# snowmaker_V1_0_for_eagle7_5.net
KiCad netlist of a schematic drawn in EAGLE
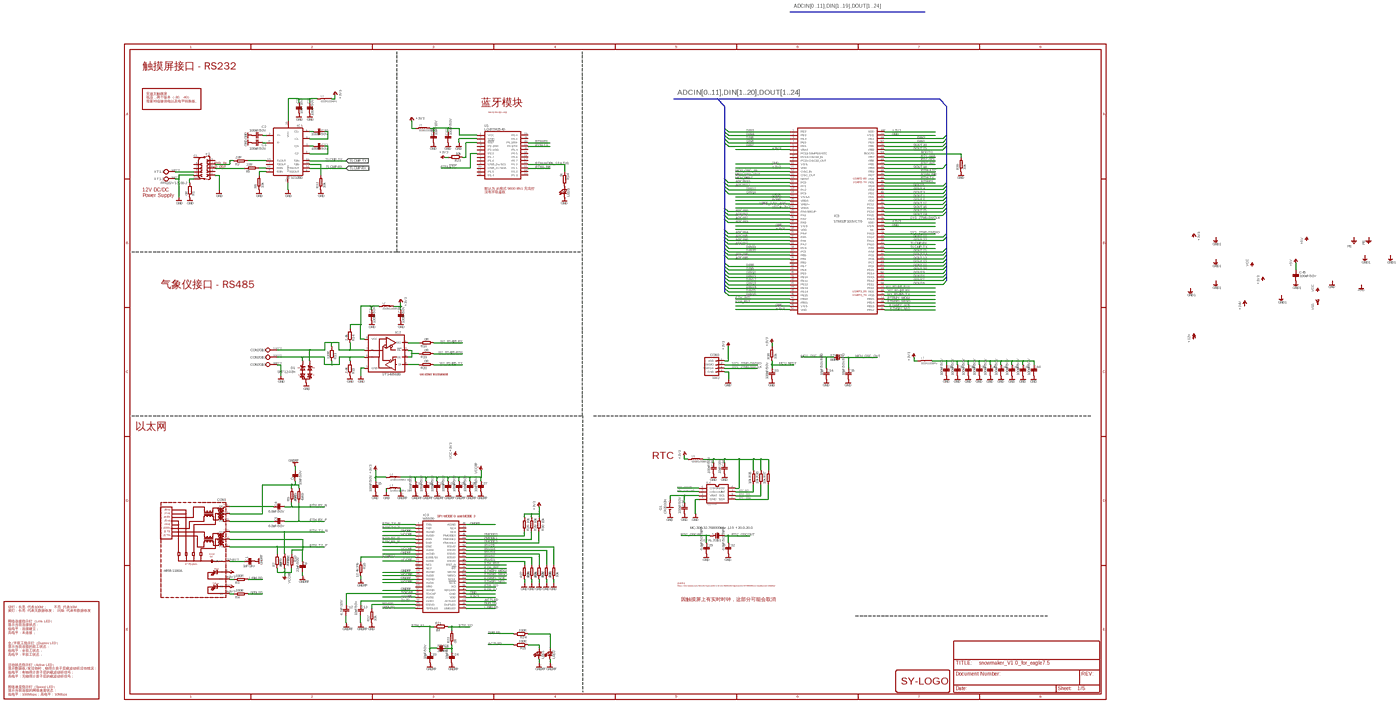
[diagram p0: schematic, sheet 1, overview]
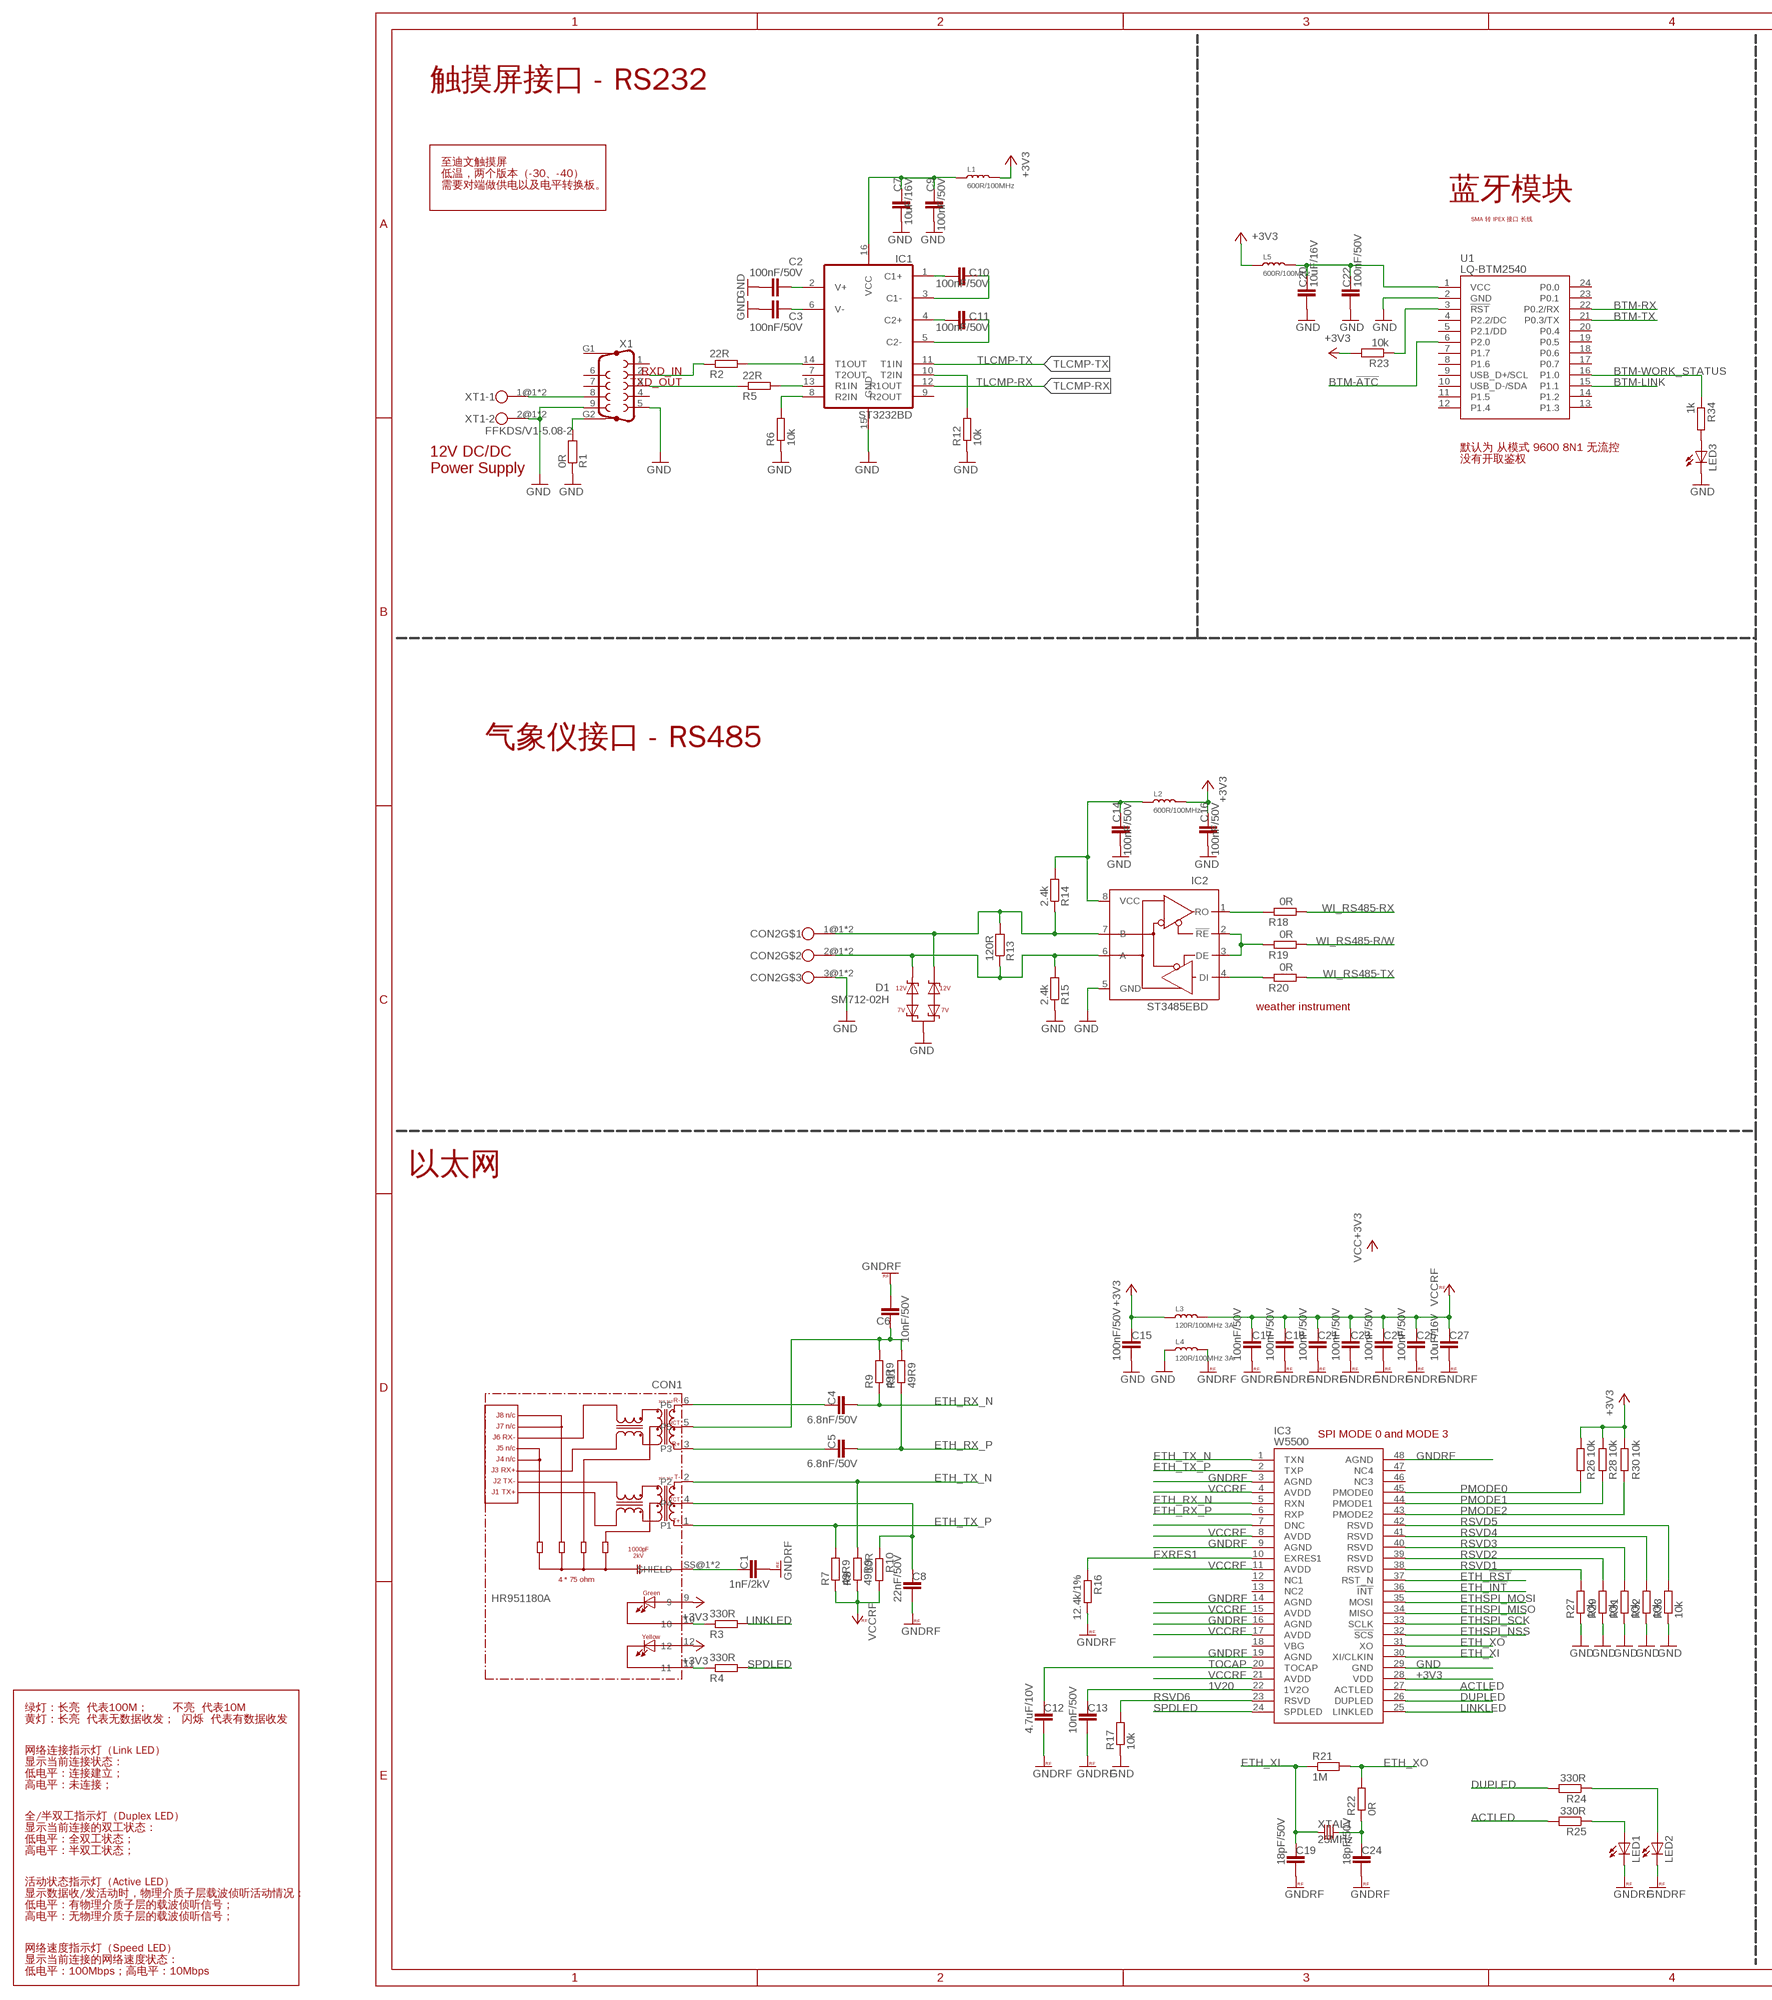
[diagram p1: schematic, sheet 1, part 1 of 4]
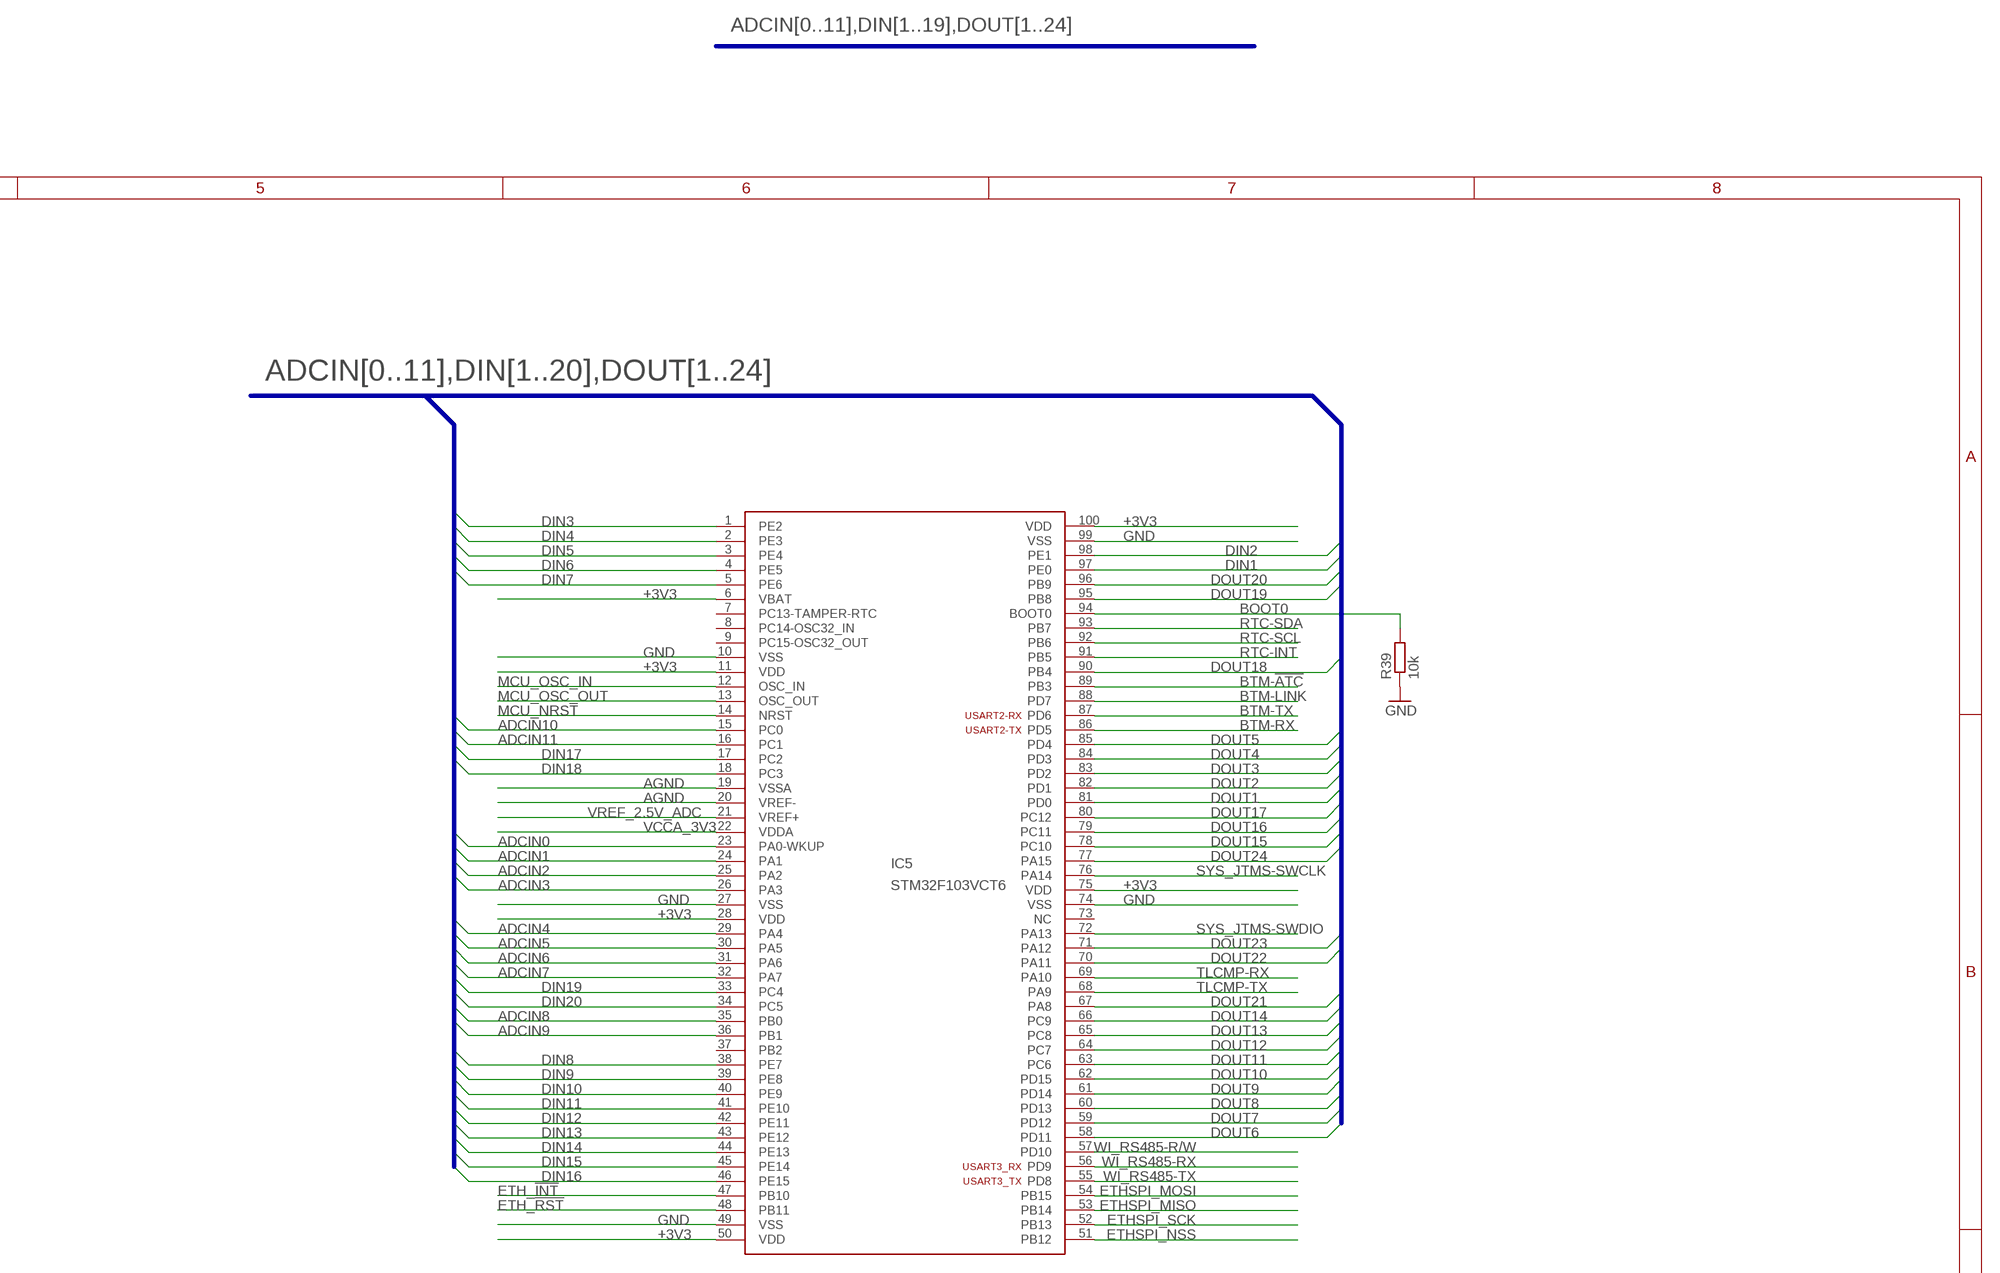
[diagram p2: schematic, sheet 1, part 2 of 4]
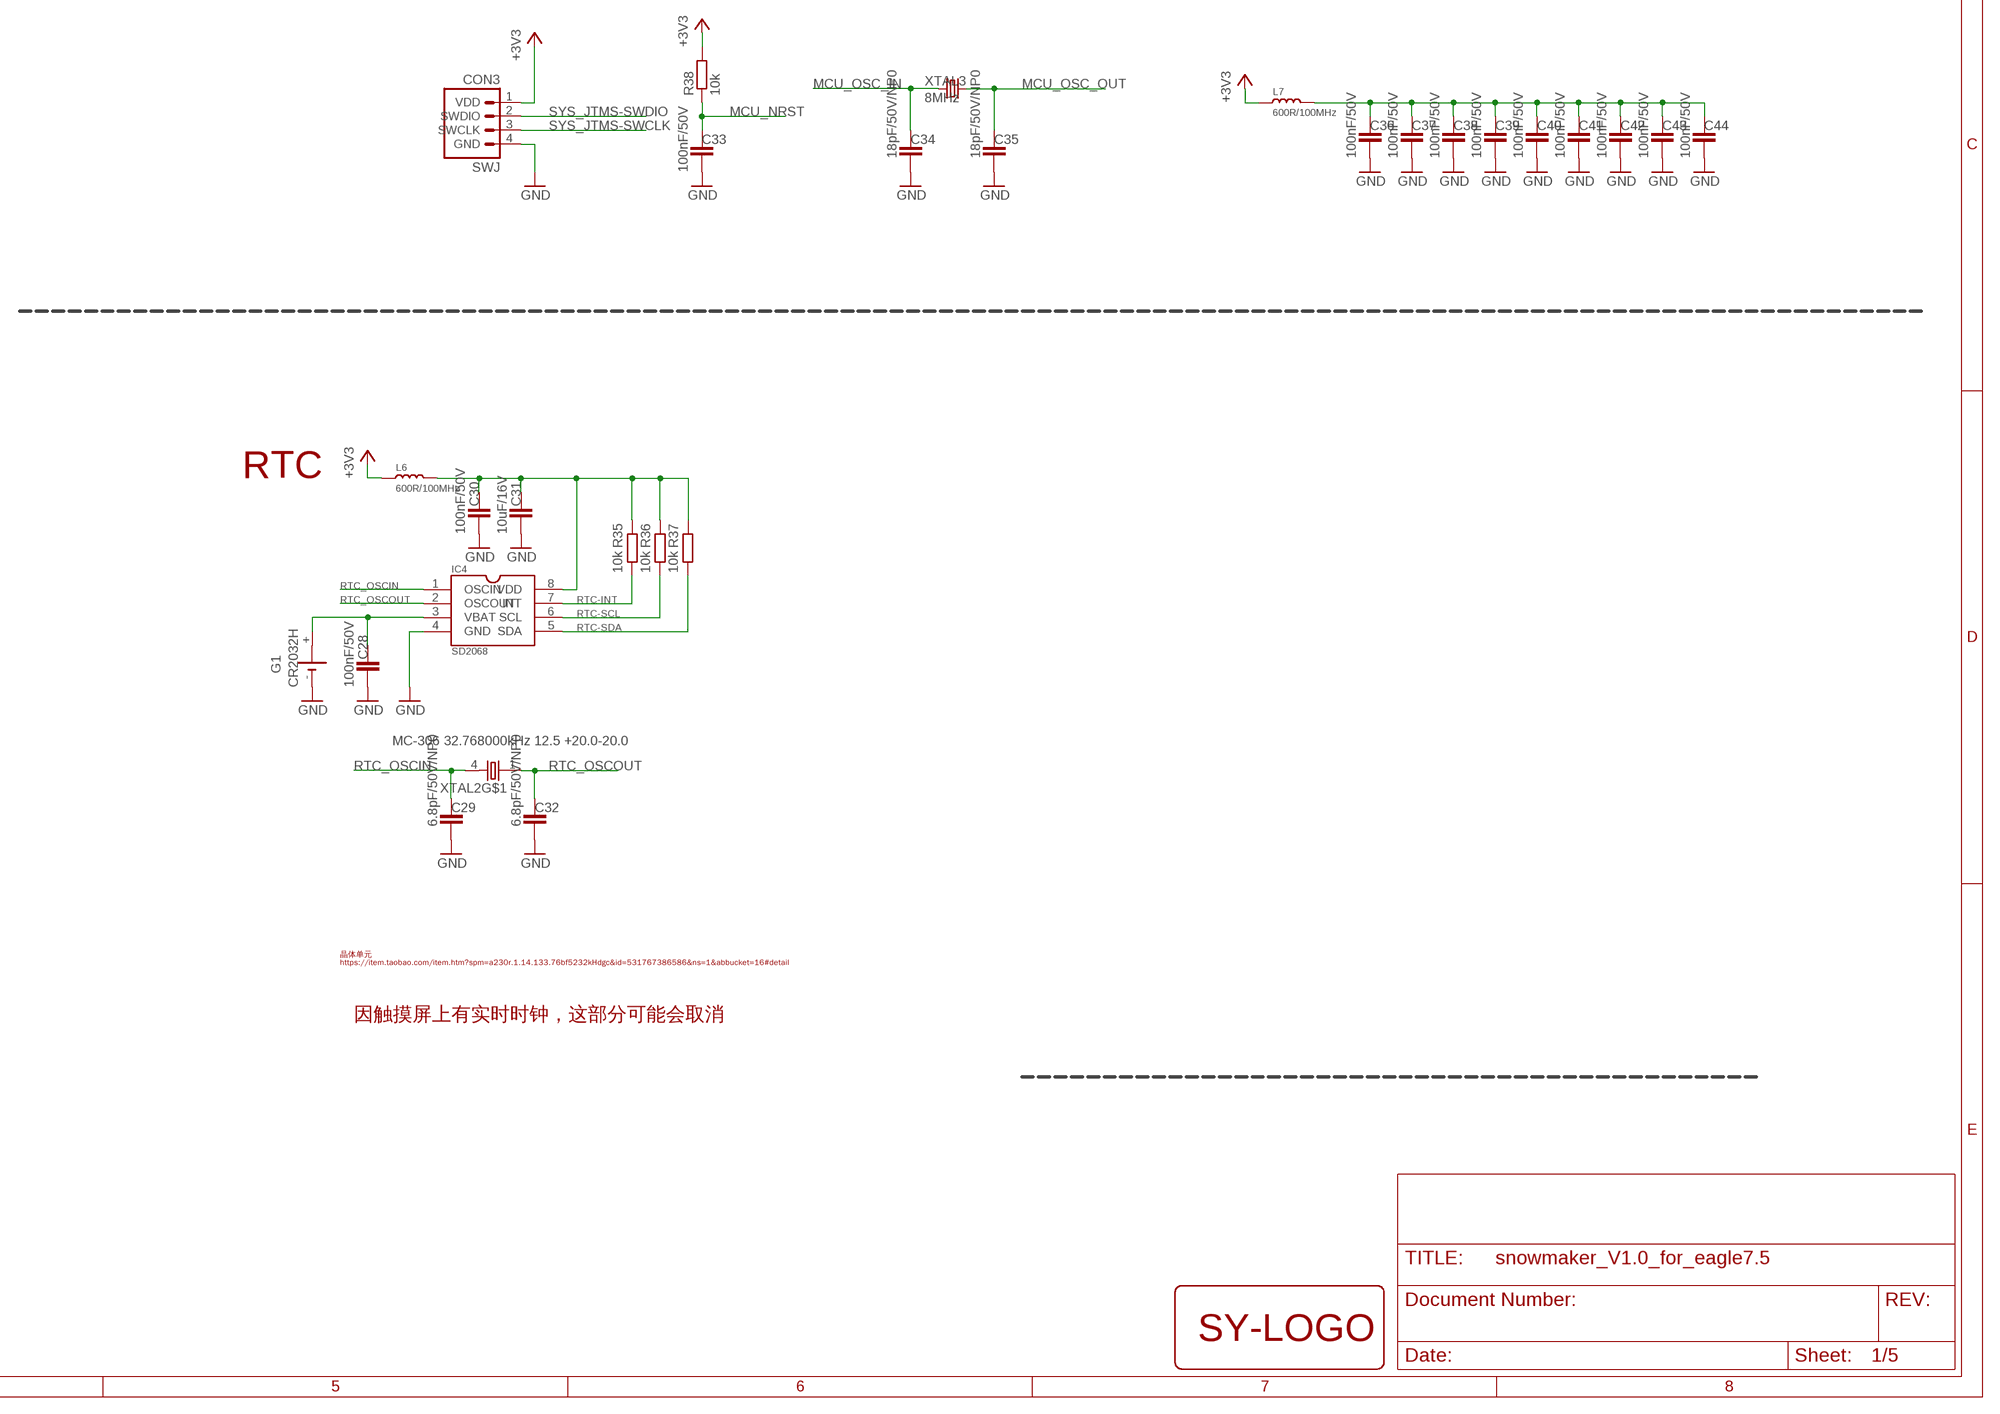
[diagram p3: schematic, sheet 1, part 3 of 4]
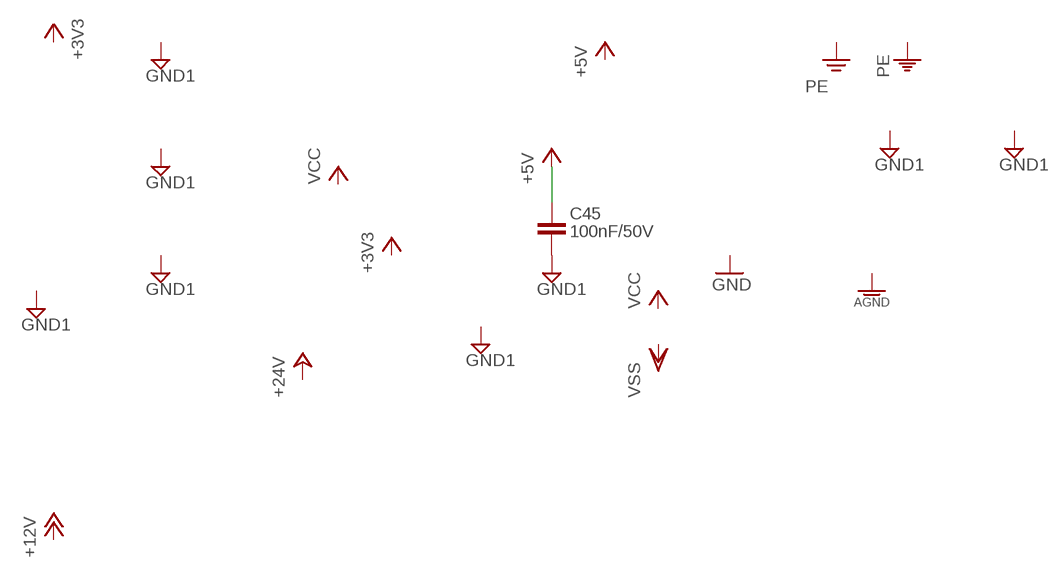
[diagram p4: schematic, sheet 1, part 4 of 4]
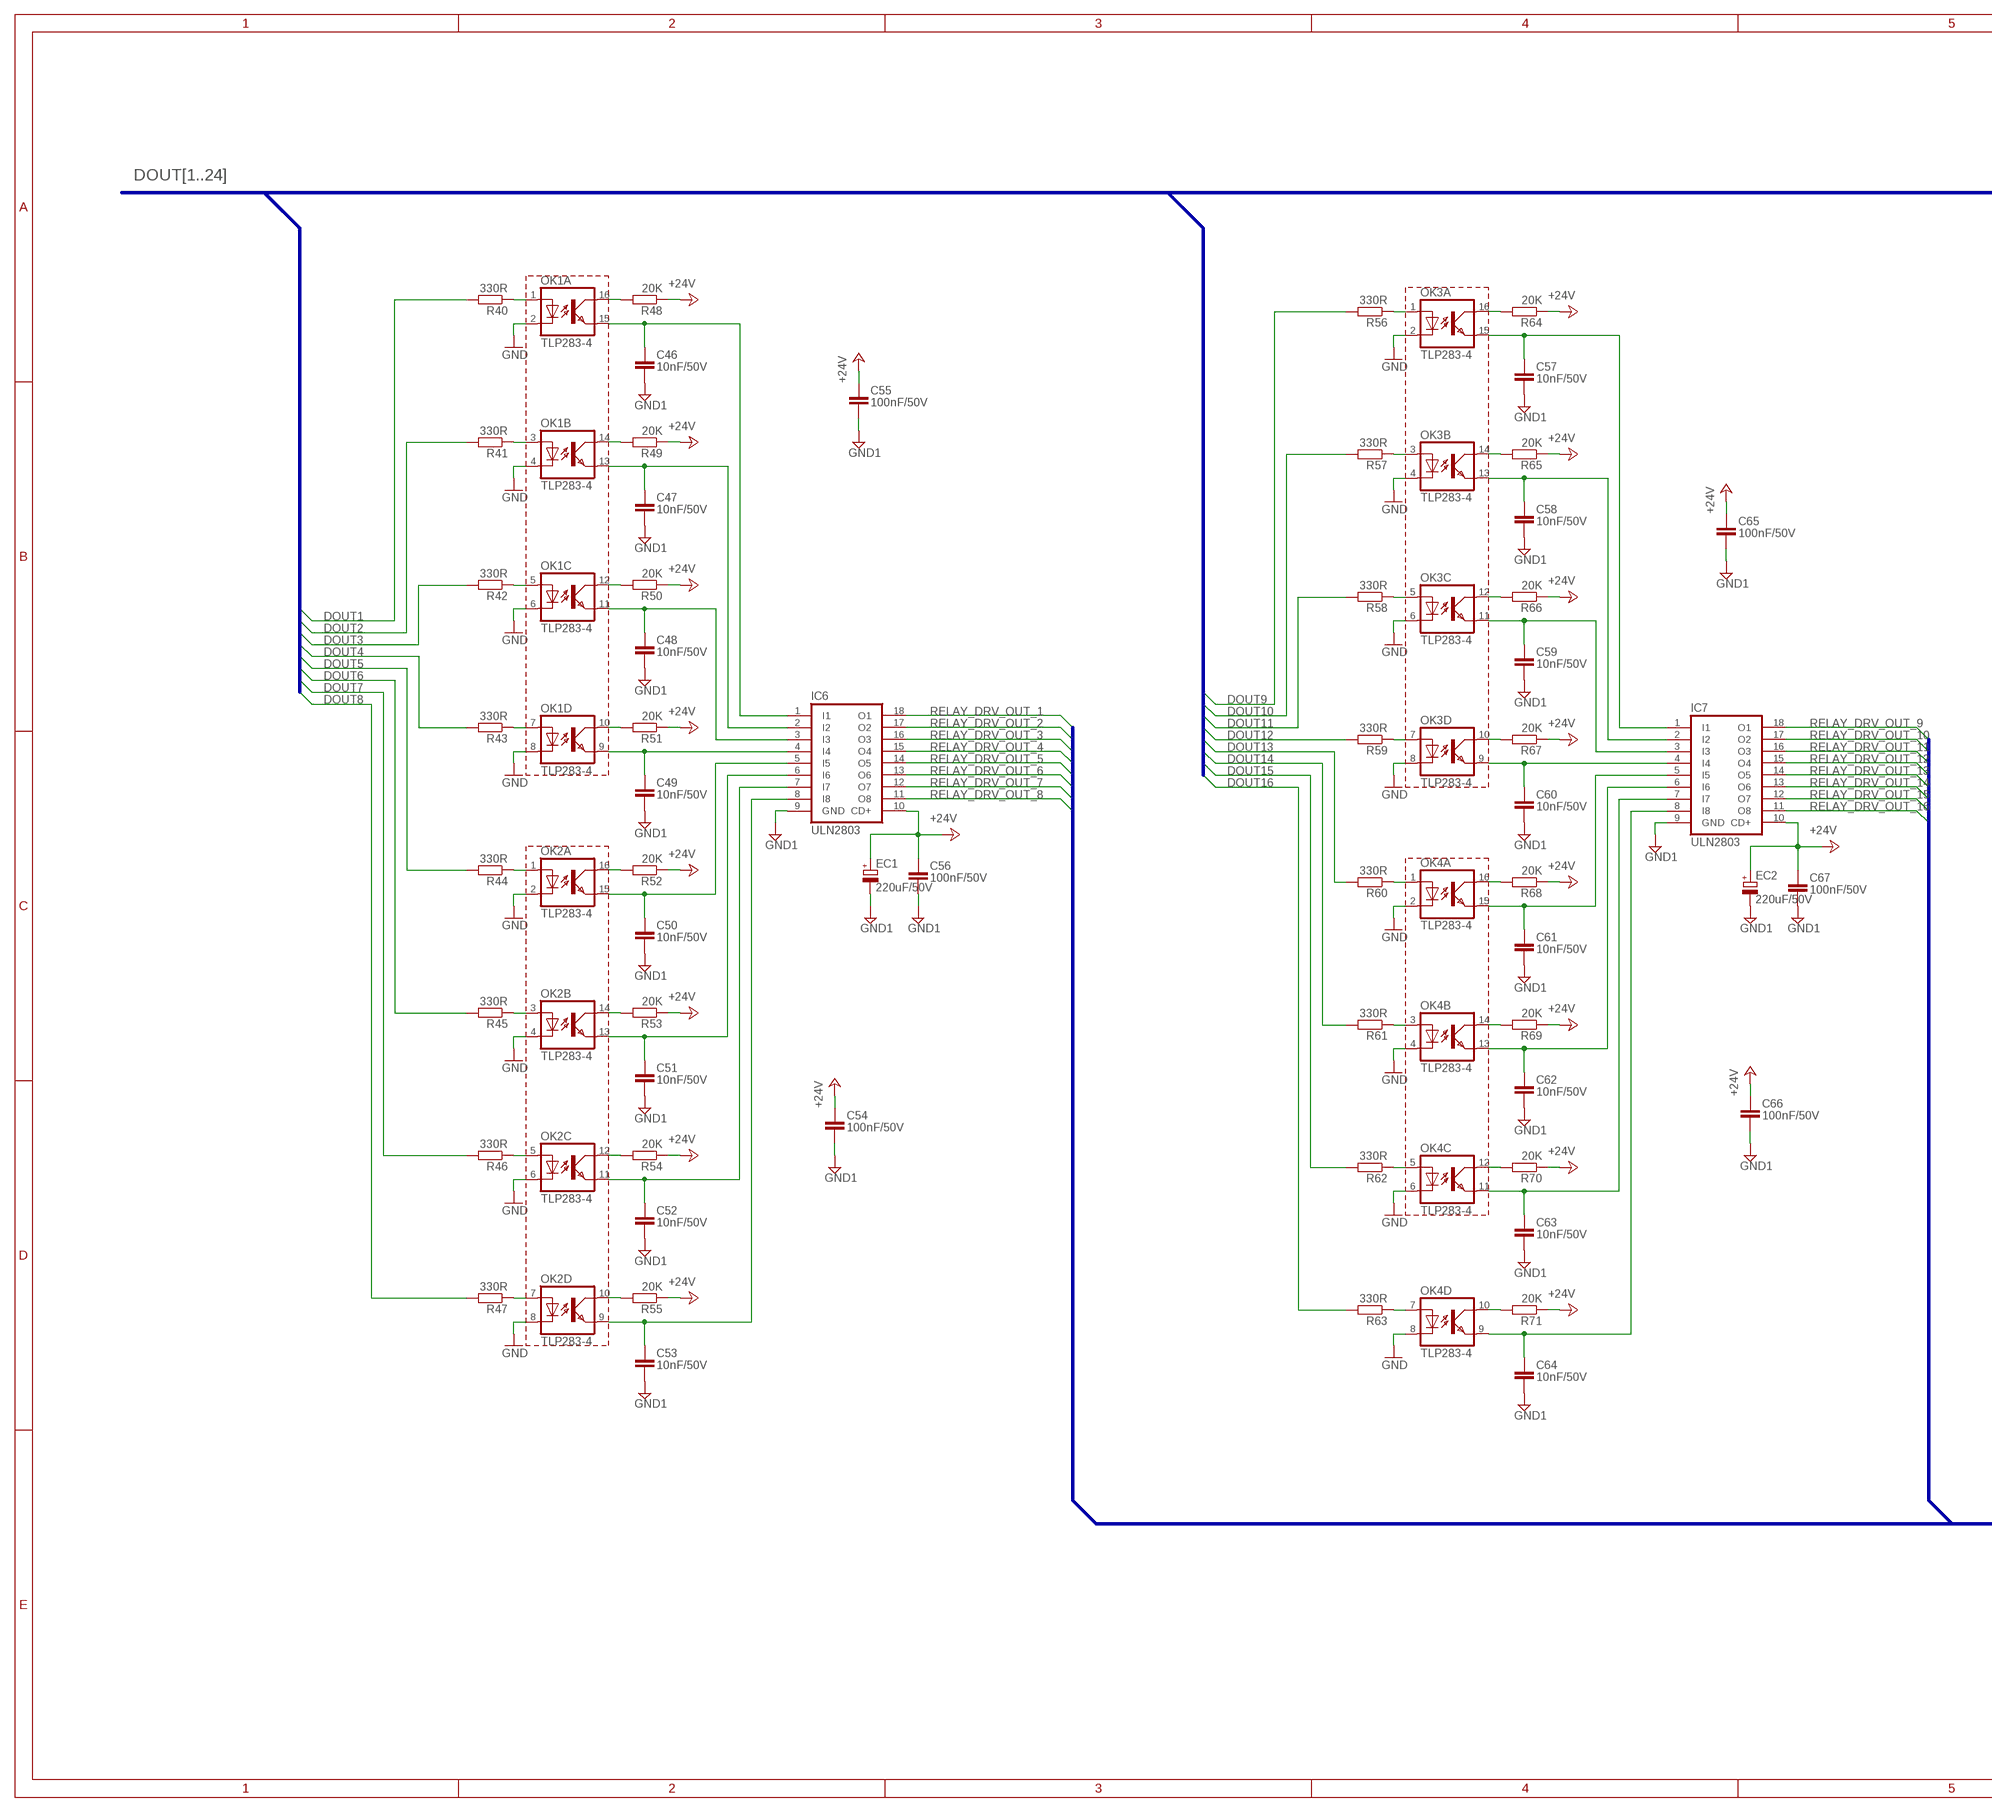
[diagram p5: schematic, sheet 2, part 1 of 2]
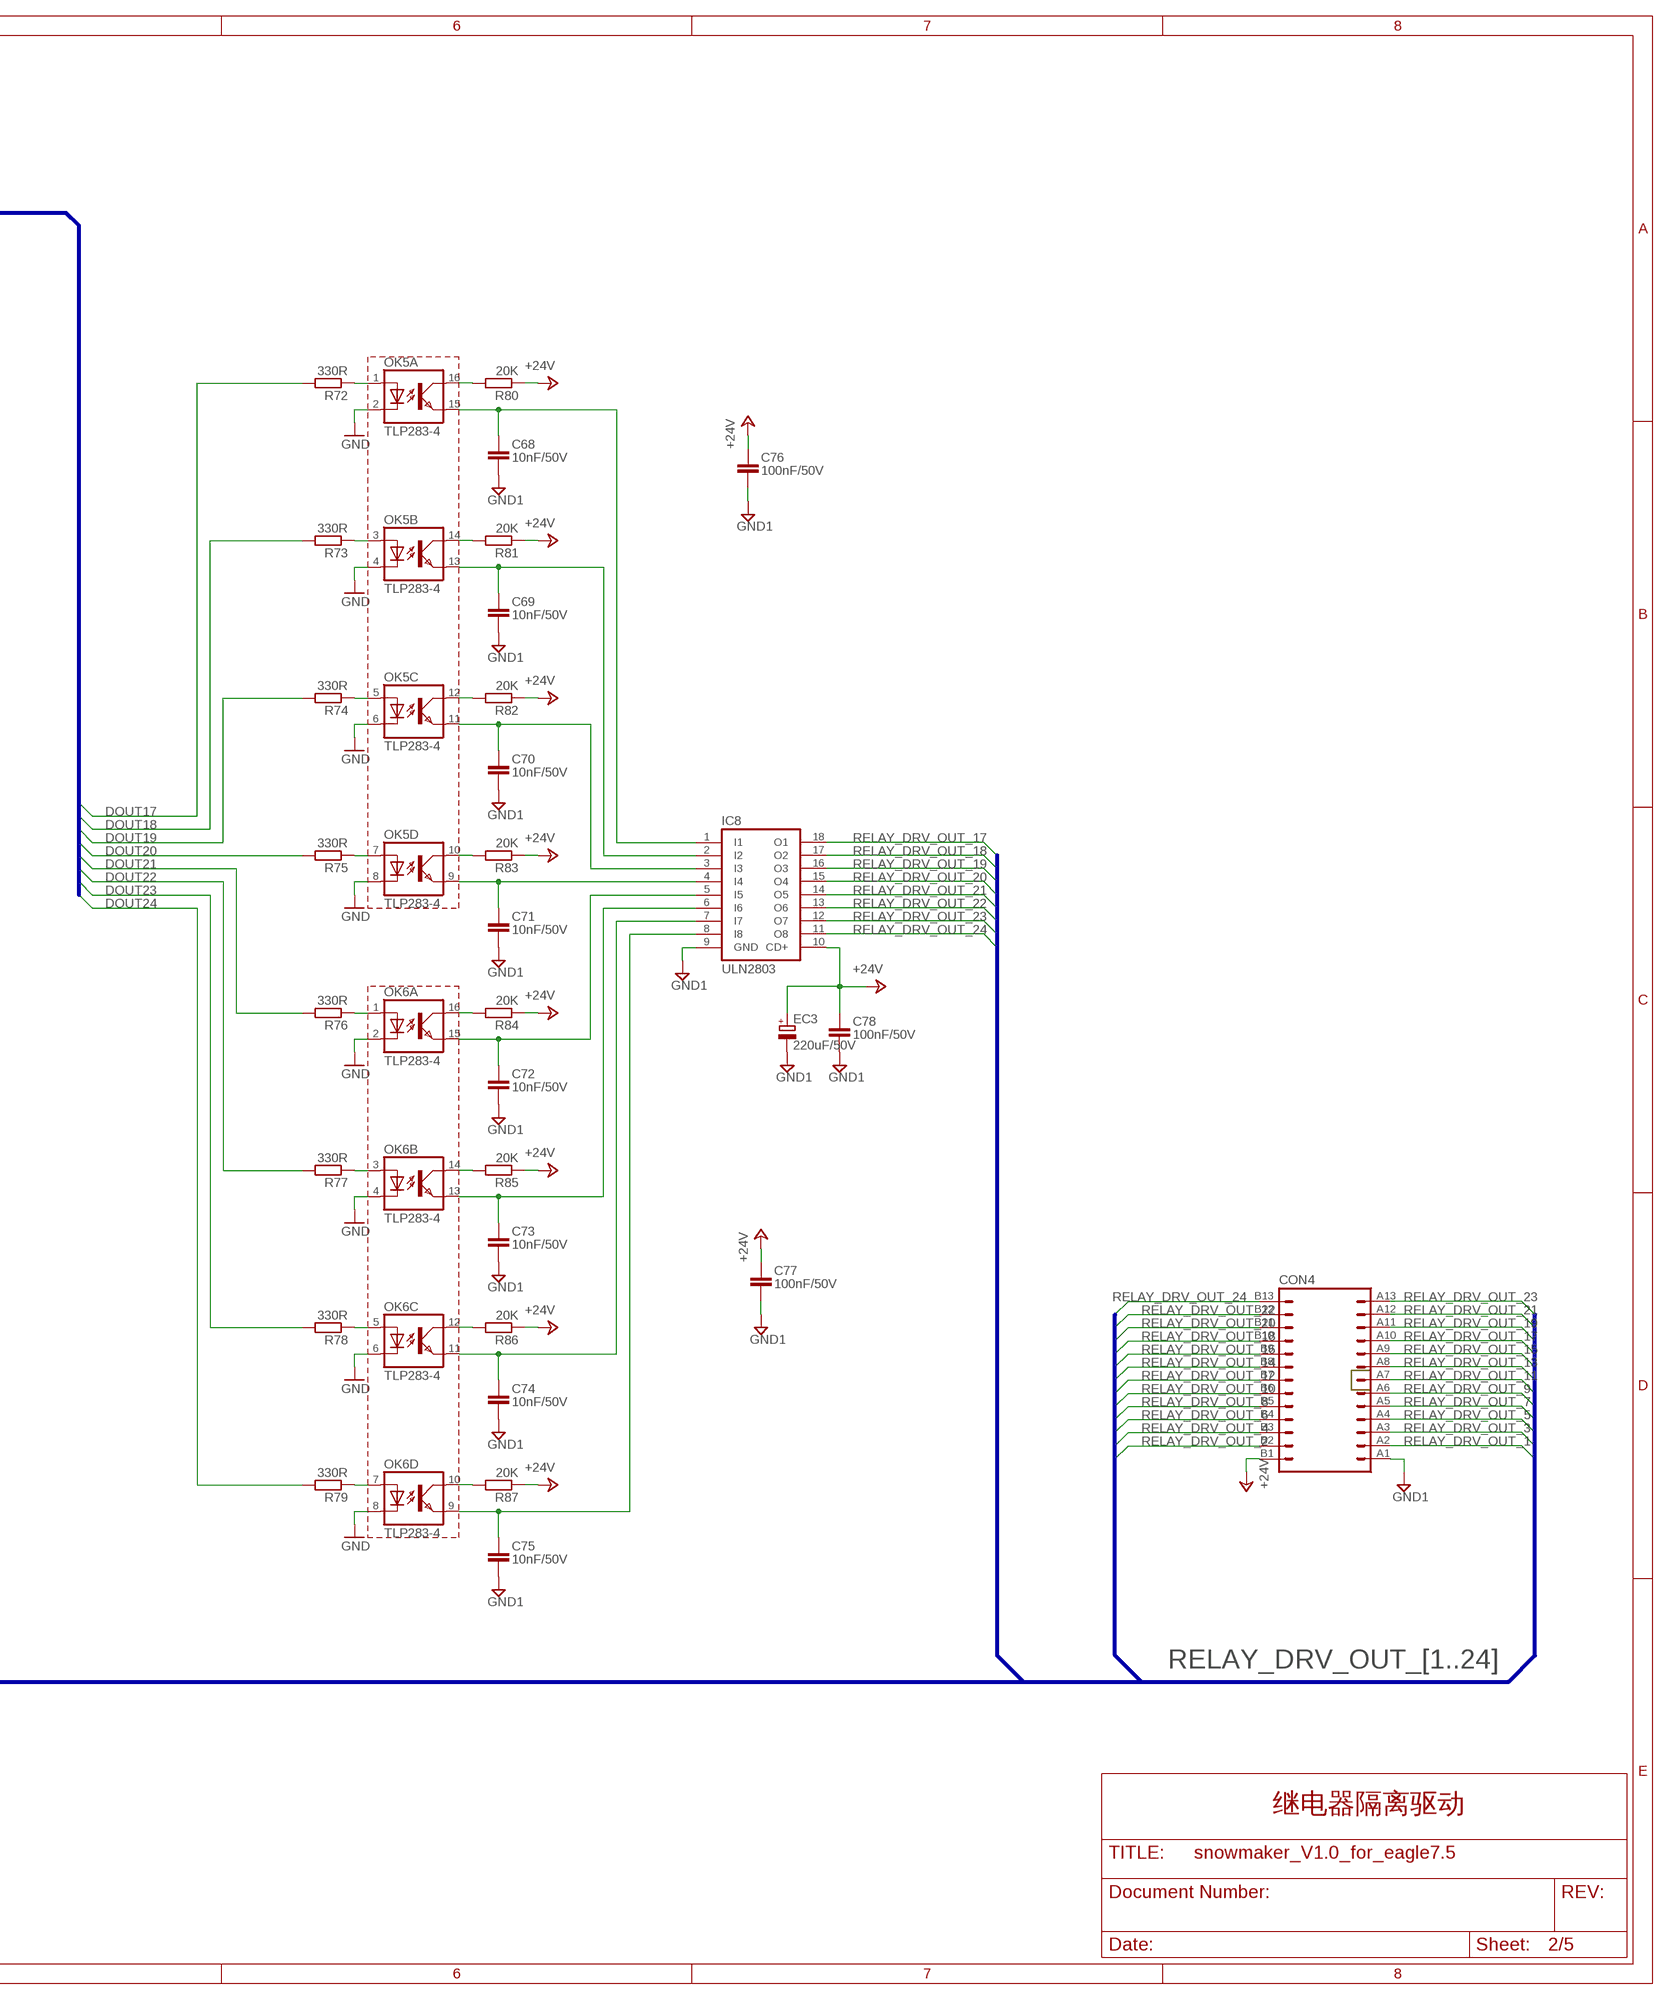
[diagram p6: schematic, sheet 2, part 2 of 2]
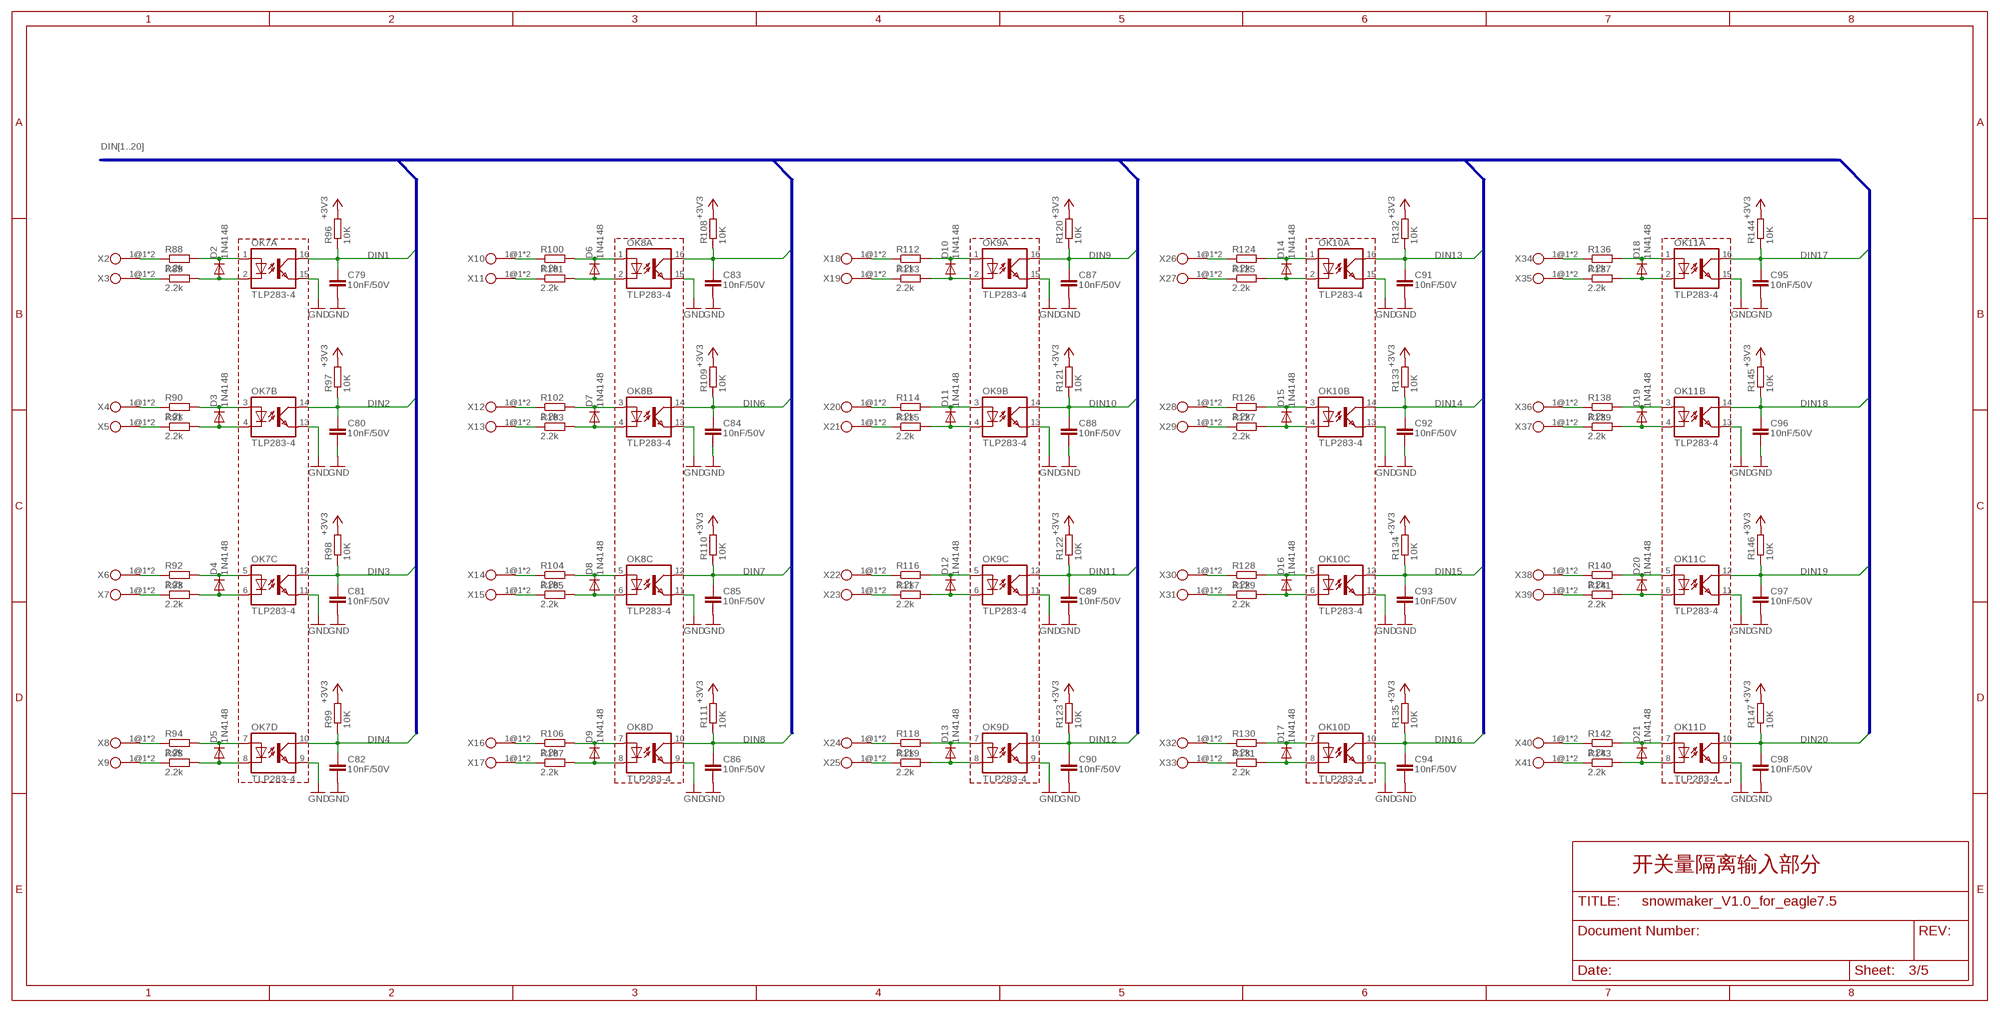
[diagram p7: schematic, sheet 3]
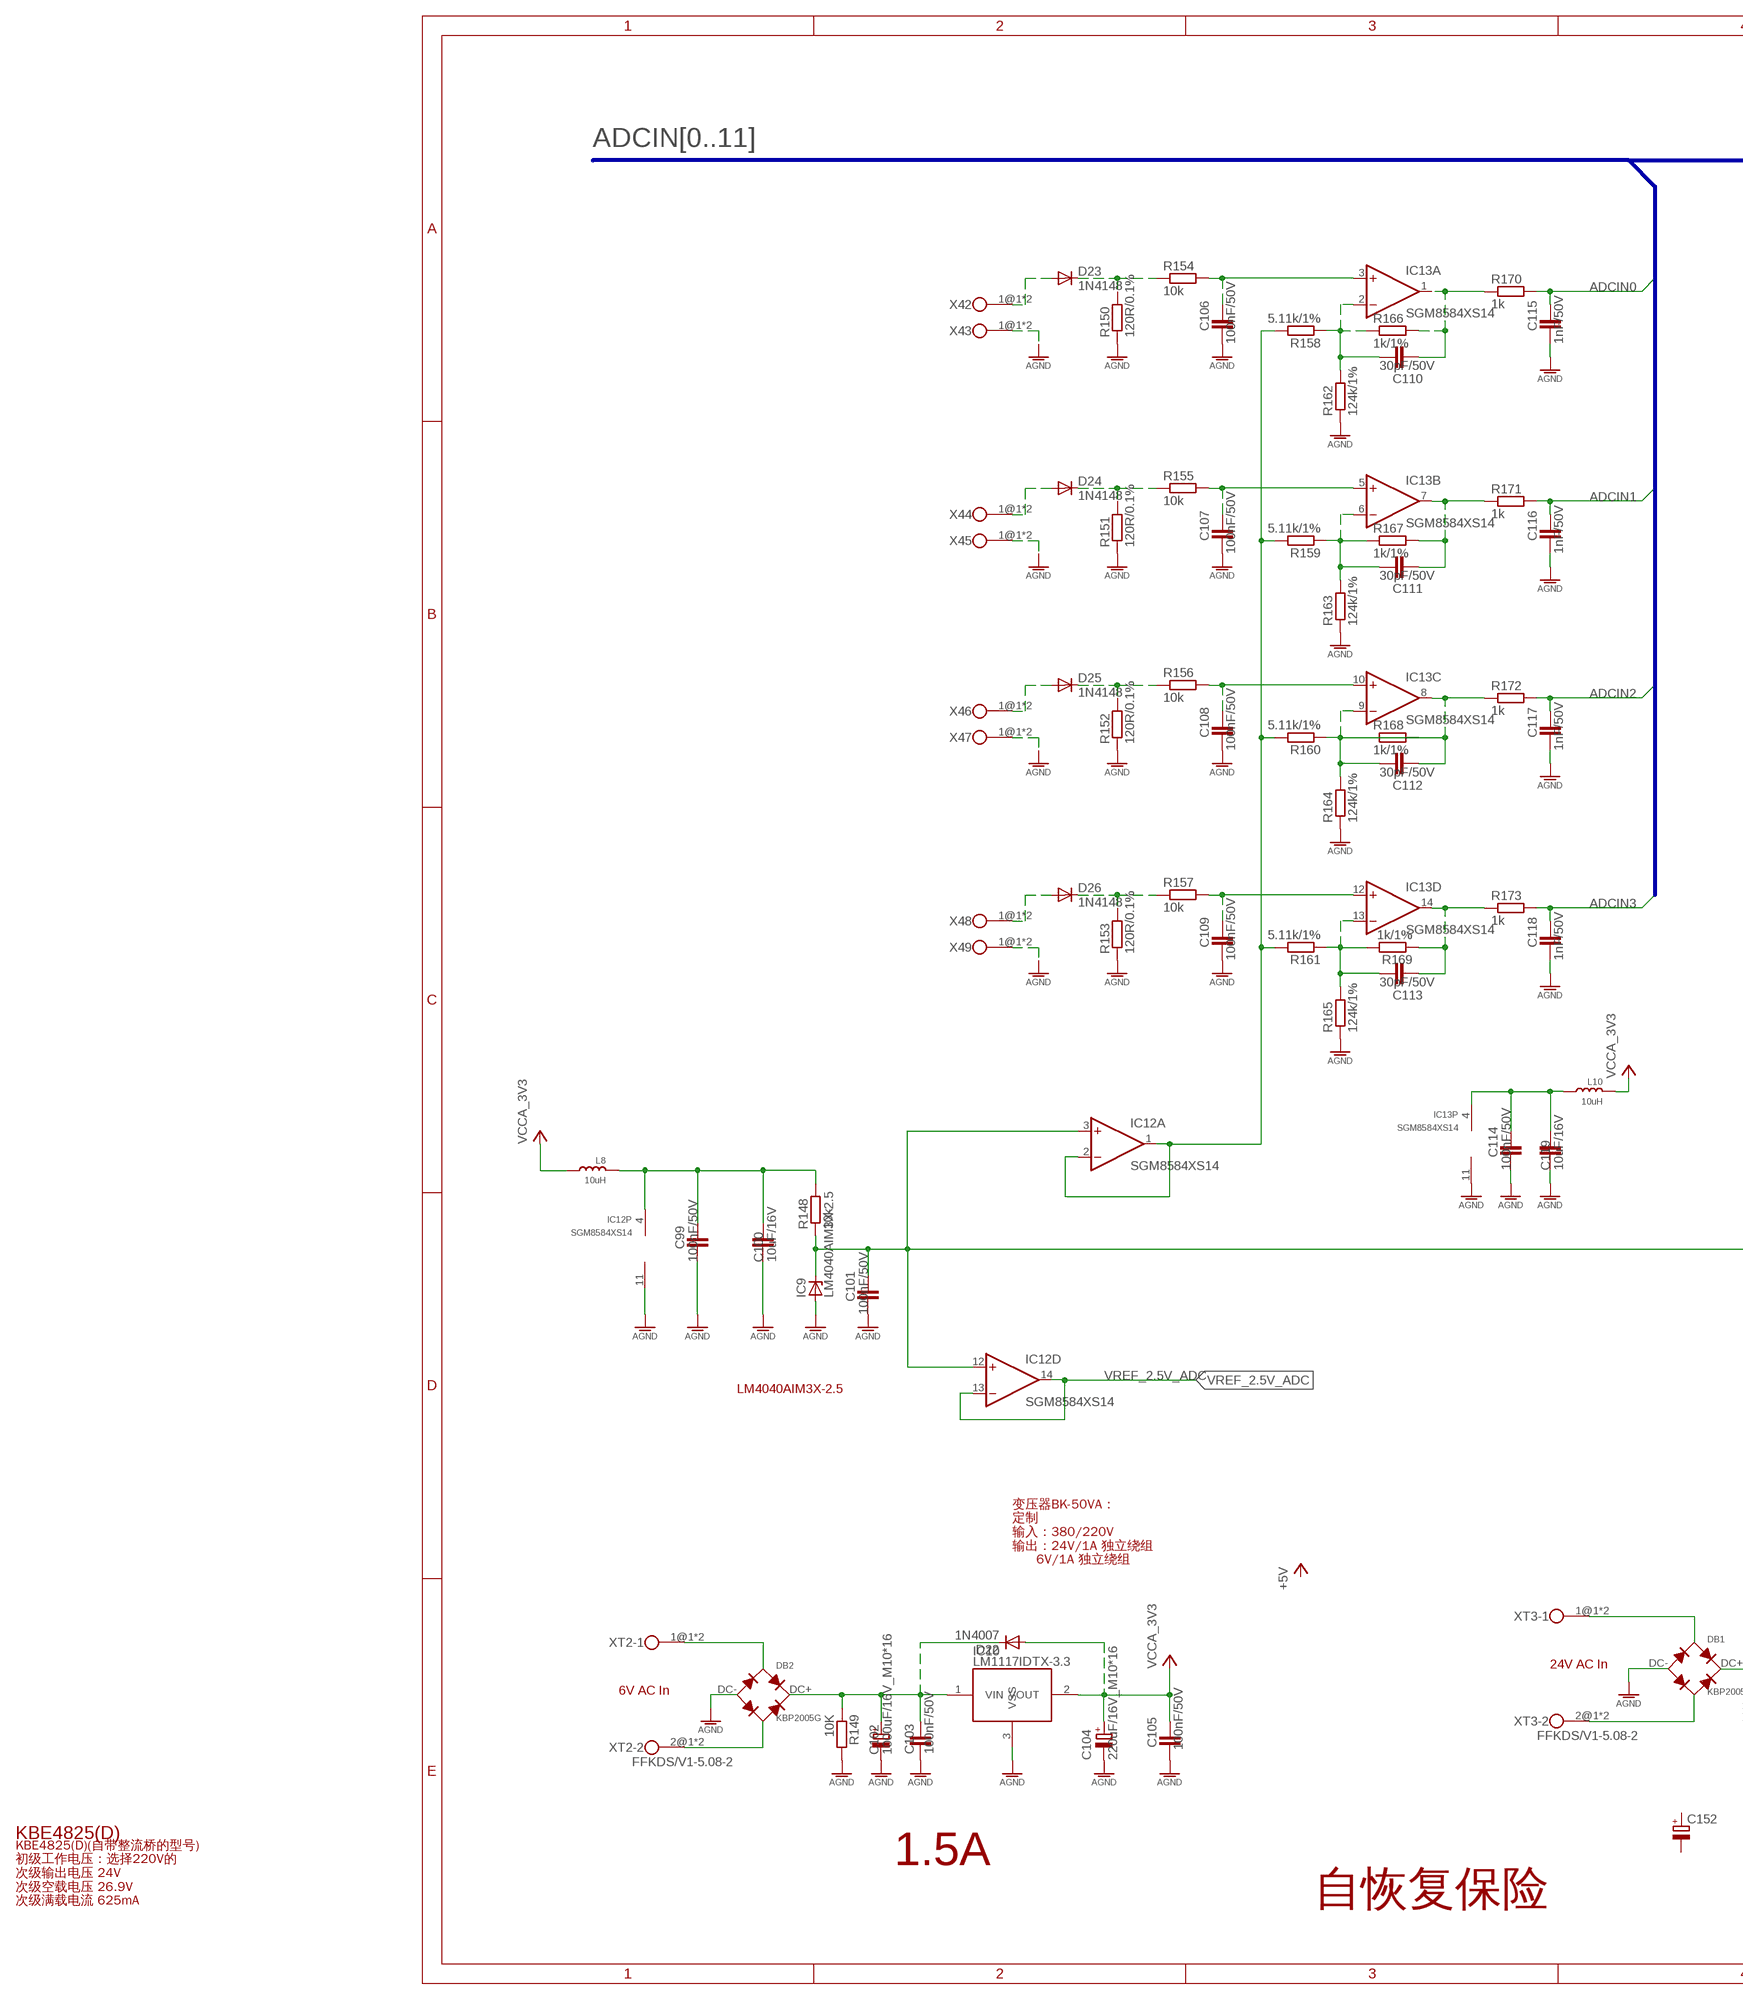
[diagram p8: schematic, sheet 4, part 1 of 2]
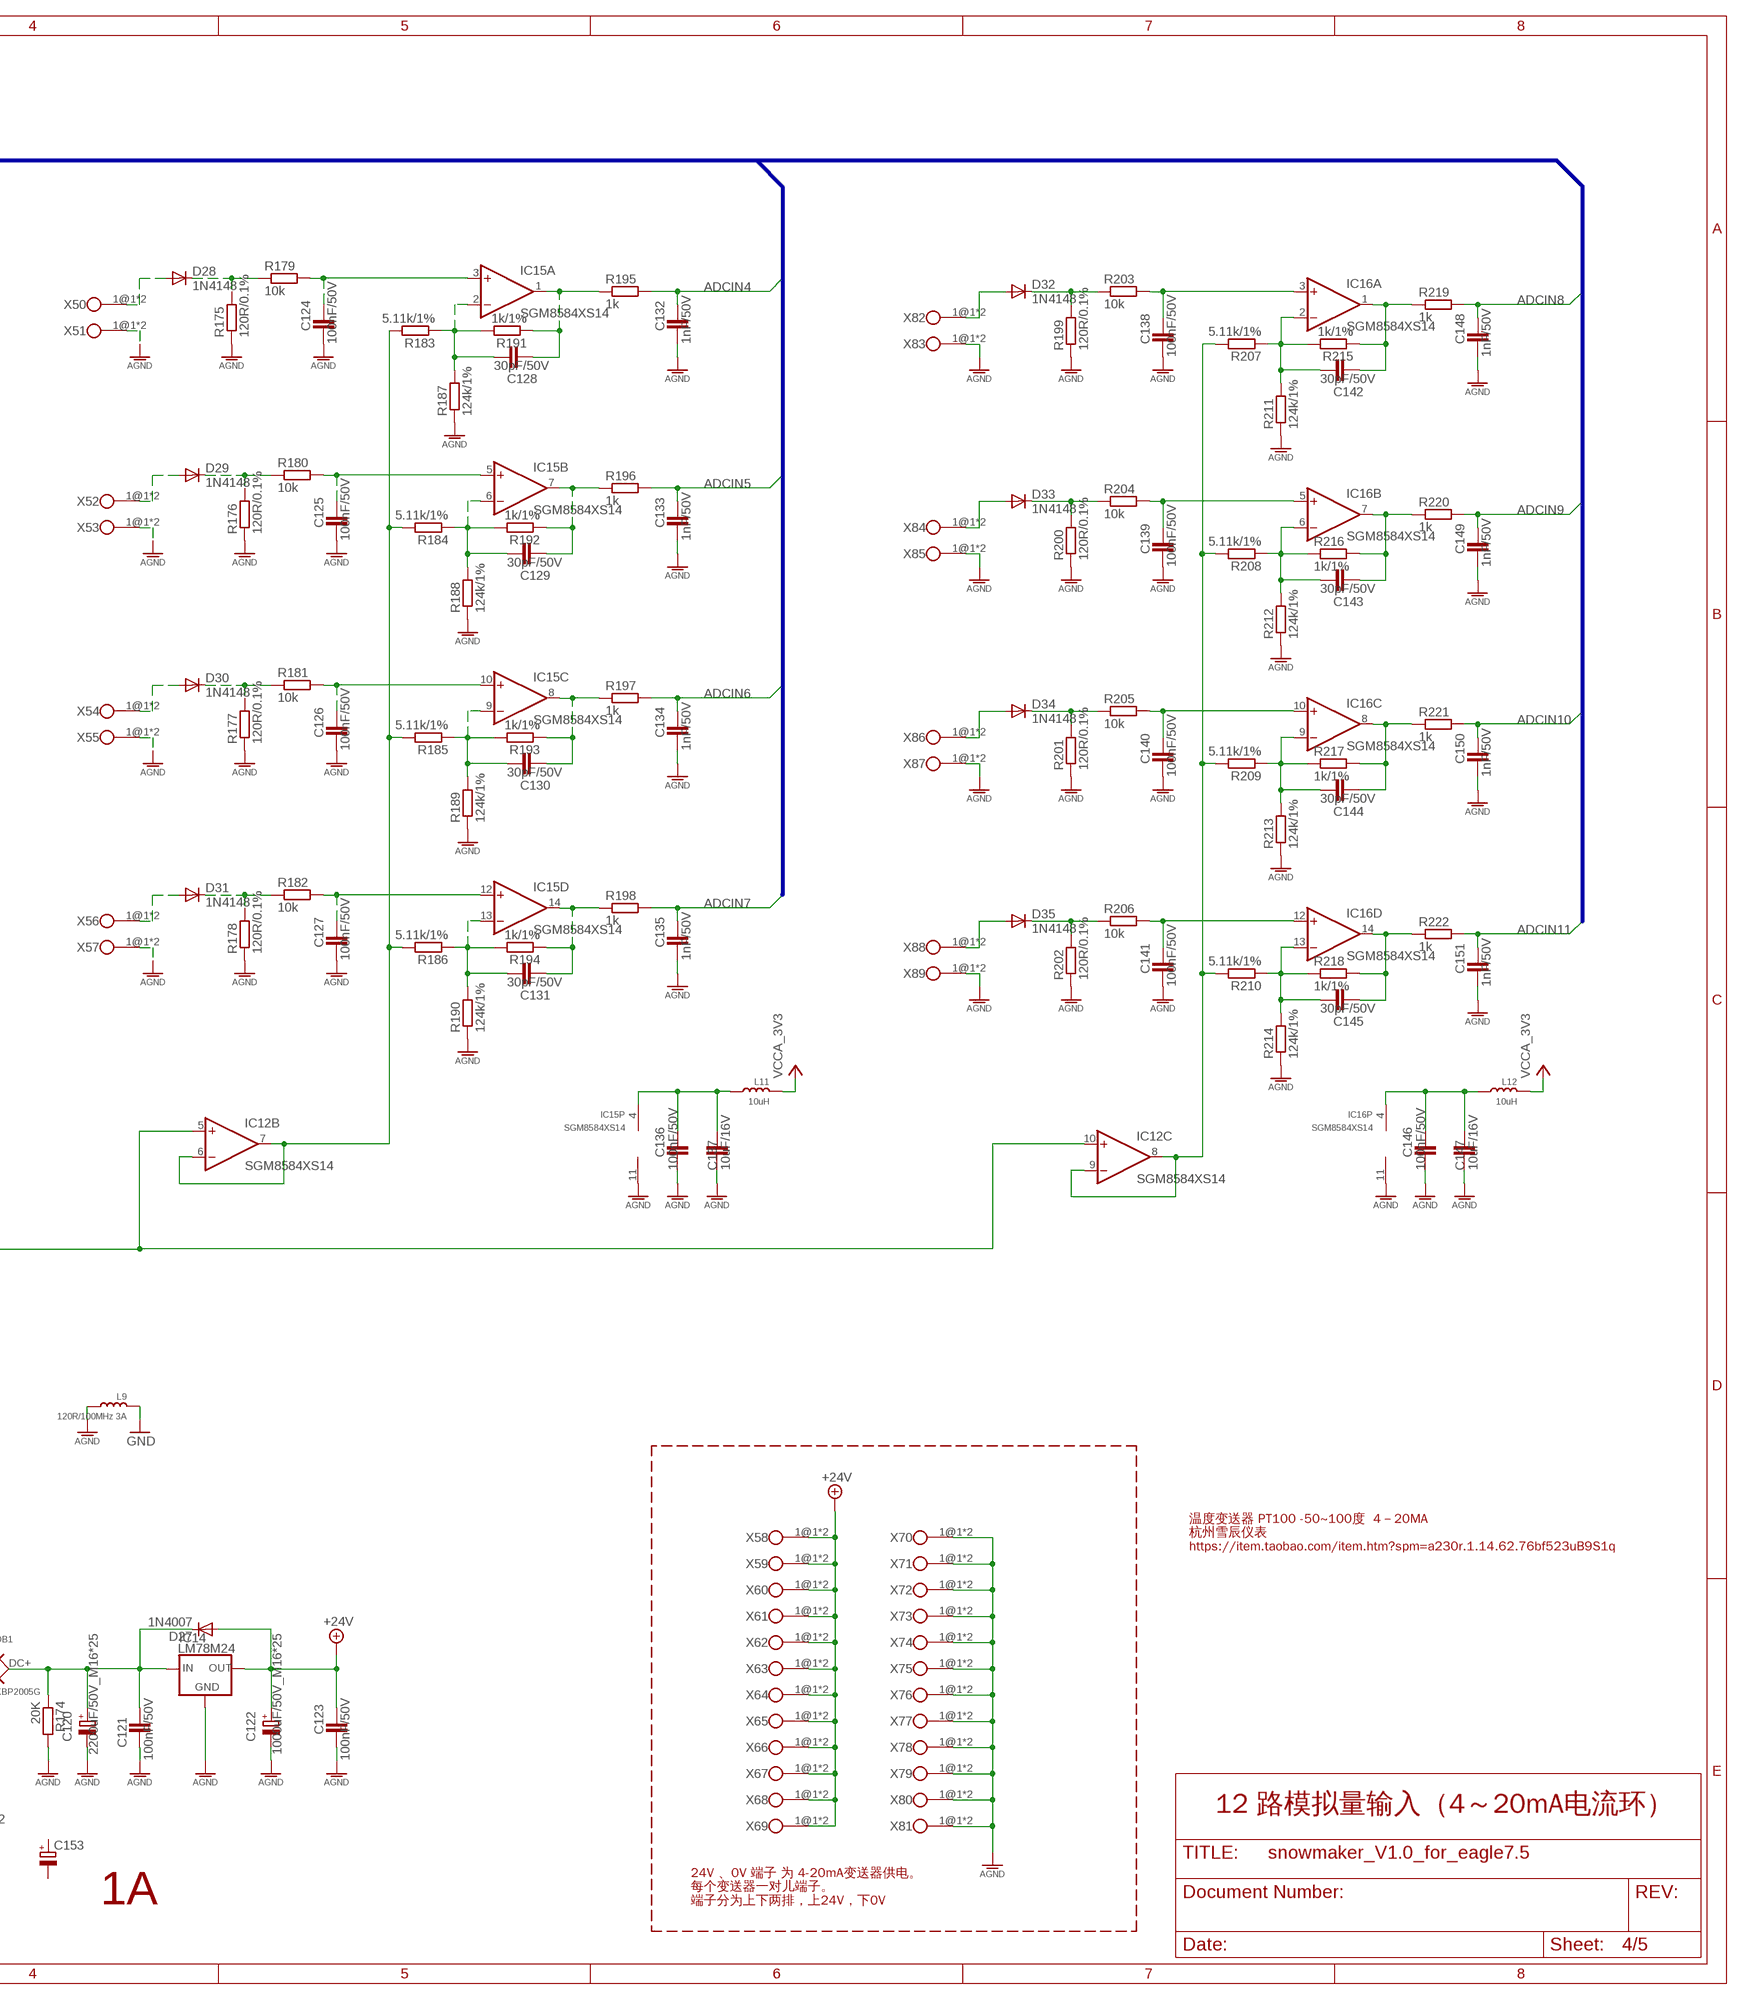
[diagram p9: schematic, sheet 4, part 2 of 2]
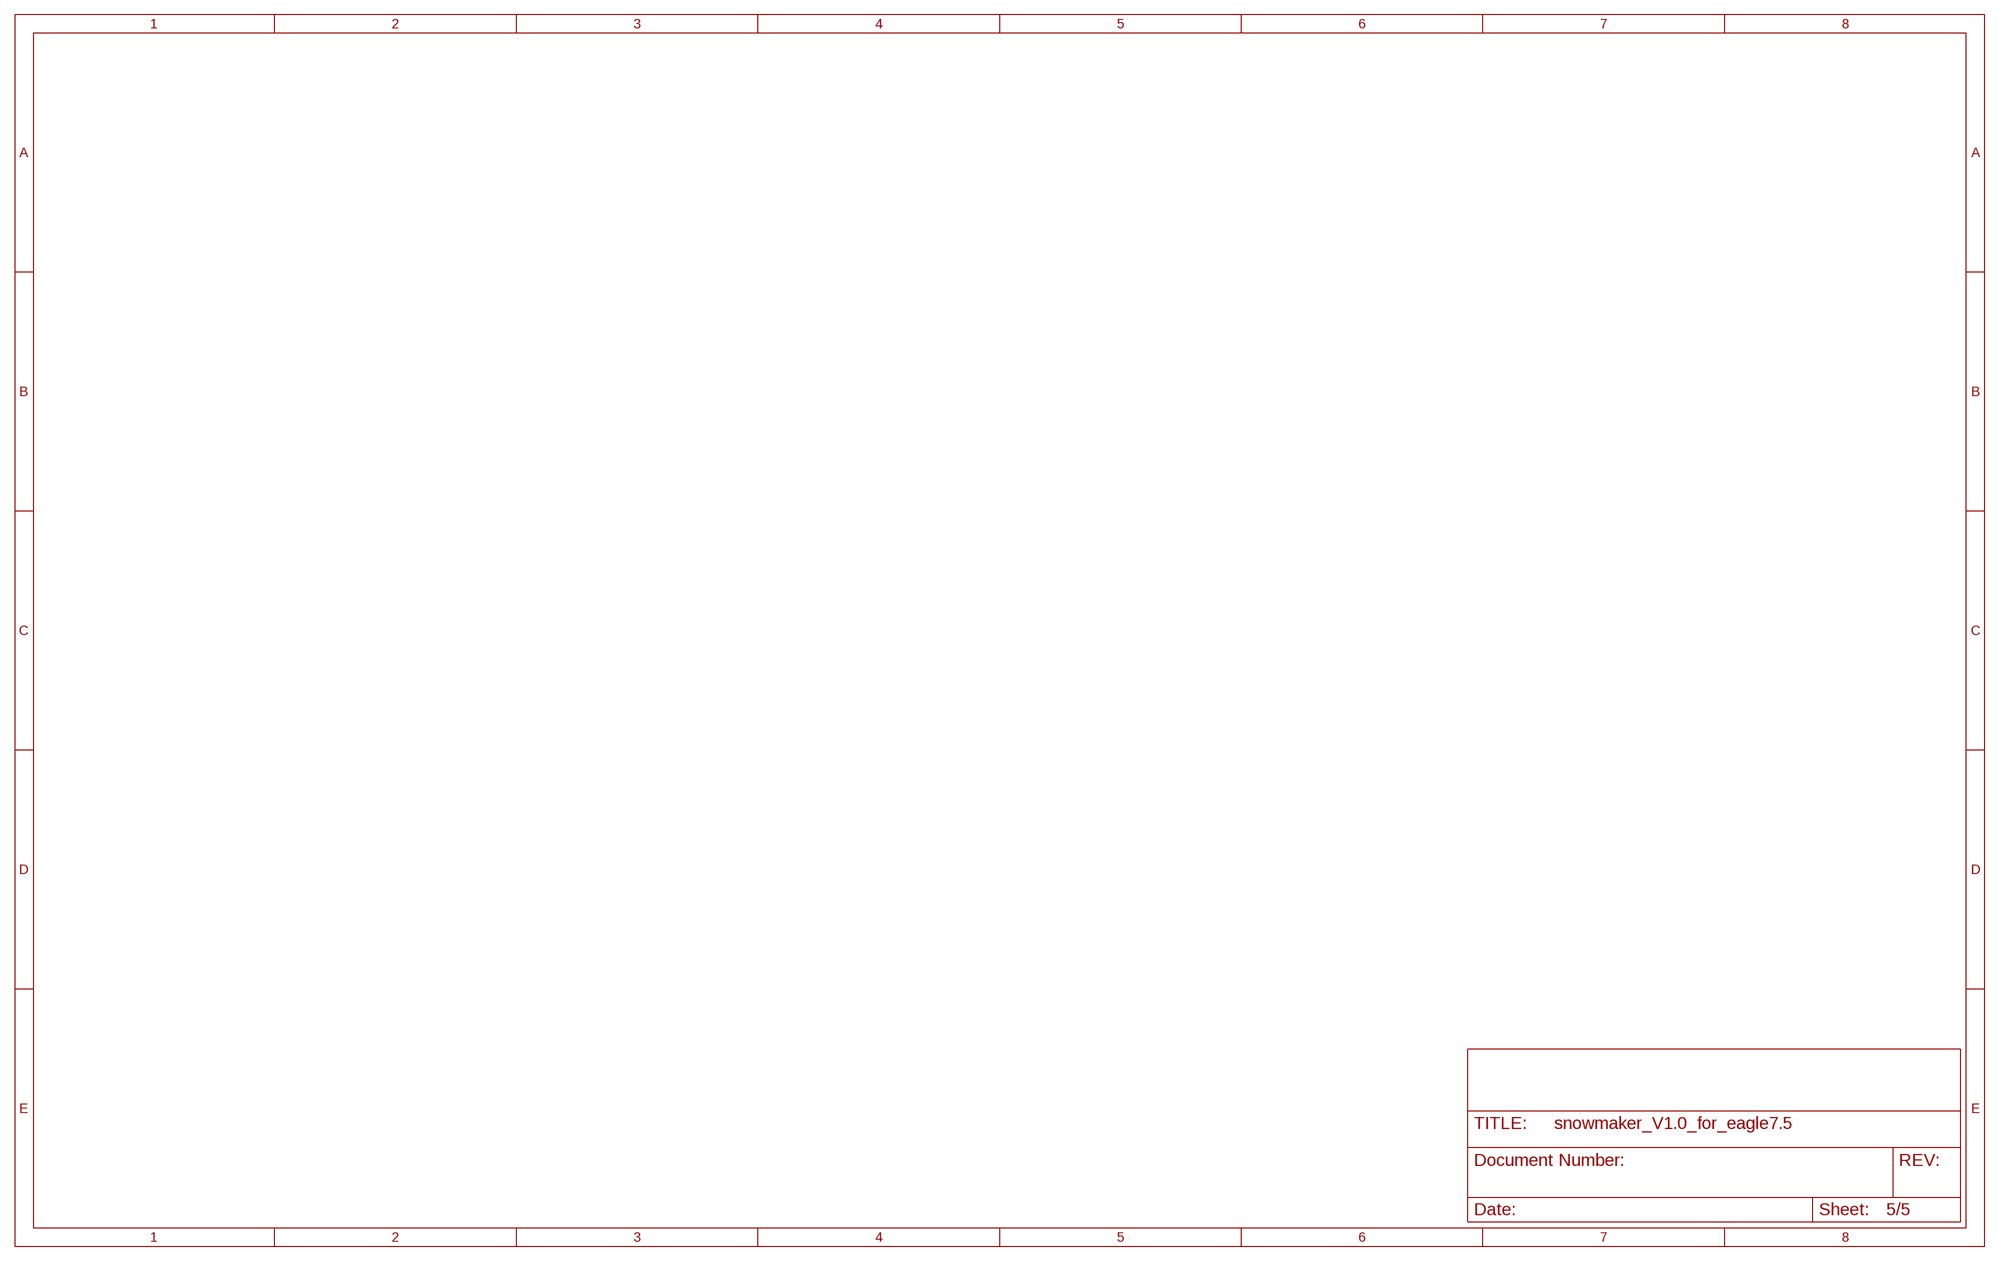
[diagram p10: schematic, sheet 5]

(export (version "E")
  (design (tool "Eeschema 10.0.6"))
  (components
    (comp (ref "C46")
      (value "10nF/50V")
      (footprint "eagle-import:C0603")
      (libsource (lib "eagle-import") (part "C0603"))
    )
    (comp (ref "C47")
      (value "10nF/50V")
      (footprint "eagle-import:C0603")
      (libsource (lib "eagle-import") (part "C0603"))
    )
    (comp (ref "C48")
      (value "10nF/50V")
      (footprint "eagle-import:C0603")
      (libsource (lib "eagle-import") (part "C0603"))
    )
    (comp (ref "C49")
      (value "10nF/50V")
      (footprint "eagle-import:C0603")
      (libsource (lib "eagle-import") (part "C0603"))
    )
    (comp (ref "C50")
      (value "10nF/50V")
      (footprint "eagle-import:C0603")
      (libsource (lib "eagle-import") (part "C0603"))
    )
    (comp (ref "C51")
      (value "10nF/50V")
      (footprint "eagle-import:C0603")
      (libsource (lib "eagle-import") (part "C0603"))
    )
    (comp (ref "C52")
      (value "10nF/50V")
      (footprint "eagle-import:C0603")
      (libsource (lib "eagle-import") (part "C0603"))
    )
    (comp (ref "C53")
      (value "10nF/50V")
      (footprint "eagle-import:C0603")
      (libsource (lib "eagle-import") (part "C0603"))
    )
    (comp (ref "C54")
      (value "100nF/50V")
      (footprint "eagle-import:C0603")
      (libsource (lib "eagle-import") (part "C0603"))
    )
    (comp (ref "C55")
      (value "100nF/50V")
      (footprint "eagle-import:C0603")
      (libsource (lib "eagle-import") (part "C0603"))
    )
    (comp (ref "C56")
      (value "100nF/50V")
      (footprint "eagle-import:C0603")
      (libsource (lib "eagle-import") (part "C0603"))
    )
    (comp (ref "C57")
      (value "10nF/50V")
      (footprint "eagle-import:C0603")
      (libsource (lib "eagle-import") (part "C0603"))
    )
    (comp (ref "C58")
      (value "10nF/50V")
      (footprint "eagle-import:C0603")
      (libsource (lib "eagle-import") (part "C0603"))
    )
    (comp (ref "C59")
      (value "10nF/50V")
      (footprint "eagle-import:C0603")
      (libsource (lib "eagle-import") (part "C0603"))
    )
    (comp (ref "C60")
      (value "10nF/50V")
      (footprint "eagle-import:C0603")
      (libsource (lib "eagle-import") (part "C0603"))
    )
    (comp (ref "C61")
      (value "10nF/50V")
      (footprint "eagle-import:C0603")
      (libsource (lib "eagle-import") (part "C0603"))
    )
    (comp (ref "C62")
      (value "10nF/50V")
      (footprint "eagle-import:C0603")
      (libsource (lib "eagle-import") (part "C0603"))
    )
    (comp (ref "C63")
      (value "10nF/50V")
      (footprint "eagle-import:C0603")
      (libsource (lib "eagle-import") (part "C0603"))
    )
    (comp (ref "C64")
      (value "10nF/50V")
      (footprint "eagle-import:C0603")
      (libsource (lib "eagle-import") (part "C0603"))
    )
    (comp (ref "C65")
      (value "100nF/50V")
      (footprint "eagle-import:C0603")
      (libsource (lib "eagle-import") (part "C0603"))
    )
    (comp (ref "C66")
      (value "100nF/50V")
      (footprint "eagle-import:C0603")
      (libsource (lib "eagle-import") (part "C0603"))
    )
    (comp (ref "C67")
      (value "100nF/50V")
      (footprint "eagle-import:C0603")
      (libsource (lib "eagle-import") (part "C0603"))
    )
    (comp (ref "C68")
      (value "10nF/50V")
      (footprint "eagle-import:C0603")
      (libsource (lib "eagle-import") (part "C0603"))
    )
    (comp (ref "C69")
      (value "10nF/50V")
      (footprint "eagle-import:C0603")
      (libsource (lib "eagle-import") (part "C0603"))
    )
    (comp (ref "C70")
      (value "10nF/50V")
      (footprint "eagle-import:C0603")
      (libsource (lib "eagle-import") (part "C0603"))
    )
    (comp (ref "C71")
      (value "10nF/50V")
      (footprint "eagle-import:C0603")
      (libsource (lib "eagle-import") (part "C0603"))
    )
    (comp (ref "C72")
      (value "10nF/50V")
      (footprint "eagle-import:C0603")
      (libsource (lib "eagle-import") (part "C0603"))
    )
    (comp (ref "C73")
      (value "10nF/50V")
      (footprint "eagle-import:C0603")
      (libsource (lib "eagle-import") (part "C0603"))
    )
    (comp (ref "C74")
      (value "10nF/50V")
      (footprint "eagle-import:C0603")
      (libsource (lib "eagle-import") (part "C0603"))
    )
    (comp (ref "C75")
      (value "10nF/50V")
      (footprint "eagle-import:C0603")
      (libsource (lib "eagle-import") (part "C0603"))
    )
    (comp (ref "C76")
      (value "100nF/50V")
      (footprint "eagle-import:C0603")
      (libsource (lib "eagle-import") (part "C0603"))
    )
    (comp (ref "C77")
      (value "100nF/50V")
      (footprint "eagle-import:C0603")
      (libsource (lib "eagle-import") (part "C0603"))
    )
    (comp (ref "C78")
      (value "100nF/50V")
      (footprint "eagle-import:C0603")
      (libsource (lib "eagle-import") (part "C0603"))
    )
    (comp (ref "CON4")
      (value "CON-HARTING-26V")
      (footprint "eagle-import:26V")
      (libsource (lib "eagle-import") (part "CON-HARTING-26V"))
    )
    (comp (ref "EC1")
      (value "220uF/50V")
      (footprint "eagle-import:UD-8X10_NICHICON")
      (libsource (lib "eagle-import") (part "CPOLUD-8X10"))
    )
    (comp (ref "EC2")
      (value "220uF/50V")
      (footprint "eagle-import:UD-8X10_NICHICON")
      (libsource (lib "eagle-import") (part "CPOLUD-8X10"))
    )
    (comp (ref "EC3")
      (value "220uF/50V")
      (footprint "eagle-import:UD-8X10_NICHICON")
      (libsource (lib "eagle-import") (part "CPOLUD-8X10"))
    )
    (comp (ref "IC6")
      (value "ULN2803")
      (footprint "eagle-import:SO18W")
      (libsource (lib "eagle-import") (part "ULN2803A-SO18W"))
    )
    (comp (ref "IC7")
      (value "ULN2803")
      (footprint "eagle-import:SO18W")
      (libsource (lib "eagle-import") (part "ULN2803A-SO18W"))
    )
    (comp (ref "IC8")
      (value "ULN2803")
      (footprint "eagle-import:SO18W")
      (libsource (lib "eagle-import") (part "ULN2803A-SO18W"))
    )
    (comp (ref "OK1")
      (value "TLP283-4")
      (footprint "eagle-import:MINI-FLAT-16")
      (libsource (lib "eagle-import") (part "TLP283-4"))
    )
    (comp (ref "OK2")
      (value "TLP283-4")
      (footprint "eagle-import:MINI-FLAT-16")
      (libsource (lib "eagle-import") (part "TLP283-4"))
    )
    (comp (ref "OK3")
      (value "TLP283-4")
      (footprint "eagle-import:MINI-FLAT-16")
      (libsource (lib "eagle-import") (part "TLP283-4"))
    )
    (comp (ref "OK4")
      (value "TLP283-4")
      (footprint "eagle-import:MINI-FLAT-16")
      (libsource (lib "eagle-import") (part "TLP283-4"))
    )
    (comp (ref "OK5")
      (value "TLP283-4")
      (footprint "eagle-import:MINI-FLAT-16")
      (libsource (lib "eagle-import") (part "TLP283-4"))
    )
    (comp (ref "OK6")
      (value "TLP283-4")
      (footprint "eagle-import:MINI-FLAT-16")
      (libsource (lib "eagle-import") (part "TLP283-4"))
    )
    (comp (ref "R40")
      (value "330R")
      (footprint "eagle-import:R0603")
      (libsource (lib "eagle-import") (part "R0603"))
    )
    (comp (ref "R41")
      (value "330R")
      (footprint "eagle-import:R0603")
      (libsource (lib "eagle-import") (part "R0603"))
    )
    (comp (ref "R42")
      (value "330R")
      (footprint "eagle-import:R0603")
      (libsource (lib "eagle-import") (part "R0603"))
    )
    (comp (ref "R43")
      (value "330R")
      (footprint "eagle-import:R0603")
      (libsource (lib "eagle-import") (part "R0603"))
    )
    (comp (ref "R44")
      (value "330R")
      (footprint "eagle-import:R0603")
      (libsource (lib "eagle-import") (part "R0603"))
    )
    (comp (ref "R45")
      (value "330R")
      (footprint "eagle-import:R0603")
      (libsource (lib "eagle-import") (part "R0603"))
    )
    (comp (ref "R46")
      (value "330R")
      (footprint "eagle-import:R0603")
      (libsource (lib "eagle-import") (part "R0603"))
    )
    (comp (ref "R47")
      (value "330R")
      (footprint "eagle-import:R0603")
      (libsource (lib "eagle-import") (part "R0603"))
    )
    (comp (ref "R48")
      (value "20K")
      (footprint "eagle-import:R0603")
      (libsource (lib "eagle-import") (part "R0603"))
    )
    (comp (ref "R49")
      (value "20K")
      (footprint "eagle-import:R0603")
      (libsource (lib "eagle-import") (part "R0603"))
    )
    (comp (ref "R50")
      (value "20K")
      (footprint "eagle-import:R0603")
      (libsource (lib "eagle-import") (part "R0603"))
    )
    (comp (ref "R51")
      (value "20K")
      (footprint "eagle-import:R0603")
      (libsource (lib "eagle-import") (part "R0603"))
    )
    (comp (ref "R52")
      (value "20K")
      (footprint "eagle-import:R0603")
      (libsource (lib "eagle-import") (part "R0603"))
    )
    (comp (ref "R53")
      (value "20K")
      (footprint "eagle-import:R0603")
      (libsource (lib "eagle-import") (part "R0603"))
    )
    (comp (ref "R54")
      (value "20K")
      (footprint "eagle-import:R0603")
      (libsource (lib "eagle-import") (part "R0603"))
    )
    (comp (ref "R55")
      (value "20K")
      (footprint "eagle-import:R0603")
      (libsource (lib "eagle-import") (part "R0603"))
    )
    (comp (ref "R56")
      (value "330R")
      (footprint "eagle-import:R0603")
      (libsource (lib "eagle-import") (part "R0603"))
    )
    (comp (ref "R57")
      (value "330R")
      (footprint "eagle-import:R0603")
      (libsource (lib "eagle-import") (part "R0603"))
    )
    (comp (ref "R58")
      (value "330R")
      (footprint "eagle-import:R0603")
      (libsource (lib "eagle-import") (part "R0603"))
    )
    (comp (ref "R59")
      (value "330R")
      (footprint "eagle-import:R0603")
      (libsource (lib "eagle-import") (part "R0603"))
    )
    (comp (ref "R60")
      (value "330R")
      (footprint "eagle-import:R0603")
      (libsource (lib "eagle-import") (part "R0603"))
    )
    (comp (ref "R61")
      (value "330R")
      (footprint "eagle-import:R0603")
      (libsource (lib "eagle-import") (part "R0603"))
    )
    (comp (ref "R62")
      (value "330R")
      (footprint "eagle-import:R0603")
      (libsource (lib "eagle-import") (part "R0603"))
    )
    (comp (ref "R63")
      (value "330R")
      (footprint "eagle-import:R0603")
      (libsource (lib "eagle-import") (part "R0603"))
    )
    (comp (ref "R64")
      (value "20K")
      (footprint "eagle-import:R0603")
      (libsource (lib "eagle-import") (part "R0603"))
    )
    (comp (ref "R65")
      (value "20K")
      (footprint "eagle-import:R0603")
      (libsource (lib "eagle-import") (part "R0603"))
    )
    (comp (ref "R66")
      (value "20K")
      (footprint "eagle-import:R0603")
      (libsource (lib "eagle-import") (part "R0603"))
    )
    (comp (ref "R67")
      (value "20K")
      (footprint "eagle-import:R0603")
      (libsource (lib "eagle-import") (part "R0603"))
    )
    (comp (ref "R68")
      (value "20K")
      (footprint "eagle-import:R0603")
      (libsource (lib "eagle-import") (part "R0603"))
    )
    (comp (ref "R69")
      (value "20K")
      (footprint "eagle-import:R0603")
      (libsource (lib "eagle-import") (part "R0603"))
    )
    (comp (ref "R70")
      (value "20K")
      (footprint "eagle-import:R0603")
      (libsource (lib "eagle-import") (part "R0603"))
    )
    (comp (ref "R71")
      (value "20K")
      (footprint "eagle-import:R0603")
      (libsource (lib "eagle-import") (part "R0603"))
    )
    (comp (ref "R72")
      (value "330R")
      (footprint "eagle-import:R0603")
      (libsource (lib "eagle-import") (part "R0603"))
    )
    (comp (ref "R73")
      (value "330R")
      (footprint "eagle-import:R0603")
      (libsource (lib "eagle-import") (part "R0603"))
    )
    (comp (ref "R74")
      (value "330R")
      (footprint "eagle-import:R0603")
      (libsource (lib "eagle-import") (part "R0603"))
    )
    (comp (ref "R75")
      (value "330R")
      (footprint "eagle-import:R0603")
      (libsource (lib "eagle-import") (part "R0603"))
    )
    (comp (ref "R76")
      (value "330R")
      (footprint "eagle-import:R0603")
      (libsource (lib "eagle-import") (part "R0603"))
    )
    (comp (ref "R77")
      (value "330R")
      (footprint "eagle-import:R0603")
      (libsource (lib "eagle-import") (part "R0603"))
    )
    (comp (ref "R78")
      (value "330R")
      (footprint "eagle-import:R0603")
      (libsource (lib "eagle-import") (part "R0603"))
    )
    (comp (ref "R79")
      (value "330R")
      (footprint "eagle-import:R0603")
      (libsource (lib "eagle-import") (part "R0603"))
    )
    (comp (ref "R80")
      (value "20K")
      (footprint "eagle-import:R0603")
      (libsource (lib "eagle-import") (part "R0603"))
    )
    (comp (ref "R81")
      (value "20K")
      (footprint "eagle-import:R0603")
      (libsource (lib "eagle-import") (part "R0603"))
    )
    (comp (ref "R82")
      (value "20K")
      (footprint "eagle-import:R0603")
      (libsource (lib "eagle-import") (part "R0603"))
    )
    (comp (ref "R83")
      (value "20K")
      (footprint "eagle-import:R0603")
      (libsource (lib "eagle-import") (part "R0603"))
    )
    (comp (ref "R84")
      (value "20K")
      (footprint "eagle-import:R0603")
      (libsource (lib "eagle-import") (part "R0603"))
    )
    (comp (ref "R85")
      (value "20K")
      (footprint "eagle-import:R0603")
      (libsource (lib "eagle-import") (part "R0603"))
    )
    (comp (ref "R86")
      (value "20K")
      (footprint "eagle-import:R0603")
      (libsource (lib "eagle-import") (part "R0603"))
    )
    (comp (ref "R87")
      (value "20K")
      (footprint "eagle-import:R0603")
      (libsource (lib "eagle-import") (part "R0603"))
    )
    (comp (ref "C79")
      (value "10nF/50V")
      (footprint "eagle-import:C0603")
      (libsource (lib "eagle-import") (part "C0603"))
    )
    (comp (ref "C80")
      (value "10nF/50V")
      (footprint "eagle-import:C0603")
      (libsource (lib "eagle-import") (part "C0603"))
    )
    (comp (ref "C81")
      (value "10nF/50V")
      (footprint "eagle-import:C0603")
      (libsource (lib "eagle-import") (part "C0603"))
    )
    (comp (ref "C82")
      (value "10nF/50V")
      (footprint "eagle-import:C0603")
      (libsource (lib "eagle-import") (part "C0603"))
    )
    (comp (ref "C83")
      (value "10nF/50V")
      (footprint "eagle-import:C0603")
      (libsource (lib "eagle-import") (part "C0603"))
    )
    (comp (ref "C84")
      (value "10nF/50V")
      (footprint "eagle-import:C0603")
      (libsource (lib "eagle-import") (part "C0603"))
    )
    (comp (ref "C85")
      (value "10nF/50V")
      (footprint "eagle-import:C0603")
      (libsource (lib "eagle-import") (part "C0603"))
    )
    (comp (ref "C86")
      (value "10nF/50V")
      (footprint "eagle-import:C0603")
      (libsource (lib "eagle-import") (part "C0603"))
    )
    (comp (ref "C87")
      (value "10nF/50V")
      (footprint "eagle-import:C0603")
      (libsource (lib "eagle-import") (part "C0603"))
    )
    (comp (ref "C88")
      (value "10nF/50V")
      (footprint "eagle-import:C0603")
      (libsource (lib "eagle-import") (part "C0603"))
    )
    (comp (ref "C89")
      (value "10nF/50V")
      (footprint "eagle-import:C0603")
      (libsource (lib "eagle-import") (part "C0603"))
    )
    (comp (ref "C90")
      (value "10nF/50V")
      (footprint "eagle-import:C0603")
      (libsource (lib "eagle-import") (part "C0603"))
    )
    (comp (ref "C91")
      (value "10nF/50V")
      (footprint "eagle-import:C0603")
      (libsource (lib "eagle-import") (part "C0603"))
    )
    (comp (ref "C92")
      (value "10nF/50V")
      (footprint "eagle-import:C0603")
      (libsource (lib "eagle-import") (part "C0603"))
    )
    (comp (ref "C93")
      (value "10nF/50V")
      (footprint "eagle-import:C0603")
      (libsource (lib "eagle-import") (part "C0603"))
    )
    (comp (ref "C94")
      (value "10nF/50V")
      (footprint "eagle-import:C0603")
      (libsource (lib "eagle-import") (part "C0603"))
    )
    (comp (ref "C95")
      (value "10nF/50V")
      (footprint "eagle-import:C0603")
      (libsource (lib "eagle-import") (part "C0603"))
    )
    (comp (ref "C96")
      (value "10nF/50V")
      (footprint "eagle-import:C0603")
      (libsource (lib "eagle-import") (part "C0603"))
    )
    (comp (ref "C97")
      (value "10nF/50V")
      (footprint "eagle-import:C0603")
      (libsource (lib "eagle-import") (part "C0603"))
    )
    (comp (ref "C98")
      (value "10nF/50V")
      (footprint "eagle-import:C0603")
      (libsource (lib "eagle-import") (part "C0603"))
    )
    (comp (ref "D2")
      (value "1N4148")
      (footprint "eagle-import:MINI_MELF(LL-34)")
      (libsource (lib "eagle-import") (part "1N4148"))
    )
    (comp (ref "D3")
      (value "1N4148")
      (footprint "eagle-import:MINI_MELF(LL-34)")
      (libsource (lib "eagle-import") (part "1N4148"))
    )
    (comp (ref "D4")
      (value "1N4148")
      (footprint "eagle-import:MINI_MELF(LL-34)")
      (libsource (lib "eagle-import") (part "1N4148"))
    )
    (comp (ref "D5")
      (value "1N4148")
      (footprint "eagle-import:MINI_MELF(LL-34)")
      (libsource (lib "eagle-import") (part "1N4148"))
    )
    (comp (ref "D6")
      (value "1N4148")
      (footprint "eagle-import:MINI_MELF(LL-34)")
      (libsource (lib "eagle-import") (part "1N4148"))
    )
    (comp (ref "D7")
      (value "1N4148")
      (footprint "eagle-import:MINI_MELF(LL-34)")
      (libsource (lib "eagle-import") (part "1N4148"))
    )
    (comp (ref "D8")
      (value "1N4148")
      (footprint "eagle-import:MINI_MELF(LL-34)")
      (libsource (lib "eagle-import") (part "1N4148"))
    )
    (comp (ref "D9")
      (value "1N4148")
      (footprint "eagle-import:MINI_MELF(LL-34)")
      (libsource (lib "eagle-import") (part "1N4148"))
    )
    (comp (ref "D10")
      (value "1N4148")
      (footprint "eagle-import:MINI_MELF(LL-34)")
      (libsource (lib "eagle-import") (part "1N4148"))
    )
    (comp (ref "D11")
      (value "1N4148")
      (footprint "eagle-import:MINI_MELF(LL-34)")
      (libsource (lib "eagle-import") (part "1N4148"))
    )
    (comp (ref "D12")
      (value "1N4148")
      (footprint "eagle-import:MINI_MELF(LL-34)")
      (libsource (lib "eagle-import") (part "1N4148"))
    )
    (comp (ref "D13")
      (value "1N4148")
      (footprint "eagle-import:MINI_MELF(LL-34)")
      (libsource (lib "eagle-import") (part "1N4148"))
    )
    (comp (ref "D14")
      (value "1N4148")
      (footprint "eagle-import:MINI_MELF(LL-34)")
      (libsource (lib "eagle-import") (part "1N4148"))
    )
    (comp (ref "D15")
      (value "1N4148")
      (footprint "eagle-import:MINI_MELF(LL-34)")
      (libsource (lib "eagle-import") (part "1N4148"))
    )
    (comp (ref "D16")
      (value "1N4148")
      (footprint "eagle-import:MINI_MELF(LL-34)")
      (libsource (lib "eagle-import") (part "1N4148"))
    )
    (comp (ref "D17")
      (value "1N4148")
      (footprint "eagle-import:MINI_MELF(LL-34)")
      (libsource (lib "eagle-import") (part "1N4148"))
    )
    (comp (ref "D18")
      (value "1N4148")
      (footprint "eagle-import:MINI_MELF(LL-34)")
      (libsource (lib "eagle-import") (part "1N4148"))
    )
    (comp (ref "D19")
      (value "1N4148")
      (footprint "eagle-import:MINI_MELF(LL-34)")
      (libsource (lib "eagle-import") (part "1N4148"))
    )
    (comp (ref "D20")
      (value "1N4148")
      (footprint "eagle-import:MINI_MELF(LL-34)")
      (libsource (lib "eagle-import") (part "1N4148"))
    )
    (comp (ref "D21")
      (value "1N4148")
      (footprint "eagle-import:MINI_MELF(LL-34)")
      (libsource (lib "eagle-import") (part "1N4148"))
    )
    (comp (ref "OK7")
      (value "TLP283-4")
      (footprint "eagle-import:MINI-FLAT-16")
      (libsource (lib "eagle-import") (part "TLP283-4"))
    )
    (comp (ref "OK8")
      (value "TLP283-4")
      (footprint "eagle-import:MINI-FLAT-16")
      (libsource (lib "eagle-import") (part "TLP283-4"))
    )
    (comp (ref "OK9")
      (value "TLP283-4")
      (footprint "eagle-import:MINI-FLAT-16")
      (libsource (lib "eagle-import") (part "TLP283-4"))
    )
    (comp (ref "OK10")
      (value "TLP283-4")
      (footprint "eagle-import:MINI-FLAT-16")
      (libsource (lib "eagle-import") (part "TLP283-4"))
    )
    (comp (ref "OK11")
      (value "TLP283-4")
      (footprint "eagle-import:MINI-FLAT-16")
      (libsource (lib "eagle-import") (part "TLP283-4"))
    )
    (comp (ref "R88")
      (value "2.2k")
      (footprint "eagle-import:R1206")
      (libsource (lib "eagle-import") (part "R1206"))
    )
    (comp (ref "R89")
      (value "2.2k")
      (footprint "eagle-import:R1206")
      (libsource (lib "eagle-import") (part "R1206"))
    )
    (comp (ref "R90")
      (value "2.2k")
      (footprint "eagle-import:R1206")
      (libsource (lib "eagle-import") (part "R1206"))
    )
    (comp (ref "R91")
      (value "2.2k")
      (footprint "eagle-import:R1206")
      (libsource (lib "eagle-import") (part "R1206"))
    )
    (comp (ref "R92")
      (value "2.2k")
      (footprint "eagle-import:R1206")
      (libsource (lib "eagle-import") (part "R1206"))
    )
    (comp (ref "R93")
      (value "2.2k")
      (footprint "eagle-import:R1206")
      (libsource (lib "eagle-import") (part "R1206"))
    )
    (comp (ref "R94")
      (value "2.2k")
      (footprint "eagle-import:R1206")
      (libsource (lib "eagle-import") (part "R1206"))
    )
    (comp (ref "R95")
      (value "2.2k")
      (footprint "eagle-import:R1206")
      (libsource (lib "eagle-import") (part "R1206"))
    )
    (comp (ref "R96")
      (value "10K")
      (footprint "eagle-import:R0603")
      (libsource (lib "eagle-import") (part "R0603"))
    )
    (comp (ref "R97")
      (value "10K")
      (footprint "eagle-import:R0603")
      (libsource (lib "eagle-import") (part "R0603"))
    )
    (comp (ref "R98")
      (value "10K")
      (footprint "eagle-import:R0603")
      (libsource (lib "eagle-import") (part "R0603"))
    )
    (comp (ref "R99")
      (value "10K")
      (footprint "eagle-import:R0603")
      (libsource (lib "eagle-import") (part "R0603"))
    )
    (comp (ref "R100")
      (value "2.2k")
      (footprint "eagle-import:R1206")
      (libsource (lib "eagle-import") (part "R1206"))
    )
    (comp (ref "R101")
      (value "2.2k")
      (footprint "eagle-import:R1206")
      (libsource (lib "eagle-import") (part "R1206"))
    )
    (comp (ref "R102")
      (value "2.2k")
      (footprint "eagle-import:R1206")
      (libsource (lib "eagle-import") (part "R1206"))
    )
    (comp (ref "R103")
      (value "2.2k")
      (footprint "eagle-import:R1206")
      (libsource (lib "eagle-import") (part "R1206"))
    )
    (comp (ref "R104")
      (value "2.2k")
      (footprint "eagle-import:R1206")
      (libsource (lib "eagle-import") (part "R1206"))
    )
    (comp (ref "R105")
      (value "2.2k")
      (footprint "eagle-import:R1206")
      (libsource (lib "eagle-import") (part "R1206"))
    )
    (comp (ref "R106")
      (value "2.2k")
      (footprint "eagle-import:R1206")
      (libsource (lib "eagle-import") (part "R1206"))
    )
    (comp (ref "R107")
      (value "2.2k")
      (footprint "eagle-import:R1206")
      (libsource (lib "eagle-import") (part "R1206"))
    )
    (comp (ref "R108")
      (value "10K")
      (footprint "eagle-import:R0603")
      (libsource (lib "eagle-import") (part "R0603"))
    )
    (comp (ref "R109")
      (value "10K")
      (footprint "eagle-import:R0603")
      (libsource (lib "eagle-import") (part "R0603"))
    )
    (comp (ref "R110")
      (value "10K")
      (footprint "eagle-import:R0603")
      (libsource (lib "eagle-import") (part "R0603"))
    )
    (comp (ref "R111")
      (value "10K")
      (footprint "eagle-import:R0603")
      (libsource (lib "eagle-import") (part "R0603"))
    )
    (comp (ref "R112")
      (value "2.2k")
      (footprint "eagle-import:R1206")
      (libsource (lib "eagle-import") (part "R1206"))
    )
    (comp (ref "R113")
      (value "2.2k")
      (footprint "eagle-import:R1206")
      (libsource (lib "eagle-import") (part "R1206"))
    )
    (comp (ref "R114")
      (value "2.2k")
      (footprint "eagle-import:R1206")
      (libsource (lib "eagle-import") (part "R1206"))
    )
    (comp (ref "R115")
      (value "2.2k")
      (footprint "eagle-import:R1206")
      (libsource (lib "eagle-import") (part "R1206"))
    )
    (comp (ref "R116")
      (value "2.2k")
      (footprint "eagle-import:R1206")
      (libsource (lib "eagle-import") (part "R1206"))
    )
    (comp (ref "R117")
      (value "2.2k")
      (footprint "eagle-import:R1206")
      (libsource (lib "eagle-import") (part "R1206"))
    )
    (comp (ref "R118")
      (value "2.2k")
      (footprint "eagle-import:R1206")
      (libsource (lib "eagle-import") (part "R1206"))
    )
    (comp (ref "R119")
      (value "2.2k")
      (footprint "eagle-import:R1206")
      (libsource (lib "eagle-import") (part "R1206"))
    )
    (comp (ref "R120")
      (value "10K")
      (footprint "eagle-import:R0603")
      (libsource (lib "eagle-import") (part "R0603"))
    )
    (comp (ref "R121")
      (value "10K")
      (footprint "eagle-import:R0603")
      (libsource (lib "eagle-import") (part "R0603"))
    )
    (comp (ref "R122")
      (value "10K")
      (footprint "eagle-import:R0603")
      (libsource (lib "eagle-import") (part "R0603"))
    )
    (comp (ref "R123")
      (value "10K")
      (footprint "eagle-import:R0603")
      (libsource (lib "eagle-import") (part "R0603"))
    )
    (comp (ref "R124")
      (value "2.2k")
      (footprint "eagle-import:R1206")
      (libsource (lib "eagle-import") (part "R1206"))
    )
    (comp (ref "R125")
      (value "2.2k")
      (footprint "eagle-import:R1206")
      (libsource (lib "eagle-import") (part "R1206"))
    )
    (comp (ref "R126")
      (value "2.2k")
      (footprint "eagle-import:R1206")
      (libsource (lib "eagle-import") (part "R1206"))
    )
    (comp (ref "R127")
      (value "2.2k")
      (footprint "eagle-import:R1206")
      (libsource (lib "eagle-import") (part "R1206"))
    )
    (comp (ref "R128")
      (value "2.2k")
      (footprint "eagle-import:R1206")
      (libsource (lib "eagle-import") (part "R1206"))
    )
    (comp (ref "R129")
      (value "2.2k")
      (footprint "eagle-import:R1206")
      (libsource (lib "eagle-import") (part "R1206"))
    )
    (comp (ref "R130")
      (value "2.2k")
      (footprint "eagle-import:R1206")
      (libsource (lib "eagle-import") (part "R1206"))
    )
    (comp (ref "R131")
      (value "2.2k")
      (footprint "eagle-import:R1206")
      (libsource (lib "eagle-import") (part "R1206"))
    )
    (comp (ref "R132")
      (value "10K")
      (footprint "eagle-import:R0603")
      (libsource (lib "eagle-import") (part "R0603"))
    )
    (comp (ref "R133")
      (value "10K")
      (footprint "eagle-import:R0603")
      (libsource (lib "eagle-import") (part "R0603"))
    )
    (comp (ref "R134")
      (value "10K")
      (footprint "eagle-import:R0603")
      (libsource (lib "eagle-import") (part "R0603"))
    )
    (comp (ref "R135")
      (value "10K")
      (footprint "eagle-import:R0603")
      (libsource (lib "eagle-import") (part "R0603"))
    )
    (comp (ref "R136")
      (value "2.2k")
      (footprint "eagle-import:R1206")
      (libsource (lib "eagle-import") (part "R1206"))
    )
    (comp (ref "R137")
      (value "2.2k")
      (footprint "eagle-import:R1206")
      (libsource (lib "eagle-import") (part "R1206"))
    )
    (comp (ref "R138")
      (value "2.2k")
      (footprint "eagle-import:R1206")
      (libsource (lib "eagle-import") (part "R1206"))
    )
    (comp (ref "R139")
      (value "2.2k")
      (footprint "eagle-import:R1206")
      (libsource (lib "eagle-import") (part "R1206"))
    )
    (comp (ref "R140")
      (value "2.2k")
      (footprint "eagle-import:R1206")
      (libsource (lib "eagle-import") (part "R1206"))
    )
    (comp (ref "R141")
      (value "2.2k")
      (footprint "eagle-import:R1206")
      (libsource (lib "eagle-import") (part "R1206"))
    )
    (comp (ref "R142")
      (value "2.2k")
      (footprint "eagle-import:R1206")
      (libsource (lib "eagle-import") (part "R1206"))
    )
    (comp (ref "R143")
      (value "2.2k")
      (footprint "eagle-import:R1206")
      (libsource (lib "eagle-import") (part "R1206"))
    )
    (comp (ref "R144")
      (value "10K")
      (footprint "eagle-import:R0603")
      (libsource (lib "eagle-import") (part "R0603"))
    )
    (comp (ref "R145")
      (value "10K")
      (footprint "eagle-import:R0603")
      (libsource (lib "eagle-import") (part "R0603"))
    )
    (comp (ref "R146")
      (value "10K")
      (footprint "eagle-import:R0603")
      (libsource (lib "eagle-import") (part "R0603"))
    )
    (comp (ref "R147")
      (value "10K")
      (footprint "eagle-import:R0603")
      (libsource (lib "eagle-import") (part "R0603"))
    )
    (comp (ref "X2")
      (value "FFKDS/V1-5.08_FIRST")
      (footprint "eagle-import:FFKDS_V1-5,08-1_FIRST")
      (libsource (lib "eagle-import") (part "FFKDS/V1-5.08_FIRST"))
    )
    (comp (ref "X3")
      (value "FFKDS/V1-5.08_MIDDLE")
      (footprint "eagle-import:FFKDS_V1-5,08-1_MIDDLE")
      (libsource (lib "eagle-import") (part "FFKDS/V1-5.08_MIDDLE"))
    )
    (comp (ref "X4")
      (value "FFKDS/V1-5.08_MIDDLE")
      (footprint "eagle-import:FFKDS_V1-5,08-1_MIDDLE")
      (libsource (lib "eagle-import") (part "FFKDS/V1-5.08_MIDDLE"))
    )
    (comp (ref "X5")
      (value "FFKDS/V1-5.08_MIDDLE")
      (footprint "eagle-import:FFKDS_V1-5,08-1_MIDDLE")
      (libsource (lib "eagle-import") (part "FFKDS/V1-5.08_MIDDLE"))
    )
    (comp (ref "X6")
      (value "FFKDS/V1-5.08_MIDDLE")
      (footprint "eagle-import:FFKDS_V1-5,08-1_MIDDLE")
      (libsource (lib "eagle-import") (part "FFKDS/V1-5.08_MIDDLE"))
    )
    (comp (ref "X7")
      (value "FFKDS/V1-5.08_MIDDLE")
      (footprint "eagle-import:FFKDS_V1-5,08-1_MIDDLE")
      (libsource (lib "eagle-import") (part "FFKDS/V1-5.08_MIDDLE"))
    )
    (comp (ref "X8")
      (value "FFKDS/V1-5.08_MIDDLE")
      (footprint "eagle-import:FFKDS_V1-5,08-1_MIDDLE")
      (libsource (lib "eagle-import") (part "FFKDS/V1-5.08_MIDDLE"))
    )
    (comp (ref "X9")
      (value "FFKDS/V1-5.08_MIDDLE")
      (footprint "eagle-import:FFKDS_V1-5,08-1_MIDDLE")
      (libsource (lib "eagle-import") (part "FFKDS/V1-5.08_MIDDLE"))
    )
    (comp (ref "X10")
      (value "FFKDS/V1-5.08_MIDDLE")
      (footprint "eagle-import:FFKDS_V1-5,08-1_MIDDLE")
      (libsource (lib "eagle-import") (part "FFKDS/V1-5.08_MIDDLE"))
    )
    (comp (ref "X11")
      (value "FFKDS/V1-5.08_MIDDLE")
      (footprint "eagle-import:FFKDS_V1-5,08-1_MIDDLE")
      (libsource (lib "eagle-import") (part "FFKDS/V1-5.08_MIDDLE"))
    )
    (comp (ref "X12")
      (value "FFKDS/V1-5.08_MIDDLE")
      (footprint "eagle-import:FFKDS_V1-5,08-1_MIDDLE")
      (libsource (lib "eagle-import") (part "FFKDS/V1-5.08_MIDDLE"))
    )
    (comp (ref "X13")
      (value "FFKDS/V1-5.08_MIDDLE")
      (footprint "eagle-import:FFKDS_V1-5,08-1_MIDDLE")
      (libsource (lib "eagle-import") (part "FFKDS/V1-5.08_MIDDLE"))
    )
    (comp (ref "X14")
      (value "FFKDS/V1-5.08_MIDDLE")
      (footprint "eagle-import:FFKDS_V1-5,08-1_MIDDLE")
      (libsource (lib "eagle-import") (part "FFKDS/V1-5.08_MIDDLE"))
    )
    (comp (ref "X15")
      (value "FFKDS/V1-5.08_MIDDLE")
      (footprint "eagle-import:FFKDS_V1-5,08-1_MIDDLE")
      (libsource (lib "eagle-import") (part "FFKDS/V1-5.08_MIDDLE"))
    )
    (comp (ref "X16")
      (value "FFKDS/V1-5.08_MIDDLE")
      (footprint "eagle-import:FFKDS_V1-5,08-1_MIDDLE")
      (libsource (lib "eagle-import") (part "FFKDS/V1-5.08_MIDDLE"))
    )
    (comp (ref "X17")
      (value "FFKDS/V1-5.08_MIDDLE")
      (footprint "eagle-import:FFKDS_V1-5,08-1_MIDDLE")
      (libsource (lib "eagle-import") (part "FFKDS/V1-5.08_MIDDLE"))
    )
    (comp (ref "X18")
      (value "FFKDS/V1-5.08_MIDDLE")
      (footprint "eagle-import:FFKDS_V1-5,08-1_MIDDLE")
      (libsource (lib "eagle-import") (part "FFKDS/V1-5.08_MIDDLE"))
    )
    (comp (ref "X19")
      (value "FFKDS/V1-5.08_MIDDLE")
      (footprint "eagle-import:FFKDS_V1-5,08-1_MIDDLE")
      (libsource (lib "eagle-import") (part "FFKDS/V1-5.08_MIDDLE"))
    )
    (comp (ref "X20")
      (value "FFKDS/V1-5.08_MIDDLE")
      (footprint "eagle-import:FFKDS_V1-5,08-1_MIDDLE")
      (libsource (lib "eagle-import") (part "FFKDS/V1-5.08_MIDDLE"))
    )
    (comp (ref "X21")
      (value "FFKDS/V1-5.08_MIDDLE")
      (footprint "eagle-import:FFKDS_V1-5,08-1_MIDDLE")
      (libsource (lib "eagle-import") (part "FFKDS/V1-5.08_MIDDLE"))
    )
    (comp (ref "X22")
      (value "FFKDS/V1-5.08_MIDDLE")
      (footprint "eagle-import:FFKDS_V1-5,08-1_MIDDLE")
      (libsource (lib "eagle-import") (part "FFKDS/V1-5.08_MIDDLE"))
    )
    (comp (ref "X23")
      (value "FFKDS/V1-5.08_MIDDLE")
      (footprint "eagle-import:FFKDS_V1-5,08-1_MIDDLE")
      (libsource (lib "eagle-import") (part "FFKDS/V1-5.08_MIDDLE"))
    )
    (comp (ref "X24")
      (value "FFKDS/V1-5.08_MIDDLE")
      (footprint "eagle-import:FFKDS_V1-5,08-1_MIDDLE")
      (libsource (lib "eagle-import") (part "FFKDS/V1-5.08_MIDDLE"))
    )
    (comp (ref "X25")
      (value "FFKDS/V1-5.08_MIDDLE")
      (footprint "eagle-import:FFKDS_V1-5,08-1_MIDDLE")
      (libsource (lib "eagle-import") (part "FFKDS/V1-5.08_MIDDLE"))
    )
    (comp (ref "X26")
      (value "FFKDS/V1-5.08_MIDDLE")
      (footprint "eagle-import:FFKDS_V1-5,08-1_MIDDLE")
      (libsource (lib "eagle-import") (part "FFKDS/V1-5.08_MIDDLE"))
    )
    (comp (ref "X27")
      (value "FFKDS/V1-5.08_MIDDLE")
      (footprint "eagle-import:FFKDS_V1-5,08-1_MIDDLE")
      (libsource (lib "eagle-import") (part "FFKDS/V1-5.08_MIDDLE"))
    )
    (comp (ref "X28")
      (value "FFKDS/V1-5.08_MIDDLE")
      (footprint "eagle-import:FFKDS_V1-5,08-1_MIDDLE")
      (libsource (lib "eagle-import") (part "FFKDS/V1-5.08_MIDDLE"))
    )
    (comp (ref "X29")
      (value "FFKDS/V1-5.08_MIDDLE")
      (footprint "eagle-import:FFKDS_V1-5,08-1_MIDDLE")
      (libsource (lib "eagle-import") (part "FFKDS/V1-5.08_MIDDLE"))
    )
    (comp (ref "X30")
      (value "FFKDS/V1-5.08_MIDDLE")
      (footprint "eagle-import:FFKDS_V1-5,08-1_MIDDLE")
      (libsource (lib "eagle-import") (part "FFKDS/V1-5.08_MIDDLE"))
    )
    (comp (ref "X31")
      (value "FFKDS/V1-5.08_MIDDLE")
      (footprint "eagle-import:FFKDS_V1-5,08-1_MIDDLE")
      (libsource (lib "eagle-import") (part "FFKDS/V1-5.08_MIDDLE"))
    )
    (comp (ref "X32")
      (value "FFKDS/V1-5.08_MIDDLE")
      (footprint "eagle-import:FFKDS_V1-5,08-1_MIDDLE")
      (libsource (lib "eagle-import") (part "FFKDS/V1-5.08_MIDDLE"))
    )
    (comp (ref "X33")
      (value "FFKDS/V1-5.08_MIDDLE")
      (footprint "eagle-import:FFKDS_V1-5,08-1_MIDDLE")
      (libsource (lib "eagle-import") (part "FFKDS/V1-5.08_MIDDLE"))
    )
    (comp (ref "X34")
      (value "FFKDS/V1-5.08_MIDDLE")
      (footprint "eagle-import:FFKDS_V1-5,08-1_MIDDLE")
      (libsource (lib "eagle-import") (part "FFKDS/V1-5.08_MIDDLE"))
    )
    (comp (ref "X35")
      (value "FFKDS/V1-5.08_MIDDLE")
      (footprint "eagle-import:FFKDS_V1-5,08-1_MIDDLE")
      (libsource (lib "eagle-import") (part "FFKDS/V1-5.08_MIDDLE"))
    )
    (comp (ref "X36")
      (value "FFKDS/V1-5.08_MIDDLE")
      (footprint "eagle-import:FFKDS_V1-5,08-1_MIDDLE")
      (libsource (lib "eagle-import") (part "FFKDS/V1-5.08_MIDDLE"))
    )
    (comp (ref "X37")
      (value "FFKDS/V1-5.08_MIDDLE")
      (footprint "eagle-import:FFKDS_V1-5,08-1_MIDDLE")
      (libsource (lib "eagle-import") (part "FFKDS/V1-5.08_MIDDLE"))
    )
    (comp (ref "X38")
      (value "FFKDS/V1-5.08_MIDDLE")
      (footprint "eagle-import:FFKDS_V1-5,08-1_MIDDLE")
      (libsource (lib "eagle-import") (part "FFKDS/V1-5.08_MIDDLE"))
    )
    (comp (ref "X39")
      (value "FFKDS/V1-5.08_MIDDLE")
      (footprint "eagle-import:FFKDS_V1-5,08-1_MIDDLE")
      (libsource (lib "eagle-import") (part "FFKDS/V1-5.08_MIDDLE"))
    )
    (comp (ref "X40")
      (value "FFKDS/V1-5.08_MIDDLE")
      (footprint "eagle-import:FFKDS_V1-5,08-1_MIDDLE")
      (libsource (lib "eagle-import") (part "FFKDS/V1-5.08_MIDDLE"))
    )
    (comp (ref "X41")
      (value "FFKDS/V1-5.08_LAST")
      (footprint "eagle-import:FFKDS_V1-5,08-1_LAST")
      (libsource (lib "eagle-import") (part "FFKDS/V1-5.08_LAST"))
    )
    (comp (ref "C99")
      (value "100nF/50V")
      (footprint "eagle-import:C0603")
      (libsource (lib "eagle-import") (part "C0603"))
    )
    (comp (ref "C100")
      (value "10uF/16V")
      (footprint "eagle-import:C0603")
      (libsource (lib "eagle-import") (part "C0603"))
    )
    (comp (ref "C101")
      (value "100nF/50V")
      (footprint "eagle-import:C0603")
      (libsource (lib "eagle-import") (part "C0603"))
    )
    (comp (ref "C102")
      (value "1000uF/16V_M10*16")
      (footprint "eagle-import:E3,5-10")
      (libsource (lib "eagle-import") (part "CPOL-EUE3.5-10"))
    )
    (comp (ref "C103")
      (value "100nF/50V")
      (footprint "eagle-import:C0603")
      (libsource (lib "eagle-import") (part "C0603"))
    )
    (comp (ref "C104")
      (value "220uF/16V_M10*16")
      (footprint "eagle-import:E3,5-10")
      (libsource (lib "eagle-import") (part "CPOL-EUE3.5-10"))
    )
    (comp (ref "C105")
      (value "100nF/50V")
      (footprint "eagle-import:C0603")
      (libsource (lib "eagle-import") (part "C0603"))
    )
    (comp (ref "C106")
      (value "100nF/50V")
      (footprint "eagle-import:C0603")
      (libsource (lib "eagle-import") (part "C0603"))
    )
    (comp (ref "C107")
      (value "100nF/50V")
      (footprint "eagle-import:C0603")
      (libsource (lib "eagle-import") (part "C0603"))
    )
    (comp (ref "C108")
      (value "100nF/50V")
      (footprint "eagle-import:C0603")
      (libsource (lib "eagle-import") (part "C0603"))
    )
    (comp (ref "C109")
      (value "100nF/50V")
      (footprint "eagle-import:C0603")
      (libsource (lib "eagle-import") (part "C0603"))
    )
    (comp (ref "C110")
      (value "30pF/50V")
      (footprint "eagle-import:C0603")
      (libsource (lib "eagle-import") (part "C0603"))
    )
    (comp (ref "C111")
      (value "30pF/50V")
      (footprint "eagle-import:C0603")
      (libsource (lib "eagle-import") (part "C0603"))
    )
    (comp (ref "C112")
      (value "30pF/50V")
      (footprint "eagle-import:C0603")
      (libsource (lib "eagle-import") (part "C0603"))
    )
    (comp (ref "C113")
      (value "30pF/50V")
      (footprint "eagle-import:C0603")
      (libsource (lib "eagle-import") (part "C0603"))
    )
    (comp (ref "C114")
      (value "100nF/50V")
      (footprint "eagle-import:C0603")
      (libsource (lib "eagle-import") (part "C0603"))
    )
    (comp (ref "C115")
      (value "1nF/50V")
      (footprint "eagle-import:C0603")
      (libsource (lib "eagle-import") (part "C0603"))
    )
    (comp (ref "C116")
      (value "1nF/50V")
      (footprint "eagle-import:C0603")
      (libsource (lib "eagle-import") (part "C0603"))
    )
    (comp (ref "C117")
      (value "1nF/50V")
      (footprint "eagle-import:C0603")
      (libsource (lib "eagle-import") (part "C0603"))
    )
    (comp (ref "C118")
      (value "1nF/50V")
      (footprint "eagle-import:C0603")
      (libsource (lib "eagle-import") (part "C0603"))
    )
    (comp (ref "C119")
      (value "10uF/16V")
      (footprint "eagle-import:C0603")
      (libsource (lib "eagle-import") (part "C0603"))
    )
    (comp (ref "C120")
      (value "2200uF/50V_M16*25")
      (footprint "eagle-import:E7,5-16")
      (libsource (lib "eagle-import") (part "CPOL-EUE7.5-16"))
    )
    (comp (ref "C121")
      (value "100nF/50V")
      (footprint "eagle-import:C0603")
      (libsource (lib "eagle-import") (part "C0603"))
    )
    (comp (ref "C122")
      (value "1000uF/50V_M16*25")
      (footprint "eagle-import:E7,5-16")
      (libsource (lib "eagle-import") (part "CPOL-EUE7.5-16"))
    )
    (comp (ref "C123")
      (value "100nF/50V")
      (footprint "eagle-import:C0603")
      (libsource (lib "eagle-import") (part "C0603"))
    )
    (comp (ref "C124")
      (value "100nF/50V")
      (footprint "eagle-import:C0603")
      (libsource (lib "eagle-import") (part "C0603"))
    )
    (comp (ref "C125")
      (value "100nF/50V")
      (footprint "eagle-import:C0603")
      (libsource (lib "eagle-import") (part "C0603"))
    )
    (comp (ref "C126")
      (value "100nF/50V")
      (footprint "eagle-import:C0603")
      (libsource (lib "eagle-import") (part "C0603"))
    )
    (comp (ref "C127")
      (value "100nF/50V")
      (footprint "eagle-import:C0603")
      (libsource (lib "eagle-import") (part "C0603"))
    )
    (comp (ref "C128")
      (value "30pF/50V")
      (footprint "eagle-import:C0603")
      (libsource (lib "eagle-import") (part "C0603"))
    )
    (comp (ref "C129")
      (value "30pF/50V")
      (footprint "eagle-import:C0603")
      (libsource (lib "eagle-import") (part "C0603"))
    )
    (comp (ref "C130")
      (value "30pF/50V")
      (footprint "eagle-import:C0603")
      (libsource (lib "eagle-import") (part "C0603"))
    )
    (comp (ref "C131")
      (value "30pF/50V")
      (footprint "eagle-import:C0603")
      (libsource (lib "eagle-import") (part "C0603"))
    )
    (comp (ref "C132")
      (value "1nF/50V")
      (footprint "eagle-import:C0603")
      (libsource (lib "eagle-import") (part "C0603"))
    )
    (comp (ref "C133")
      (value "1nF/50V")
      (footprint "eagle-import:C0603")
      (libsource (lib "eagle-import") (part "C0603"))
    )
    (comp (ref "C134")
      (value "1nF/50V")
      (footprint "eagle-import:C0603")
      (libsource (lib "eagle-import") (part "C0603"))
    )
    (comp (ref "C135")
      (value "1nF/50V")
      (footprint "eagle-import:C0603")
      (libsource (lib "eagle-import") (part "C0603"))
    )
    (comp (ref "C136")
      (value "100nF/50V")
      (footprint "eagle-import:C0603")
      (libsource (lib "eagle-import") (part "C0603"))
    )
    (comp (ref "C137")
      (value "10uF/16V")
      (footprint "eagle-import:C0603")
      (libsource (lib "eagle-import") (part "C0603"))
    )
    (comp (ref "C138")
      (value "100nF/50V")
      (footprint "eagle-import:C0603")
      (libsource (lib "eagle-import") (part "C0603"))
    )
    (comp (ref "C139")
      (value "100nF/50V")
      (footprint "eagle-import:C0603")
      (libsource (lib "eagle-import") (part "C0603"))
    )
    (comp (ref "C140")
      (value "100nF/50V")
      (footprint "eagle-import:C0603")
      (libsource (lib "eagle-import") (part "C0603"))
    )
    (comp (ref "C141")
      (value "100nF/50V")
      (footprint "eagle-import:C0603")
      (libsource (lib "eagle-import") (part "C0603"))
    )
    (comp (ref "C142")
      (value "30pF/50V")
      (footprint "eagle-import:C0603")
      (libsource (lib "eagle-import") (part "C0603"))
    )
    (comp (ref "C143")
      (value "30pF/50V")
      (footprint "eagle-import:C0603")
      (libsource (lib "eagle-import") (part "C0603"))
    )
    (comp (ref "C144")
      (value "30pF/50V")
      (footprint "eagle-import:C0603")
      (libsource (lib "eagle-import") (part "C0603"))
    )
    (comp (ref "C145")
      (value "30pF/50V")
      (footprint "eagle-import:C0603")
      (libsource (lib "eagle-import") (part "C0603"))
    )
    (comp (ref "C146")
      (value "100nF/50V")
      (footprint "eagle-import:C0603")
      (libsource (lib "eagle-import") (part "C0603"))
    )
    (comp (ref "C147")
      (value "10uF/16V")
      (footprint "eagle-import:C0603")
      (libsource (lib "eagle-import") (part "C0603"))
    )
    (comp (ref "C148")
      (value "1nF/50V")
      (footprint "eagle-import:C0603")
      (libsource (lib "eagle-import") (part "C0603"))
    )
    (comp (ref "C149")
      (value "1nF/50V")
      (footprint "eagle-import:C0603")
      (libsource (lib "eagle-import") (part "C0603"))
    )
    (comp (ref "C150")
      (value "1nF/50V")
      (footprint "eagle-import:C0603")
      (libsource (lib "eagle-import") (part "C0603"))
    )
    (comp (ref "C151")
      (value "1nF/50V")
      (footprint "eagle-import:C0603")
      (libsource (lib "eagle-import") (part "C0603"))
    )
    (comp (ref "C152")
      (value "CPOL-EUTT5D11")
      (footprint "eagle-import:TT5D11")
      (libsource (lib "eagle-import") (part "CPOL-EUTT5D11"))
    )
    (comp (ref "C153")
      (value "CPOL-EUTT5D11")
      (footprint "eagle-import:TT5D11")
      (libsource (lib "eagle-import") (part "CPOL-EUTT5D11"))
    )
    (comp (ref "D22")
      (value "1N4007")
      (footprint "eagle-import:SMA-DO214AC")
      (libsource (lib "eagle-import") (part "1N4007-M7"))
    )
    (comp (ref "D23")
      (value "1N4148")
      (footprint "eagle-import:MINI_MELF(LL-34)")
      (libsource (lib "eagle-import") (part "1N4148"))
    )
    (comp (ref "D24")
      (value "1N4148")
      (footprint "eagle-import:MINI_MELF(LL-34)")
      (libsource (lib "eagle-import") (part "1N4148"))
    )
    (comp (ref "D25")
      (value "1N4148")
      (footprint "eagle-import:MINI_MELF(LL-34)")
      (libsource (lib "eagle-import") (part "1N4148"))
    )
    (comp (ref "D26")
      (value "1N4148")
      (footprint "eagle-import:MINI_MELF(LL-34)")
      (libsource (lib "eagle-import") (part "1N4148"))
    )
    (comp (ref "D27")
      (value "1N4007")
      (footprint "eagle-import:SMA-DO214AC")
      (libsource (lib "eagle-import") (part "1N4007-M7"))
    )
    (comp (ref "D28")
      (value "1N4148")
      (footprint "eagle-import:MINI_MELF(LL-34)")
      (libsource (lib "eagle-import") (part "1N4148"))
    )
    (comp (ref "D29")
      (value "1N4148")
      (footprint "eagle-import:MINI_MELF(LL-34)")
      (libsource (lib "eagle-import") (part "1N4148"))
    )
    (comp (ref "D30")
      (value "1N4148")
      (footprint "eagle-import:MINI_MELF(LL-34)")
      (libsource (lib "eagle-import") (part "1N4148"))
    )
    (comp (ref "D31")
      (value "1N4148")
      (footprint "eagle-import:MINI_MELF(LL-34)")
      (libsource (lib "eagle-import") (part "1N4148"))
    )
    (comp (ref "D32")
      (value "1N4148")
      (footprint "eagle-import:MINI_MELF(LL-34)")
      (libsource (lib "eagle-import") (part "1N4148"))
    )
    (comp (ref "D33")
      (value "1N4148")
      (footprint "eagle-import:MINI_MELF(LL-34)")
      (libsource (lib "eagle-import") (part "1N4148"))
    )
    (comp (ref "D34")
      (value "1N4148")
      (footprint "eagle-import:MINI_MELF(LL-34)")
      (libsource (lib "eagle-import") (part "1N4148"))
    )
    (comp (ref "D35")
      (value "1N4148")
      (footprint "eagle-import:MINI_MELF(LL-34)")
      (libsource (lib "eagle-import") (part "1N4148"))
    )
    (comp (ref "DB1")
      (value "KBP2005G")
      (footprint "eagle-import:KBP2005")
      (libsource (lib "eagle-import") (part "KBP"))
    )
    (comp (ref "DB2")
      (value "KBP2005G")
      (footprint "eagle-import:KBP2005")
      (libsource (lib "eagle-import") (part "KBP"))
    )
    (comp (ref "IC9")
      (value "LM4040AIM3X-2.5")
      (footprint "eagle-import:SOT23-3")
      (libsource (lib "eagle-import") (part "LM4040AIM3X-2.5"))
    )
    (comp (ref "IC10")
      (value "LM1117IDTX-3.3")
      (footprint "eagle-import:TO252")
      (libsource (lib "eagle-import") (part "LM1117IDTX-3.3"))
    )
    (comp (ref "IC12")
      (value "SGM8584XS14")
      (footprint "eagle-import:SOIC-14")
      (libsource (lib "eagle-import") (part "SGM8584XS14"))
    )
    (comp (ref "IC13")
      (value "SGM8584XS14")
      (footprint "eagle-import:SOIC-14")
      (libsource (lib "eagle-import") (part "SGM8584XS14"))
    )
    (comp (ref "IC14")
      (value "LM78M24")
      (footprint "eagle-import:78XXS")
      (libsource (lib "eagle-import") (part "78XXS"))
    )
    (comp (ref "IC15")
      (value "SGM8584XS14")
      (footprint "eagle-import:SOIC-14")
      (libsource (lib "eagle-import") (part "SGM8584XS14"))
    )
    (comp (ref "IC16")
      (value "SGM8584XS14")
      (footprint "eagle-import:SOIC-14")
      (libsource (lib "eagle-import") (part "SGM8584XS14"))
    )
    (comp (ref "L8")
      (value "10uH")
      (footprint "eagle-import:L0603")
      (libsource (lib "eagle-import") (part "INDUCTOR/FERRITE-BEAD'0603'"))
    )
    (comp (ref "L9")
      (value "120R/100MHz 3A")
      (footprint "eagle-import:L0805")
      (libsource (lib "eagle-import") (part "INDUCTOR/FERRITE-BEAD'0805'"))
    )
    (comp (ref "L10")
      (value "10uH")
      (footprint "eagle-import:L0603")
      (libsource (lib "eagle-import") (part "INDUCTOR/FERRITE-BEAD'0603'"))
    )
    (comp (ref "L11")
      (value "10uH")
      (footprint "eagle-import:L0603")
      (libsource (lib "eagle-import") (part "INDUCTOR/FERRITE-BEAD'0603'"))
    )
    (comp (ref "L12")
      (value "10uH")
      (footprint "eagle-import:L0603")
      (libsource (lib "eagle-import") (part "INDUCTOR/FERRITE-BEAD'0603'"))
    )
    (comp (ref "R148")
      (value "10k")
      (footprint "eagle-import:R0603")
      (libsource (lib "eagle-import") (part "R0603"))
    )
    (comp (ref "R149")
      (value "10K")
      (footprint "eagle-import:R0603")
      (libsource (lib "eagle-import") (part "R0603"))
    )
    (comp (ref "R150")
      (value "120R/0.1%")
      (footprint "eagle-import:R1206")
      (libsource (lib "eagle-import") (part "R1206"))
    )
    (comp (ref "R151")
      (value "120R/0.1%")
      (footprint "eagle-import:R1206")
      (libsource (lib "eagle-import") (part "R1206"))
    )
    (comp (ref "R152")
      (value "120R/0.1%")
      (footprint "eagle-import:R1206")
      (libsource (lib "eagle-import") (part "R1206"))
    )
    (comp (ref "R153")
      (value "120R/0.1%")
      (footprint "eagle-import:R1206")
      (libsource (lib "eagle-import") (part "R1206"))
    )
    (comp (ref "R154")
      (value "10k")
      (footprint "eagle-import:R0603")
      (libsource (lib "eagle-import") (part "R0603"))
    )
    (comp (ref "R155")
      (value "10k")
      (footprint "eagle-import:R0603")
      (libsource (lib "eagle-import") (part "R0603"))
    )
    (comp (ref "R156")
      (value "10k")
      (footprint "eagle-import:R0603")
      (libsource (lib "eagle-import") (part "R0603"))
    )
    (comp (ref "R157")
      (value "10k")
      (footprint "eagle-import:R0603")
      (libsource (lib "eagle-import") (part "R0603"))
    )
    (comp (ref "R158")
      (value "5.11k/1%")
      (footprint "eagle-import:R0603")
      (libsource (lib "eagle-import") (part "R0603"))
    )
    (comp (ref "R159")
      (value "5.11k/1%")
      (footprint "eagle-import:R0603")
      (libsource (lib "eagle-import") (part "R0603"))
    )
    (comp (ref "R160")
      (value "5.11k/1%")
      (footprint "eagle-import:R0603")
      (libsource (lib "eagle-import") (part "R0603"))
    )
    (comp (ref "R161")
      (value "5.11k/1%")
      (footprint "eagle-import:R0603")
      (libsource (lib "eagle-import") (part "R0603"))
    )
    (comp (ref "R162")
      (value "124k/1%")
      (footprint "eagle-import:R0603")
      (libsource (lib "eagle-import") (part "R0603"))
    )
    (comp (ref "R163")
      (value "124k/1%")
      (footprint "eagle-import:R0603")
      (libsource (lib "eagle-import") (part "R0603"))
    )
    (comp (ref "R164")
      (value "124k/1%")
      (footprint "eagle-import:R0603")
      (libsource (lib "eagle-import") (part "R0603"))
    )
    (comp (ref "R165")
      (value "124k/1%")
      (footprint "eagle-import:R0603")
      (libsource (lib "eagle-import") (part "R0603"))
    )
    (comp (ref "R166")
      (value "1k/1%")
      (footprint "eagle-import:R0603")
      (libsource (lib "eagle-import") (part "R0603"))
    )
    (comp (ref "R167")
      (value "1k/1%")
      (footprint "eagle-import:R0603")
      (libsource (lib "eagle-import") (part "R0603"))
    )
    (comp (ref "R168")
      (value "1k/1%")
      (footprint "eagle-import:R0603")
      (libsource (lib "eagle-import") (part "R0603"))
    )
    (comp (ref "R169")
      (value "1k/1%")
      (footprint "eagle-import:R0603")
      (libsource (lib "eagle-import") (part "R0603"))
    )
    (comp (ref "R170")
      (value "1k")
      (footprint "eagle-import:R0603")
      (libsource (lib "eagle-import") (part "R0603"))
    )
    (comp (ref "R171")
      (value "1k")
      (footprint "eagle-import:R0603")
      (libsource (lib "eagle-import") (part "R0603"))
    )
    (comp (ref "R172")
      (value "1k")
      (footprint "eagle-import:R0603")
      (libsource (lib "eagle-import") (part "R0603"))
    )
    (comp (ref "R173")
      (value "1k")
      (footprint "eagle-import:R0603")
      (libsource (lib "eagle-import") (part "R0603"))
    )
    (comp (ref "R174")
      (value "20K")
      (footprint "eagle-import:R0603")
      (libsource (lib "eagle-import") (part "R0603"))
    )
    (comp (ref "R175")
      (value "120R/0.1%")
      (footprint "eagle-import:R1206")
      (libsource (lib "eagle-import") (part "R1206"))
    )
    (comp (ref "R176")
      (value "120R/0.1%")
      (footprint "eagle-import:R1206")
      (libsource (lib "eagle-import") (part "R1206"))
    )
    (comp (ref "R177")
      (value "120R/0.1%")
      (footprint "eagle-import:R1206")
      (libsource (lib "eagle-import") (part "R1206"))
    )
    (comp (ref "R178")
      (value "120R/0.1%")
      (footprint "eagle-import:R1206")
      (libsource (lib "eagle-import") (part "R1206"))
    )
    (comp (ref "R179")
      (value "10k")
      (footprint "eagle-import:R0603")
      (libsource (lib "eagle-import") (part "R0603"))
    )
    (comp (ref "R180")
      (value "10k")
      (footprint "eagle-import:R0603")
      (libsource (lib "eagle-import") (part "R0603"))
    )
    (comp (ref "R181")
      (value "10k")
      (footprint "eagle-import:R0603")
      (libsource (lib "eagle-import") (part "R0603"))
    )
    (comp (ref "R182")
      (value "10k")
      (footprint "eagle-import:R0603")
      (libsource (lib "eagle-import") (part "R0603"))
    )
    (comp (ref "R183")
      (value "5.11k/1%")
      (footprint "eagle-import:R0603")
      (libsource (lib "eagle-import") (part "R0603"))
    )
    (comp (ref "R184")
      (value "5.11k/1%")
      (footprint "eagle-import:R0603")
      (libsource (lib "eagle-import") (part "R0603"))
    )
    (comp (ref "R185")
      (value "5.11k/1%")
      (footprint "eagle-import:R0603")
      (libsource (lib "eagle-import") (part "R0603"))
    )
    (comp (ref "R186")
      (value "5.11k/1%")
      (footprint "eagle-import:R0603")
      (libsource (lib "eagle-import") (part "R0603"))
    )
    (comp (ref "R187")
      (value "124k/1%")
      (footprint "eagle-import:R0603")
      (libsource (lib "eagle-import") (part "R0603"))
    )
    (comp (ref "R188")
      (value "124k/1%")
      (footprint "eagle-import:R0603")
      (libsource (lib "eagle-import") (part "R0603"))
    )
    (comp (ref "R189")
      (value "124k/1%")
      (footprint "eagle-import:R0603")
      (libsource (lib "eagle-import") (part "R0603"))
    )
    (comp (ref "R190")
      (value "124k/1%")
      (footprint "eagle-import:R0603")
      (libsource (lib "eagle-import") (part "R0603"))
    )
    (comp (ref "R191")
      (value "1k/1%")
      (footprint "eagle-import:R0603")
      (libsource (lib "eagle-import") (part "R0603"))
    )
    (comp (ref "R192")
      (value "1k/1%")
      (footprint "eagle-import:R0603")
      (libsource (lib "eagle-import") (part "R0603"))
    )
    (comp (ref "R193")
      (value "1k/1%")
      (footprint "eagle-import:R0603")
      (libsource (lib "eagle-import") (part "R0603"))
    )
    (comp (ref "R194")
      (value "1k/1%")
      (footprint "eagle-import:R0603")
      (libsource (lib "eagle-import") (part "R0603"))
    )
    (comp (ref "R195")
      (value "1k")
      (footprint "eagle-import:R0603")
      (libsource (lib "eagle-import") (part "R0603"))
    )
    (comp (ref "R196")
      (value "1k")
      (footprint "eagle-import:R0603")
      (libsource (lib "eagle-import") (part "R0603"))
    )
    (comp (ref "R197")
      (value "1k")
      (footprint "eagle-import:R0603")
      (libsource (lib "eagle-import") (part "R0603"))
    )
    (comp (ref "R198")
      (value "1k")
      (footprint "eagle-import:R0603")
      (libsource (lib "eagle-import") (part "R0603"))
    )
    (comp (ref "R199")
      (value "120R/0.1%")
      (footprint "eagle-import:R1206")
      (libsource (lib "eagle-import") (part "R1206"))
    )
    (comp (ref "R200")
      (value "120R/0.1%")
      (footprint "eagle-import:R1206")
      (libsource (lib "eagle-import") (part "R1206"))
    )
    (comp (ref "R201")
      (value "120R/0.1%")
      (footprint "eagle-import:R1206")
      (libsource (lib "eagle-import") (part "R1206"))
    )
    (comp (ref "R202")
      (value "120R/0.1%")
      (footprint "eagle-import:R1206")
      (libsource (lib "eagle-import") (part "R1206"))
    )
    (comp (ref "R203")
      (value "10k")
      (footprint "eagle-import:R0603")
      (libsource (lib "eagle-import") (part "R0603"))
    )
    (comp (ref "R204")
      (value "10k")
      (footprint "eagle-import:R0603")
      (libsource (lib "eagle-import") (part "R0603"))
    )
    (comp (ref "R205")
      (value "10k")
      (footprint "eagle-import:R0603")
      (libsource (lib "eagle-import") (part "R0603"))
    )
    (comp (ref "R206")
      (value "10k")
      (footprint "eagle-import:R0603")
      (libsource (lib "eagle-import") (part "R0603"))
    )
    (comp (ref "R207")
      (value "5.11k/1%")
      (footprint "eagle-import:R0603")
      (libsource (lib "eagle-import") (part "R0603"))
    )
    (comp (ref "R208")
      (value "5.11k/1%")
      (footprint "eagle-import:R0603")
      (libsource (lib "eagle-import") (part "R0603"))
    )
    (comp (ref "R209")
      (value "5.11k/1%")
      (footprint "eagle-import:R0603")
      (libsource (lib "eagle-import") (part "R0603"))
    )
    (comp (ref "R210")
      (value "5.11k/1%")
      (footprint "eagle-import:R0603")
      (libsource (lib "eagle-import") (part "R0603"))
    )
    (comp (ref "R211")
      (value "124k/1%")
      (footprint "eagle-import:R0603")
      (libsource (lib "eagle-import") (part "R0603"))
    )
    (comp (ref "R212")
      (value "124k/1%")
      (footprint "eagle-import:R0603")
      (libsource (lib "eagle-import") (part "R0603"))
    )
    (comp (ref "R213")
      (value "124k/1%")
      (footprint "eagle-import:R0603")
      (libsource (lib "eagle-import") (part "R0603"))
    )
    (comp (ref "R214")
      (value "124k/1%")
      (footprint "eagle-import:R0603")
      (libsource (lib "eagle-import") (part "R0603"))
    )
    (comp (ref "R215")
      (value "1k/1%")
      (footprint "eagle-import:R0603")
      (libsource (lib "eagle-import") (part "R0603"))
    )
    (comp (ref "R216")
      (value "1k/1%")
      (footprint "eagle-import:R0603")
      (libsource (lib "eagle-import") (part "R0603"))
    )
    (comp (ref "R217")
      (value "1k/1%")
      (footprint "eagle-import:R0603")
      (libsource (lib "eagle-import") (part "R0603"))
    )
    (comp (ref "R218")
      (value "1k/1%")
      (footprint "eagle-import:R0603")
      (libsource (lib "eagle-import") (part "R0603"))
    )
    (comp (ref "R219")
      (value "1k")
      (footprint "eagle-import:R0603")
      (libsource (lib "eagle-import") (part "R0603"))
    )
    (comp (ref "R220")
      (value "1k")
      (footprint "eagle-import:R0603")
      (libsource (lib "eagle-import") (part "R0603"))
    )
    (comp (ref "R221")
      (value "1k")
      (footprint "eagle-import:R0603")
      (libsource (lib "eagle-import") (part "R0603"))
    )
    (comp (ref "R222")
      (value "1k")
      (footprint "eagle-import:R0603")
      (libsource (lib "eagle-import") (part "R0603"))
    )
    (comp (ref "X42")
      (value "FFKDS/V1-5.08_MIDDLE")
      (footprint "eagle-import:FFKDS_V1-5,08-1_MIDDLE")
      (libsource (lib "eagle-import") (part "FFKDS/V1-5.08_MIDDLE"))
    )
    (comp (ref "X43")
      (value "FFKDS/V1-5.08_LAST")
      (footprint "eagle-import:FFKDS_V1-5,08-1_LAST")
      (libsource (lib "eagle-import") (part "FFKDS/V1-5.08_LAST"))
    )
    (comp (ref "X44")
      (value "FFKDS/V1-5.08_MIDDLE")
      (footprint "eagle-import:FFKDS_V1-5,08-1_MIDDLE")
      (libsource (lib "eagle-import") (part "FFKDS/V1-5.08_MIDDLE"))
    )
    (comp (ref "X45")
      (value "FFKDS/V1-5.08_MIDDLE")
      (footprint "eagle-import:FFKDS_V1-5,08-1_MIDDLE")
      (libsource (lib "eagle-import") (part "FFKDS/V1-5.08_MIDDLE"))
    )
    (comp (ref "X46")
      (value "FFKDS/V1-5.08_MIDDLE")
      (footprint "eagle-import:FFKDS_V1-5,08-1_MIDDLE")
      (libsource (lib "eagle-import") (part "FFKDS/V1-5.08_MIDDLE"))
    )
    (comp (ref "X47")
      (value "FFKDS/V1-5.08_MIDDLE")
      (footprint "eagle-import:FFKDS_V1-5,08-1_MIDDLE")
      (libsource (lib "eagle-import") (part "FFKDS/V1-5.08_MIDDLE"))
    )
    (comp (ref "X48")
      (value "FFKDS/V1-5.08_MIDDLE")
      (footprint "eagle-import:FFKDS_V1-5,08-1_MIDDLE")
      (libsource (lib "eagle-import") (part "FFKDS/V1-5.08_MIDDLE"))
    )
    (comp (ref "X49")
      (value "FFKDS/V1-5.08_MIDDLE")
      (footprint "eagle-import:FFKDS_V1-5,08-1_MIDDLE")
      (libsource (lib "eagle-import") (part "FFKDS/V1-5.08_MIDDLE"))
    )
    (comp (ref "X50")
      (value "FFKDS/V1-5.08_MIDDLE")
      (footprint "eagle-import:FFKDS_V1-5,08-1_MIDDLE")
      (libsource (lib "eagle-import") (part "FFKDS/V1-5.08_MIDDLE"))
    )
    (comp (ref "X51")
      (value "FFKDS/V1-5.08_MIDDLE")
      (footprint "eagle-import:FFKDS_V1-5,08-1_MIDDLE")
      (libsource (lib "eagle-import") (part "FFKDS/V1-5.08_MIDDLE"))
    )
    (comp (ref "X52")
      (value "FFKDS/V1-5.08_MIDDLE")
      (footprint "eagle-import:FFKDS_V1-5,08-1_MIDDLE")
      (libsource (lib "eagle-import") (part "FFKDS/V1-5.08_MIDDLE"))
    )
    (comp (ref "X53")
      (value "FFKDS/V1-5.08_MIDDLE")
      (footprint "eagle-import:FFKDS_V1-5,08-1_MIDDLE")
      (libsource (lib "eagle-import") (part "FFKDS/V1-5.08_MIDDLE"))
    )
    (comp (ref "X54")
      (value "FFKDS/V1-5.08_MIDDLE")
      (footprint "eagle-import:FFKDS_V1-5,08-1_MIDDLE")
      (libsource (lib "eagle-import") (part "FFKDS/V1-5.08_MIDDLE"))
    )
    (comp (ref "X55")
      (value "FFKDS/V1-5.08_MIDDLE")
      (footprint "eagle-import:FFKDS_V1-5,08-1_MIDDLE")
      (libsource (lib "eagle-import") (part "FFKDS/V1-5.08_MIDDLE"))
    )
    (comp (ref "X56")
      (value "FFKDS/V1-5.08_MIDDLE")
      (footprint "eagle-import:FFKDS_V1-5,08-1_MIDDLE")
      (libsource (lib "eagle-import") (part "FFKDS/V1-5.08_MIDDLE"))
    )
    (comp (ref "X57")
      (value "FFKDS/V1-5.08_MIDDLE")
      (footprint "eagle-import:FFKDS_V1-5,08-1_MIDDLE")
      (libsource (lib "eagle-import") (part "FFKDS/V1-5.08_MIDDLE"))
    )
    (comp (ref "X58")
      (value "FFKDS/V1-5.08_FIRST")
      (footprint "eagle-import:FFKDS_V1-5,08-1_FIRST")
      (libsource (lib "eagle-import") (part "FFKDS/V1-5.08_FIRST"))
    )
    (comp (ref "X59")
      (value "FFKDS/V1-5.08_MIDDLE")
      (footprint "eagle-import:FFKDS_V1-5,08-1_MIDDLE")
      (libsource (lib "eagle-import") (part "FFKDS/V1-5.08_MIDDLE"))
    )
    (comp (ref "X60")
      (value "FFKDS/V1-5.08_MIDDLE")
      (footprint "eagle-import:FFKDS_V1-5,08-1_MIDDLE")
      (libsource (lib "eagle-import") (part "FFKDS/V1-5.08_MIDDLE"))
    )
    (comp (ref "X61")
      (value "FFKDS/V1-5.08_MIDDLE")
      (footprint "eagle-import:FFKDS_V1-5,08-1_MIDDLE")
      (libsource (lib "eagle-import") (part "FFKDS/V1-5.08_MIDDLE"))
    )
    (comp (ref "X62")
      (value "FFKDS/V1-5.08_MIDDLE")
      (footprint "eagle-import:FFKDS_V1-5,08-1_MIDDLE")
      (libsource (lib "eagle-import") (part "FFKDS/V1-5.08_MIDDLE"))
    )
    (comp (ref "X63")
      (value "FFKDS/V1-5.08_MIDDLE")
      (footprint "eagle-import:FFKDS_V1-5,08-1_MIDDLE")
      (libsource (lib "eagle-import") (part "FFKDS/V1-5.08_MIDDLE"))
    )
    (comp (ref "X64")
      (value "FFKDS/V1-5.08_MIDDLE")
      (footprint "eagle-import:FFKDS_V1-5,08-1_MIDDLE")
      (libsource (lib "eagle-import") (part "FFKDS/V1-5.08_MIDDLE"))
    )
    (comp (ref "X65")
      (value "FFKDS/V1-5.08_MIDDLE")
      (footprint "eagle-import:FFKDS_V1-5,08-1_MIDDLE")
      (libsource (lib "eagle-import") (part "FFKDS/V1-5.08_MIDDLE"))
    )
    (comp (ref "X66")
      (value "FFKDS/V1-5.08_MIDDLE")
      (footprint "eagle-import:FFKDS_V1-5,08-1_MIDDLE")
      (libsource (lib "eagle-import") (part "FFKDS/V1-5.08_MIDDLE"))
    )
    (comp (ref "X67")
      (value "FFKDS/V1-5.08_MIDDLE")
      (footprint "eagle-import:FFKDS_V1-5,08-1_MIDDLE")
      (libsource (lib "eagle-import") (part "FFKDS/V1-5.08_MIDDLE"))
    )
    (comp (ref "X68")
      (value "FFKDS/V1-5.08_MIDDLE")
      (footprint "eagle-import:FFKDS_V1-5,08-1_MIDDLE")
      (libsource (lib "eagle-import") (part "FFKDS/V1-5.08_MIDDLE"))
    )
    (comp (ref "X69")
      (value "FFKDS/V1-5.08_LAST")
      (footprint "eagle-import:FFKDS_V1-5,08-1_LAST")
      (libsource (lib "eagle-import") (part "FFKDS/V1-5.08_LAST"))
    )
    (comp (ref "X70")
      (value "FFKDS/V1-5.08_FIRST")
      (footprint "eagle-import:FFKDS_V1-5,08-1_FIRST")
      (libsource (lib "eagle-import") (part "FFKDS/V1-5.08_FIRST"))
    )
    (comp (ref "X71")
      (value "FFKDS/V1-5.08_MIDDLE")
      (footprint "eagle-import:FFKDS_V1-5,08-1_MIDDLE")
      (libsource (lib "eagle-import") (part "FFKDS/V1-5.08_MIDDLE"))
    )
    (comp (ref "X72")
      (value "FFKDS/V1-5.08_MIDDLE")
      (footprint "eagle-import:FFKDS_V1-5,08-1_MIDDLE")
      (libsource (lib "eagle-import") (part "FFKDS/V1-5.08_MIDDLE"))
    )
    (comp (ref "X73")
      (value "FFKDS/V1-5.08_MIDDLE")
      (footprint "eagle-import:FFKDS_V1-5,08-1_MIDDLE")
      (libsource (lib "eagle-import") (part "FFKDS/V1-5.08_MIDDLE"))
    )
    (comp (ref "X74")
      (value "FFKDS/V1-5.08_MIDDLE")
      (footprint "eagle-import:FFKDS_V1-5,08-1_MIDDLE")
      (libsource (lib "eagle-import") (part "FFKDS/V1-5.08_MIDDLE"))
    )
    (comp (ref "X75")
      (value "FFKDS/V1-5.08_MIDDLE")
      (footprint "eagle-import:FFKDS_V1-5,08-1_MIDDLE")
      (libsource (lib "eagle-import") (part "FFKDS/V1-5.08_MIDDLE"))
    )
    (comp (ref "X76")
      (value "FFKDS/V1-5.08_MIDDLE")
      (footprint "eagle-import:FFKDS_V1-5,08-1_MIDDLE")
      (libsource (lib "eagle-import") (part "FFKDS/V1-5.08_MIDDLE"))
    )
    (comp (ref "X77")
      (value "FFKDS/V1-5.08_MIDDLE")
      (footprint "eagle-import:FFKDS_V1-5,08-1_MIDDLE")
      (libsource (lib "eagle-import") (part "FFKDS/V1-5.08_MIDDLE"))
    )
    (comp (ref "X78")
      (value "FFKDS/V1-5.08_MIDDLE")
      (footprint "eagle-import:FFKDS_V1-5,08-1_MIDDLE")
      (libsource (lib "eagle-import") (part "FFKDS/V1-5.08_MIDDLE"))
    )
    (comp (ref "X79")
      (value "FFKDS/V1-5.08_MIDDLE")
      (footprint "eagle-import:FFKDS_V1-5,08-1_MIDDLE")
      (libsource (lib "eagle-import") (part "FFKDS/V1-5.08_MIDDLE"))
    )
    (comp (ref "X80")
      (value "FFKDS/V1-5.08_MIDDLE")
      (footprint "eagle-import:FFKDS_V1-5,08-1_MIDDLE")
      (libsource (lib "eagle-import") (part "FFKDS/V1-5.08_MIDDLE"))
    )
    (comp (ref "X81")
      (value "FFKDS/V1-5.08_LAST")
      (footprint "eagle-import:FFKDS_V1-5,08-1_LAST")
      (libsource (lib "eagle-import") (part "FFKDS/V1-5.08_LAST"))
    )
    (comp (ref "X82")
      (value "FFKDS/V1-5.08_MIDDLE")
      (footprint "eagle-import:FFKDS_V1-5,08-1_MIDDLE")
      (libsource (lib "eagle-import") (part "FFKDS/V1-5.08_MIDDLE"))
    )
    (comp (ref "X83")
      (value "FFKDS/V1-5.08_MIDDLE")
      (footprint "eagle-import:FFKDS_V1-5,08-1_MIDDLE")
      (libsource (lib "eagle-import") (part "FFKDS/V1-5.08_MIDDLE"))
    )
    (comp (ref "X84")
      (value "FFKDS/V1-5.08_MIDDLE")
      (footprint "eagle-import:FFKDS_V1-5,08-1_MIDDLE")
      (libsource (lib "eagle-import") (part "FFKDS/V1-5.08_MIDDLE"))
    )
    (comp (ref "X85")
      (value "FFKDS/V1-5.08_MIDDLE")
      (footprint "eagle-import:FFKDS_V1-5,08-1_MIDDLE")
      (libsource (lib "eagle-import") (part "FFKDS/V1-5.08_MIDDLE"))
    )
    (comp (ref "X86")
      (value "FFKDS/V1-5.08_MIDDLE")
      (footprint "eagle-import:FFKDS_V1-5,08-1_MIDDLE")
      (libsource (lib "eagle-import") (part "FFKDS/V1-5.08_MIDDLE"))
    )
    (comp (ref "X87")
      (value "FFKDS/V1-5.08_MIDDLE")
      (footprint "eagle-import:FFKDS_V1-5,08-1_MIDDLE")
      (libsource (lib "eagle-import") (part "FFKDS/V1-5.08_MIDDLE"))
    )
    (comp (ref "X88")
      (value "FFKDS/V1-5.08_FIRST")
      (footprint "eagle-import:FFKDS_V1-5,08-1_FIRST")
      (libsource (lib "eagle-import") (part "FFKDS/V1-5.08_FIRST"))
    )
    (comp (ref "X89")
      (value "FFKDS/V1-5.08_MIDDLE")
      (footprint "eagle-import:FFKDS_V1-5,08-1_MIDDLE")
      (libsource (lib "eagle-import") (part "FFKDS/V1-5.08_MIDDLE"))
    )
    (comp (ref "XT2")
      (value "FFKDS/V1-5.08-2")
      (footprint "eagle-import:FFKDS_V1-5.08-2")
      (libsource (lib "eagle-import") (part "FFKDS/V1-5.08-2"))
    )
    (comp (ref "XT3")
      (value "FFKDS/V1-5.08-2")
      (footprint "eagle-import:FFKDS_V1-5.08-2")
      (libsource (lib "eagle-import") (part "FFKDS/V1-5.08-2"))
    )
    (comp (ref "C1")
      (value "1nF/2kV")
      (footprint "eagle-import:C1206")
      (libsource (lib "eagle-import") (part "C1206"))
    )
    (comp (ref "C2")
      (value "100nF/50V")
      (footprint "eagle-import:C0603")
      (libsource (lib "eagle-import") (part "C0603"))
    )
    (comp (ref "C3")
      (value "100nF/50V")
      (footprint "eagle-import:C0603")
      (libsource (lib "eagle-import") (part "C0603"))
    )
    (comp (ref "C4")
      (value "6.8nF/50V")
      (footprint "eagle-import:C0603")
      (libsource (lib "eagle-import") (part "C0603"))
    )
    (comp (ref "C5")
      (value "6.8nF/50V")
      (footprint "eagle-import:C0603")
      (libsource (lib "eagle-import") (part "C0603"))
    )
    (comp (ref "C6")
      (value "10nF/50V")
      (footprint "eagle-import:C0603")
      (libsource (lib "eagle-import") (part "C0603"))
    )
    (comp (ref "C7")
      (value "10uF/16V")
      (footprint "eagle-import:C0603")
      (libsource (lib "eagle-import") (part "C0603"))
    )
    (comp (ref "C8")
      (value "22nF/50V")
      (footprint "eagle-import:C0603")
      (libsource (lib "eagle-import") (part "C0603"))
    )
    (comp (ref "C9")
      (value "100nF/50V")
      (footprint "eagle-import:C0603")
      (libsource (lib "eagle-import") (part "C0603"))
    )
    (comp (ref "C10")
      (value "100nF/50V")
      (footprint "eagle-import:C0603")
      (libsource (lib "eagle-import") (part "C0603"))
    )
    (comp (ref "C11")
      (value "100nF/50V")
      (footprint "eagle-import:C0603")
      (libsource (lib "eagle-import") (part "C0603"))
    )
    (comp (ref "C12")
      (value "4.7uF/10V")
      (footprint "eagle-import:C0603")
      (libsource (lib "eagle-import") (part "C0603"))
    )
    (comp (ref "C13")
      (value "10nF/50V")
      (footprint "eagle-import:C0603")
      (libsource (lib "eagle-import") (part "C0603"))
    )
    (comp (ref "C14")
      (value "100nF/50V")
      (footprint "eagle-import:C0603")
      (libsource (lib "eagle-import") (part "C0603"))
    )
    (comp (ref "C15")
      (value "100nF/50V")
      (footprint "eagle-import:C0603")
      (libsource (lib "eagle-import") (part "C0603"))
    )
    (comp (ref "C16")
      (value "100nF/50V")
      (footprint "eagle-import:C0603")
      (libsource (lib "eagle-import") (part "C0603"))
    )
    (comp (ref "C17")
      (value "100nF/50V")
      (footprint "eagle-import:C0603")
      (libsource (lib "eagle-import") (part "C0603"))
    )
    (comp (ref "C18")
      (value "100nF/50V")
      (footprint "eagle-import:C0603")
      (libsource (lib "eagle-import") (part "C0603"))
    )
    (comp (ref "C19")
      (value "18pF/50V")
      (footprint "eagle-import:C0603")
      (libsource (lib "eagle-import") (part "C0603"))
    )
    (comp (ref "C20")
      (value "10uF/16V")
      (footprint "eagle-import:C0603")
      (libsource (lib "eagle-import") (part "C0603"))
    )
    (comp (ref "C21")
      (value "100nF/50V")
      (footprint "eagle-import:C0603")
      (libsource (lib "eagle-import") (part "C0603"))
    )
    (comp (ref "C22")
      (value "100nF/50V")
      (footprint "eagle-import:C0603")
      (libsource (lib "eagle-import") (part "C0603"))
    )
    (comp (ref "C23")
      (value "100nF/50V")
      (footprint "eagle-import:C0603")
      (libsource (lib "eagle-import") (part "C0603"))
    )
    (comp (ref "C24")
      (value "18pF/50V")
      (footprint "eagle-import:C0603")
      (libsource (lib "eagle-import") (part "C0603"))
    )
    (comp (ref "C25")
      (value "100nF/50V")
      (footprint "eagle-import:C0603")
      (libsource (lib "eagle-import") (part "C0603"))
    )
    (comp (ref "C26")
      (value "100nF/50V")
      (footprint "eagle-import:C0603")
      (libsource (lib "eagle-import") (part "C0603"))
    )
    (comp (ref "C27")
      (value "10uF/16V")
      (footprint "eagle-import:C0603")
      (libsource (lib "eagle-import") (part "C0603"))
    )
    (comp (ref "C28")
      (value "100nF/50V")
      (footprint "eagle-import:C0603")
      (libsource (lib "eagle-import") (part "C0603"))
    )
    (comp (ref "C29")
      (value "6.8pF/50V/NP0")
      (footprint "eagle-import:C0603")
      (libsource (lib "eagle-import") (part "C0603"))
    )
    (comp (ref "C30")
      (value "100nF/50V")
      (footprint "eagle-import:C0603")
      (libsource (lib "eagle-import") (part "C0603"))
    )
    (comp (ref "C31")
      (value "10uF/16V")
      (footprint "eagle-import:C0603")
      (libsource (lib "eagle-import") (part "C0603"))
    )
    (comp (ref "C32")
      (value "6.8pF/50V/NP0")
      (footprint "eagle-import:C0603")
      (libsource (lib "eagle-import") (part "C0603"))
    )
    (comp (ref "C33")
      (value "100nF/50V")
      (footprint "eagle-import:C0603")
      (libsource (lib "eagle-import") (part "C0603"))
    )
    (comp (ref "C34")
      (value "18pF/50V/NP0")
      (footprint "eagle-import:C0603")
      (libsource (lib "eagle-import") (part "C0603"))
    )
    (comp (ref "C35")
      (value "18pF/50V/NP0")
      (footprint "eagle-import:C0603")
      (libsource (lib "eagle-import") (part "C0603"))
    )
    (comp (ref "C36")
      (value "100nF/50V")
      (footprint "eagle-import:C0603")
      (libsource (lib "eagle-import") (part "C0603"))
    )
    (comp (ref "C37")
      (value "100nF/50V")
      (footprint "eagle-import:C0603")
      (libsource (lib "eagle-import") (part "C0603"))
    )
    (comp (ref "C38")
      (value "100nF/50V")
      (footprint "eagle-import:C0603")
      (libsource (lib "eagle-import") (part "C0603"))
    )
    (comp (ref "C39")
      (value "100nF/50V")
      (footprint "eagle-import:C0603")
      (libsource (lib "eagle-import") (part "C0603"))
    )
    (comp (ref "C40")
      (value "100nF/50V")
      (footprint "eagle-import:C0603")
      (libsource (lib "eagle-import") (part "C0603"))
    )
    (comp (ref "C41")
      (value "100nF/50V")
      (footprint "eagle-import:C0603")
      (libsource (lib "eagle-import") (part "C0603"))
    )
    (comp (ref "C42")
      (value "100nF/50V")
      (footprint "eagle-import:C0603")
      (libsource (lib "eagle-import") (part "C0603"))
    )
    (comp (ref "C43")
      (value "100nF/50V")
      (footprint "eagle-import:C0603")
      (libsource (lib "eagle-import") (part "C0603"))
    )
    (comp (ref "C44")
      (value "100nF/50V")
      (footprint "eagle-import:C0603")
      (libsource (lib "eagle-import") (part "C0603"))
    )
    (comp (ref "C45")
      (value "100nF/50V")
      (footprint "eagle-import:C0603")
      (libsource (lib "eagle-import") (part "C0603"))
    )
    (comp (ref "CON1")
      (value "HR951180A")
      (footprint "eagle-import:HY951180A")
      (libsource (lib "eagle-import") (part "HR951180A"))
    )
    (comp (ref "CON2")
      (value "FFKDS/V1-5.08-3")
      (footprint "eagle-import:FFKDS_V1-5.08-3")
      (libsource (lib "eagle-import") (part "FFKDS/V1-5.08-3"))
    )
    (comp (ref "CON3")
      (value "SWJ")
      (footprint "eagle-import:PINHEAD-4P")
      (libsource (lib "eagle-import") (part "SWJ"))
    )
    (comp (ref "D1")
      (value "SM712-02H")
      (footprint "eagle-import:SOT23-3")
      (libsource (lib "eagle-import") (part "SM712-02H"))
    )
    (comp (ref "G1")
      (value "CR2032H")
      (footprint "eagle-import:CR2032H")
      (libsource (lib "eagle-import") (part "CR2032H"))
    )
    (comp (ref "IC1")
      (value "ST3232BD")
      (footprint "eagle-import:SO16")
      (libsource (lib "eagle-import") (part "ST3232BD"))
    )
    (comp (ref "IC2")
      (value "ST3485EBD")
      (footprint "eagle-import:SO08")
      (libsource (lib "eagle-import") (part "ST3485EBD"))
    )
    (comp (ref "IC3")
      (value "W5500")
      (footprint "eagle-import:LQFP48_7X7_0.5P")
      (libsource (lib "eagle-import") (part "W5500"))
    )
    (comp (ref "IC4")
      (value "SD2068")
      (footprint "eagle-import:SOIC-8")
      (libsource (lib "eagle-import") (part "SD2068"))
    )
    (comp (ref "IC5")
      (value "STM32F103VCT6")
      (footprint "eagle-import:LQFP100_14X14MM")
      (libsource (lib "eagle-import") (part "STM32F103VCT6"))
    )
    (comp (ref "L1")
      (value "600R/100MHz")
      (footprint "eagle-import:L0603")
      (libsource (lib "eagle-import") (part "INDUCTOR/FERRITE-BEAD'0603'"))
    )
    (comp (ref "L2")
      (value "600R/100MHz")
      (footprint "eagle-import:L0603")
      (libsource (lib "eagle-import") (part "INDUCTOR/FERRITE-BEAD'0603'"))
    )
    (comp (ref "L3")
      (value "120R/100MHz 3A")
      (footprint "eagle-import:L0603")
      (libsource (lib "eagle-import") (part "INDUCTOR/FERRITE-BEAD'0603'"))
    )
    (comp (ref "L4")
      (value "120R/100MHz 3A")
      (footprint "eagle-import:L0603")
      (libsource (lib "eagle-import") (part "INDUCTOR/FERRITE-BEAD'0603'"))
    )
    (comp (ref "L5")
      (value "600R/100MHz")
      (footprint "eagle-import:L0603")
      (libsource (lib "eagle-import") (part "INDUCTOR/FERRITE-BEAD'0603'"))
    )
    (comp (ref "L6")
      (value "600R/100MHz")
      (footprint "eagle-import:L0603")
      (libsource (lib "eagle-import") (part "INDUCTOR/FERRITE-BEAD'0603'"))
    )
    (comp (ref "L7")
      (value "600R/100MHz")
      (footprint "eagle-import:L0603")
      (libsource (lib "eagle-import") (part "INDUCTOR/FERRITE-BEAD'0603'"))
    )
    (comp (ref "LED1")
      (value "LEDSML0805")
      (footprint "eagle-import:SML0805")
      (libsource (lib "eagle-import") (part "LEDSML0805"))
    )
    (comp (ref "LED2")
      (value "LEDSML0805")
      (footprint "eagle-import:SML0805")
      (libsource (lib "eagle-import") (part "LEDSML0805"))
    )
    (comp (ref "LED3")
      (value "LED0805")
      (footprint "eagle-import:LED0805")
      (libsource (lib "eagle-import") (part "LED0805"))
    )
    (comp (ref "LOGO1")
      (value "SY-LOGO_BOTTOM")
      (footprint "eagle-import:SY-LOGO_BOTTOM")
      (libsource (lib "eagle-import") (part "SY-LOGO_BOTTOM"))
    )
    (comp (ref "R1")
      (value "0R")
      (footprint "eagle-import:R1206")
      (libsource (lib "eagle-import") (part "R1206"))
    )
    (comp (ref "R2")
      (value "22R")
      (footprint "eagle-import:R0603")
      (libsource (lib "eagle-import") (part "R0603"))
    )
    (comp (ref "R3")
      (value "330R")
      (footprint "eagle-import:R0603")
      (libsource (lib "eagle-import") (part "R0603"))
    )
    (comp (ref "R4")
      (value "330R")
      (footprint "eagle-import:R0603")
      (libsource (lib "eagle-import") (part "R0603"))
    )
    (comp (ref "R5")
      (value "22R")
      (footprint "eagle-import:R0603")
      (libsource (lib "eagle-import") (part "R0603"))
    )
    (comp (ref "R6")
      (value "10k")
      (footprint "eagle-import:R0603")
      (libsource (lib "eagle-import") (part "R0603"))
    )
    (comp (ref "R7")
      (value "49R9")
      (footprint "eagle-import:R0603")
      (libsource (lib "eagle-import") (part "R0603"))
    )
    (comp (ref "R8")
      (value "49R9")
      (footprint "eagle-import:R0603")
      (libsource (lib "eagle-import") (part "R0603"))
    )
    (comp (ref "R9")
      (value "49R9")
      (footprint "eagle-import:R0603")
      (libsource (lib "eagle-import") (part "R0603"))
    )
    (comp (ref "R10")
      (value "10R")
      (footprint "eagle-import:R0603")
      (libsource (lib "eagle-import") (part "R0603"))
    )
    (comp (ref "R11")
      (value "49R9")
      (footprint "eagle-import:R0603")
      (libsource (lib "eagle-import") (part "R0603"))
    )
    (comp (ref "R12")
      (value "10k")
      (footprint "eagle-import:R0603")
      (libsource (lib "eagle-import") (part "R0603"))
    )
    (comp (ref "R13")
      (value "120R")
      (footprint "eagle-import:R1206")
      (libsource (lib "eagle-import") (part "R1206"))
    )
    (comp (ref "R14")
      (value "2.4k")
      (footprint "eagle-import:R1206")
      (libsource (lib "eagle-import") (part "R1206"))
    )
    (comp (ref "R15")
      (value "2.4k")
      (footprint "eagle-import:R1206")
      (libsource (lib "eagle-import") (part "R1206"))
    )
    (comp (ref "R16")
      (value "12.4k/1%")
      (footprint "eagle-import:R0603")
      (libsource (lib "eagle-import") (part "R0603"))
    )
    (comp (ref "R17")
      (value "10k")
      (footprint "eagle-import:R0603")
      (libsource (lib "eagle-import") (part "R0603"))
    )
    (comp (ref "R18")
      (value "0R")
      (footprint "eagle-import:R0603")
      (libsource (lib "eagle-import") (part "R0603"))
    )
    (comp (ref "R19")
      (value "0R")
      (footprint "eagle-import:R0603")
      (libsource (lib "eagle-import") (part "R0603"))
    )
    (comp (ref "R20")
      (value "0R")
      (footprint "eagle-import:R0603")
      (libsource (lib "eagle-import") (part "R0603"))
    )
    (comp (ref "R21")
      (value "1M")
      (footprint "eagle-import:R0603")
      (libsource (lib "eagle-import") (part "R0603"))
    )
    (comp (ref "R22")
      (value "0R")
      (footprint "eagle-import:R0603")
      (libsource (lib "eagle-import") (part "R0603"))
    )
    (comp (ref "R23")
      (value "10k")
      (footprint "eagle-import:R0603")
      (libsource (lib "eagle-import") (part "R0603"))
    )
    (comp (ref "R24")
      (value "330R")
      (footprint "eagle-import:R0603")
      (libsource (lib "eagle-import") (part "R0603"))
    )
    (comp (ref "R25")
      (value "330R")
      (footprint "eagle-import:R0603")
      (libsource (lib "eagle-import") (part "R0603"))
    )
    (comp (ref "R26")
      (value "10k")
      (footprint "eagle-import:R0603")
      (libsource (lib "eagle-import") (part "R0603"))
    )
    (comp (ref "R27")
      (value "10k")
      (footprint "eagle-import:R0603")
      (libsource (lib "eagle-import") (part "R0603"))
    )
    (comp (ref "R28")
      (value "10k")
      (footprint "eagle-import:R0603")
      (libsource (lib "eagle-import") (part "R0603"))
    )
    (comp (ref "R29")
      (value "10k")
      (footprint "eagle-import:R0603")
      (libsource (lib "eagle-import") (part "R0603"))
    )
    (comp (ref "R30")
      (value "10k")
      (footprint "eagle-import:R0603")
      (libsource (lib "eagle-import") (part "R0603"))
    )
    (comp (ref "R31")
      (value "10k")
      (footprint "eagle-import:R0603")
      (libsource (lib "eagle-import") (part "R0603"))
    )
    (comp (ref "R32")
      (value "10k")
      (footprint "eagle-import:R0603")
      (libsource (lib "eagle-import") (part "R0603"))
    )
    (comp (ref "R33")
      (value "10k")
      (footprint "eagle-import:R0603")
      (libsource (lib "eagle-import") (part "R0603"))
    )
    (comp (ref "R34")
      (value "1k")
      (footprint "eagle-import:R0603")
      (libsource (lib "eagle-import") (part "R0603"))
    )
    (comp (ref "R35")
      (value "10k")
      (footprint "eagle-import:R0603")
      (libsource (lib "eagle-import") (part "R0603"))
    )
    (comp (ref "R36")
      (value "10k")
      (footprint "eagle-import:R0603")
      (libsource (lib "eagle-import") (part "R0603"))
    )
    (comp (ref "R37")
      (value "10k")
      (footprint "eagle-import:R0603")
      (libsource (lib "eagle-import") (part "R0603"))
    )
    (comp (ref "R38")
      (value "10k")
      (footprint "eagle-import:R0603")
      (libsource (lib "eagle-import") (part "R0603"))
    )
    (comp (ref "R39")
      (value "10k")
      (footprint "eagle-import:R0603")
      (libsource (lib "eagle-import") (part "R0603"))
    )
    (comp (ref "U1")
      (value "LQ-BTM2540")
      (footprint "eagle-import:LQ-BTM2540")
      (libsource (lib "eagle-import") (part "LQ-BTM2540"))
    )
    (comp (ref "X1")
      (value "F09VP")
      (footprint "eagle-import:F09VP")
      (libsource (lib "eagle-import") (part "F09VP"))
    )
    (comp (ref "XT1")
      (value "FFKDS/V1-5.08-2")
      (footprint "eagle-import:FFKDS_V1-5.08-2")
      (libsource (lib "eagle-import") (part "FFKDS/V1-5.08-2"))
    )
    (comp (ref "XTAL1")
      (value "25MHz")
      (footprint "eagle-import:SM49")
      (libsource (lib "eagle-import") (part "CRYSTALSM49"))
    )
    (comp (ref "XTAL2")
      (value "MC-306 32.768000kHz 12.5 +20.0-20.0")
      (footprint "eagle-import:MC306")
      (libsource (lib "eagle-import") (part "MC-306"))
    )
    (comp (ref "XTAL3")
      (value "8MHz")
      (footprint "eagle-import:SM49")
      (libsource (lib "eagle-import") (part "CRYSTALSM49"))
    )
  )
  (nets
    (net (code "1") (name "+3V3") (class "Default")
      (node (ref "C15") (pin "1") (pinfunction "1_1") (pintype "passive"))
      (node (ref "C16") (pin "1") (pinfunction "1_1") (pintype "passive"))
      (node (ref "CON1") (pin "12") (pinfunction "12_12") (pintype "passive"))
      (node (ref "CON1") (pin "9") (pinfunction "9_9") (pintype "passive"))
      (node (ref "CON3") (pin "1") (pinfunction "VDD_1") (pintype "passive"))
      (node (ref "IC3") (pin "28") (pinfunction "VDD_28") (pintype "power_in"))
      (node (ref "IC5") (pin "100") (pinfunction "VDD_100") (pintype "power_in"))
      (node (ref "IC5") (pin "11") (pinfunction "VDD_11") (pintype "power_in"))
      (node (ref "IC5") (pin "28") (pinfunction "VDD_28") (pintype "power_in"))
      (node (ref "IC5") (pin "50") (pinfunction "VDD_50") (pintype "power_in"))
      (node (ref "IC5") (pin "6") (pinfunction "VBAT_6") (pintype "bidirectional"))
      (node (ref "IC5") (pin "75") (pinfunction "VDD_75") (pintype "power_in"))
      (node (ref "L1") (pin "2") (pinfunction "2_2") (pintype "passive"))
      (node (ref "L2") (pin "2") (pinfunction "2_2") (pintype "passive"))
      (node (ref "L3") (pin "1") (pinfunction "1_1") (pintype "passive"))
      (node (ref "L5") (pin "1") (pinfunction "1_1") (pintype "passive"))
      (node (ref "L6") (pin "1") (pinfunction "1_1") (pintype "passive"))
      (node (ref "L7") (pin "1") (pinfunction "1_1") (pintype "passive"))
      (node (ref "R108") (pin "2") (pinfunction "2_2") (pintype "passive"))
      (node (ref "R109") (pin "2") (pinfunction "2_2") (pintype "passive"))
      (node (ref "R110") (pin "2") (pinfunction "2_2") (pintype "passive"))
      (node (ref "R111") (pin "2") (pinfunction "2_2") (pintype "passive"))
      (node (ref "R120") (pin "2") (pinfunction "2_2") (pintype "passive"))
      (node (ref "R121") (pin "2") (pinfunction "2_2") (pintype "passive"))
      (node (ref "R122") (pin "2") (pinfunction "2_2") (pintype "passive"))
      (node (ref "R123") (pin "2") (pinfunction "2_2") (pintype "passive"))
      (node (ref "R132") (pin "2") (pinfunction "2_2") (pintype "passive"))
      (node (ref "R133") (pin "2") (pinfunction "2_2") (pintype "passive"))
      (node (ref "R134") (pin "2") (pinfunction "2_2") (pintype "passive"))
      (node (ref "R135") (pin "2") (pinfunction "2_2") (pintype "passive"))
      (node (ref "R144") (pin "2") (pinfunction "2_2") (pintype "passive"))
      (node (ref "R145") (pin "2") (pinfunction "2_2") (pintype "passive"))
      (node (ref "R146") (pin "2") (pinfunction "2_2") (pintype "passive"))
      (node (ref "R147") (pin "2") (pinfunction "2_2") (pintype "passive"))
      (node (ref "R23") (pin "2") (pinfunction "2_2") (pintype "passive"))
      (node (ref "R26") (pin "2") (pinfunction "2_2") (pintype "passive"))
      (node (ref "R28") (pin "2") (pinfunction "2_2") (pintype "passive"))
      (node (ref "R30") (pin "2") (pinfunction "2_2") (pintype "passive"))
      (node (ref "R38") (pin "2") (pinfunction "2_2") (pintype "passive"))
      (node (ref "R96") (pin "2") (pinfunction "2_2") (pintype "passive"))
      (node (ref "R97") (pin "2") (pinfunction "2_2") (pintype "passive"))
      (node (ref "R98") (pin "2") (pinfunction "2_2") (pintype "passive"))
      (node (ref "R99") (pin "2") (pinfunction "2_2") (pintype "passive"))
    )
    (net (code "2") (name "+5V") (class "Default")
      (node (ref "C45") (pin "1") (pinfunction "1_1") (pintype "passive"))
    )
    (net (code "4") (name "+24V") (class "Default")
      (node (ref "C122") (pin "+") (pinfunction "+_+") (pintype "passive"))
      (node (ref "C123") (pin "1") (pinfunction "1_1") (pintype "passive"))
      (node (ref "C54") (pin "1") (pinfunction "1_1") (pintype "passive"))
      (node (ref "C55") (pin "1") (pinfunction "1_1") (pintype "passive"))
      (node (ref "C56") (pin "1") (pinfunction "1_1") (pintype "passive"))
      (node (ref "C65") (pin "1") (pinfunction "1_1") (pintype "passive"))
      (node (ref "C66") (pin "1") (pinfunction "1_1") (pintype "passive"))
      (node (ref "C67") (pin "1") (pinfunction "1_1") (pintype "passive"))
      (node (ref "C76") (pin "1") (pinfunction "1_1") (pintype "passive"))
      (node (ref "C77") (pin "1") (pinfunction "1_1") (pintype "passive"))
      (node (ref "C78") (pin "1") (pinfunction "1_1") (pintype "passive"))
      (node (ref "CON4") (pin "B1") (pinfunction "B1_B1") (pintype "passive"))
      (node (ref "D27") (pin "A") (pinfunction "A_A") (pintype "passive"))
      (node (ref "EC1") (pin "+") (pinfunction "+_+") (pintype "passive"))
      (node (ref "EC2") (pin "+") (pinfunction "+_+") (pintype "passive"))
      (node (ref "EC3") (pin "+") (pinfunction "+_+") (pintype "passive"))
      (node (ref "IC14") (pin "OUT") (pinfunction "OUT_OUT") (pintype "passive"))
      (node (ref "IC6") (pin "10") (pinfunction "CD+_10") (pintype "passive"))
      (node (ref "IC7") (pin "10") (pinfunction "CD+_10") (pintype "passive"))
      (node (ref "IC8") (pin "10") (pinfunction "CD+_10") (pintype "passive"))
      (node (ref "R48") (pin "1") (pinfunction "1_1") (pintype "passive"))
      (node (ref "R49") (pin "1") (pinfunction "1_1") (pintype "passive"))
      (node (ref "R50") (pin "1") (pinfunction "1_1") (pintype "passive"))
      (node (ref "R51") (pin "1") (pinfunction "1_1") (pintype "passive"))
      (node (ref "R52") (pin "1") (pinfunction "1_1") (pintype "passive"))
      (node (ref "R53") (pin "1") (pinfunction "1_1") (pintype "passive"))
      (node (ref "R54") (pin "1") (pinfunction "1_1") (pintype "passive"))
      (node (ref "R55") (pin "1") (pinfunction "1_1") (pintype "passive"))
      (node (ref "R64") (pin "1") (pinfunction "1_1") (pintype "passive"))
      (node (ref "R65") (pin "1") (pinfunction "1_1") (pintype "passive"))
      (node (ref "R66") (pin "1") (pinfunction "1_1") (pintype "passive"))
      (node (ref "R67") (pin "1") (pinfunction "1_1") (pintype "passive"))
      (node (ref "R68") (pin "1") (pinfunction "1_1") (pintype "passive"))
      (node (ref "R69") (pin "1") (pinfunction "1_1") (pintype "passive"))
      (node (ref "R70") (pin "1") (pinfunction "1_1") (pintype "passive"))
      (node (ref "R71") (pin "1") (pinfunction "1_1") (pintype "passive"))
      (node (ref "R80") (pin "1") (pinfunction "1_1") (pintype "passive"))
      (node (ref "R81") (pin "1") (pinfunction "1_1") (pintype "passive"))
      (node (ref "R82") (pin "1") (pinfunction "1_1") (pintype "passive"))
      (node (ref "R83") (pin "1") (pinfunction "1_1") (pintype "passive"))
      (node (ref "R84") (pin "1") (pinfunction "1_1") (pintype "passive"))
      (node (ref "R85") (pin "1") (pinfunction "1_1") (pintype "passive"))
      (node (ref "R86") (pin "1") (pinfunction "1_1") (pintype "passive"))
      (node (ref "R87") (pin "1") (pinfunction "1_1") (pintype "passive"))
      (node (ref "X58") (pin "1@1") (pinfunction "1_1@1") (pintype "passive"))
      (node (ref "X58") (pin "2@1") (pinfunction "1_2@1") (pintype "passive"))
      (node (ref "X59") (pin "1@1") (pinfunction "1_1@1") (pintype "passive"))
      (node (ref "X59") (pin "2@1") (pinfunction "1_2@1") (pintype "passive"))
      (node (ref "X60") (pin "1@1") (pinfunction "1_1@1") (pintype "passive"))
      (node (ref "X60") (pin "2@1") (pinfunction "1_2@1") (pintype "passive"))
      (node (ref "X61") (pin "1@1") (pinfunction "1_1@1") (pintype "passive"))
      (node (ref "X61") (pin "2@1") (pinfunction "1_2@1") (pintype "passive"))
      (node (ref "X62") (pin "1@1") (pinfunction "1_1@1") (pintype "passive"))
      (node (ref "X62") (pin "2@1") (pinfunction "1_2@1") (pintype "passive"))
      (node (ref "X63") (pin "1@1") (pinfunction "1_1@1") (pintype "passive"))
      (node (ref "X63") (pin "2@1") (pinfunction "1_2@1") (pintype "passive"))
      (node (ref "X64") (pin "1@1") (pinfunction "1_1@1") (pintype "passive"))
      (node (ref "X64") (pin "2@1") (pinfunction "1_2@1") (pintype "passive"))
      (node (ref "X65") (pin "1@1") (pinfunction "1_1@1") (pintype "passive"))
      (node (ref "X65") (pin "2@1") (pinfunction "1_2@1") (pintype "passive"))
      (node (ref "X66") (pin "1@1") (pinfunction "1_1@1") (pintype "passive"))
      (node (ref "X66") (pin "2@1") (pinfunction "1_2@1") (pintype "passive"))
      (node (ref "X67") (pin "1@1") (pinfunction "1_1@1") (pintype "passive"))
      (node (ref "X67") (pin "2@1") (pinfunction "1_2@1") (pintype "passive"))
      (node (ref "X68") (pin "1@1") (pinfunction "1_1@1") (pintype "passive"))
      (node (ref "X68") (pin "2@1") (pinfunction "1_2@1") (pintype "passive"))
      (node (ref "X69") (pin "1@1") (pinfunction "1_1@1") (pintype "passive"))
      (node (ref "X69") (pin "2@1") (pinfunction "1_2@1") (pintype "passive"))
    )
    (net (code "11") (name "1V20") (class "Default")
      (node (ref "C13") (pin "1") (pinfunction "1_1") (pintype "passive"))
      (node (ref "IC3") (pin "22") (pinfunction "1V2O_22") (pintype "bidirectional"))
    )
    (net (code "12") (name "ACTLED") (class "Default")
      (node (ref "IC3") (pin "27") (pinfunction "ACTLED_27") (pintype "output"))
      (node (ref "R25") (pin "2") (pinfunction "2_2") (pintype "passive"))
    )
    (net (code "13") (name "ADCIN0") (class "Default")
      (node (ref "C115") (pin "1") (pinfunction "1_1") (pintype "passive"))
      (node (ref "IC5") (pin "23") (pinfunction "PA0-WKUP_23") (pintype "bidirectional"))
      (node (ref "R170") (pin "2") (pinfunction "2_2") (pintype "passive"))
    )
    (net (code "14") (name "ADCIN1") (class "Default")
      (node (ref "C116") (pin "1") (pinfunction "1_1") (pintype "passive"))
      (node (ref "IC5") (pin "24") (pinfunction "PA1_24") (pintype "bidirectional"))
      (node (ref "R171") (pin "2") (pinfunction "2_2") (pintype "passive"))
    )
    (net (code "15") (name "ADCIN2") (class "Default")
      (node (ref "C117") (pin "1") (pinfunction "1_1") (pintype "passive"))
      (node (ref "IC5") (pin "25") (pinfunction "PA2_25") (pintype "bidirectional"))
      (node (ref "R172") (pin "2") (pinfunction "2_2") (pintype "passive"))
    )
    (net (code "16") (name "ADCIN3") (class "Default")
      (node (ref "C118") (pin "1") (pinfunction "1_1") (pintype "passive"))
      (node (ref "IC5") (pin "26") (pinfunction "PA3_26") (pintype "bidirectional"))
      (node (ref "R173") (pin "2") (pinfunction "2_2") (pintype "passive"))
    )
    (net (code "17") (name "ADCIN4") (class "Default")
      (node (ref "C132") (pin "1") (pinfunction "1_1") (pintype "passive"))
      (node (ref "IC5") (pin "29") (pinfunction "PA4_29") (pintype "bidirectional"))
      (node (ref "R195") (pin "2") (pinfunction "2_2") (pintype "passive"))
    )
    (net (code "18") (name "ADCIN5") (class "Default")
      (node (ref "C133") (pin "1") (pinfunction "1_1") (pintype "passive"))
      (node (ref "IC5") (pin "30") (pinfunction "PA5_30") (pintype "bidirectional"))
      (node (ref "R196") (pin "2") (pinfunction "2_2") (pintype "passive"))
    )
    (net (code "19") (name "ADCIN6") (class "Default")
      (node (ref "C134") (pin "1") (pinfunction "1_1") (pintype "passive"))
      (node (ref "IC5") (pin "31") (pinfunction "PA6_31") (pintype "bidirectional"))
      (node (ref "R197") (pin "2") (pinfunction "2_2") (pintype "passive"))
    )
    (net (code "20") (name "ADCIN7") (class "Default")
      (node (ref "C135") (pin "1") (pinfunction "1_1") (pintype "passive"))
      (node (ref "IC5") (pin "32") (pinfunction "PA7_32") (pintype "bidirectional"))
      (node (ref "R198") (pin "2") (pinfunction "2_2") (pintype "passive"))
    )
    (net (code "21") (name "ADCIN8") (class "Default")
      (node (ref "C148") (pin "1") (pinfunction "1_1") (pintype "passive"))
      (node (ref "IC5") (pin "35") (pinfunction "PB0_35") (pintype "bidirectional"))
      (node (ref "R219") (pin "2") (pinfunction "2_2") (pintype "passive"))
    )
    (net (code "22") (name "ADCIN9") (class "Default")
      (node (ref "C149") (pin "1") (pinfunction "1_1") (pintype "passive"))
      (node (ref "IC5") (pin "36") (pinfunction "PB1_36") (pintype "bidirectional"))
      (node (ref "R220") (pin "2") (pinfunction "2_2") (pintype "passive"))
    )
    (net (code "23") (name "ADCIN10") (class "Default")
      (node (ref "C150") (pin "1") (pinfunction "1_1") (pintype "passive"))
      (node (ref "IC5") (pin "15") (pinfunction "PC0_15") (pintype "bidirectional"))
      (node (ref "R221") (pin "2") (pinfunction "2_2") (pintype "passive"))
    )
    (net (code "24") (name "ADCIN11") (class "Default")
      (node (ref "C151") (pin "1") (pinfunction "1_1") (pintype "passive"))
      (node (ref "IC5") (pin "16") (pinfunction "PC1_16") (pintype "bidirectional"))
      (node (ref "R222") (pin "2") (pinfunction "2_2") (pintype "passive"))
    )
    (net (code "25") (name "AGND") (class "Default")
      (node (ref "C100") (pin "2") (pinfunction "2_2") (pintype "passive"))
      (node (ref "C101") (pin "2") (pinfunction "2_2") (pintype "passive"))
      (node (ref "C102") (pin "-") (pinfunction "-_-") (pintype "passive"))
      (node (ref "C103") (pin "2") (pinfunction "2_2") (pintype "passive"))
      (node (ref "C104") (pin "-") (pinfunction "-_-") (pintype "passive"))
      (node (ref "C105") (pin "2") (pinfunction "2_2") (pintype "passive"))
      (node (ref "C106") (pin "2") (pinfunction "2_2") (pintype "passive"))
      (node (ref "C107") (pin "2") (pinfunction "2_2") (pintype "passive"))
      (node (ref "C108") (pin "2") (pinfunction "2_2") (pintype "passive"))
      (node (ref "C109") (pin "2") (pinfunction "2_2") (pintype "passive"))
      (node (ref "C114") (pin "2") (pinfunction "2_2") (pintype "passive"))
      (node (ref "C115") (pin "2") (pinfunction "2_2") (pintype "passive"))
      (node (ref "C116") (pin "2") (pinfunction "2_2") (pintype "passive"))
      (node (ref "C117") (pin "2") (pinfunction "2_2") (pintype "passive"))
      (node (ref "C118") (pin "2") (pinfunction "2_2") (pintype "passive"))
      (node (ref "C119") (pin "2") (pinfunction "2_2") (pintype "passive"))
      (node (ref "C120") (pin "-") (pinfunction "-_-") (pintype "passive"))
      (node (ref "C121") (pin "2") (pinfunction "2_2") (pintype "passive"))
      (node (ref "C122") (pin "-") (pinfunction "-_-") (pintype "passive"))
      (node (ref "C123") (pin "2") (pinfunction "2_2") (pintype "passive"))
      (node (ref "C124") (pin "2") (pinfunction "2_2") (pintype "passive"))
      (node (ref "C125") (pin "2") (pinfunction "2_2") (pintype "passive"))
      (node (ref "C126") (pin "2") (pinfunction "2_2") (pintype "passive"))
      (node (ref "C127") (pin "2") (pinfunction "2_2") (pintype "passive"))
      (node (ref "C132") (pin "2") (pinfunction "2_2") (pintype "passive"))
      (node (ref "C133") (pin "2") (pinfunction "2_2") (pintype "passive"))
      (node (ref "C134") (pin "2") (pinfunction "2_2") (pintype "passive"))
      (node (ref "C135") (pin "2") (pinfunction "2_2") (pintype "passive"))
      (node (ref "C136") (pin "2") (pinfunction "2_2") (pintype "passive"))
      (node (ref "C137") (pin "2") (pinfunction "2_2") (pintype "passive"))
      (node (ref "C138") (pin "2") (pinfunction "2_2") (pintype "passive"))
      (node (ref "C139") (pin "2") (pinfunction "2_2") (pintype "passive"))
      (node (ref "C140") (pin "2") (pinfunction "2_2") (pintype "passive"))
      (node (ref "C141") (pin "2") (pinfunction "2_2") (pintype "passive"))
      (node (ref "C146") (pin "2") (pinfunction "2_2") (pintype "passive"))
      (node (ref "C147") (pin "2") (pinfunction "2_2") (pintype "passive"))
      (node (ref "C148") (pin "2") (pinfunction "2_2") (pintype "passive"))
      (node (ref "C149") (pin "2") (pinfunction "2_2") (pintype "passive"))
      (node (ref "C150") (pin "2") (pinfunction "2_2") (pintype "passive"))
      (node (ref "C151") (pin "2") (pinfunction "2_2") (pintype "passive"))
      (node (ref "C99") (pin "2") (pinfunction "2_2") (pintype "passive"))
      (node (ref "DB1") (pin "DC-") (pinfunction "-_DC-") (pintype "passive"))
      (node (ref "DB2") (pin "DC-") (pinfunction "-_DC-") (pintype "passive"))
      (node (ref "IC10") (pin "3") (pinfunction "VSS_3") (pintype "bidirectional"))
      (node (ref "IC12") (pin "11") (pinfunction "V-_11") (pintype "power_in"))
      (node (ref "IC13") (pin "11") (pinfunction "V-_11") (pintype "power_in"))
      (node (ref "IC14") (pin "GND") (pinfunction "GND_GND") (pintype "input"))
      (node (ref "IC15") (pin "11") (pinfunction "V-_11") (pintype "power_in"))
      (node (ref "IC16") (pin "11") (pinfunction "V-_11") (pintype "power_in"))
      (node (ref "IC5") (pin "19") (pinfunction "VSSA_19") (pintype "power_in"))
      (node (ref "IC5") (pin "20") (pinfunction "VREF-_20") (pintype "power_in"))
      (node (ref "IC9") (pin "2") (pinfunction "A_2") (pintype "passive"))
      (node (ref "L9") (pin "2") (pinfunction "2_2") (pintype "passive"))
      (node (ref "R149") (pin "2") (pinfunction "2_2") (pintype "passive"))
      (node (ref "R150") (pin "1") (pinfunction "1_1") (pintype "passive"))
      (node (ref "R151") (pin "1") (pinfunction "1_1") (pintype "passive"))
      (node (ref "R152") (pin "1") (pinfunction "1_1") (pintype "passive"))
      (node (ref "R153") (pin "1") (pinfunction "1_1") (pintype "passive"))
      (node (ref "R162") (pin "1") (pinfunction "1_1") (pintype "passive"))
      (node (ref "R163") (pin "1") (pinfunction "1_1") (pintype "passive"))
      (node (ref "R164") (pin "1") (pinfunction "1_1") (pintype "passive"))
      (node (ref "R165") (pin "1") (pinfunction "1_1") (pintype "passive"))
      (node (ref "R174") (pin "2") (pinfunction "2_2") (pintype "passive"))
      (node (ref "R175") (pin "1") (pinfunction "1_1") (pintype "passive"))
      (node (ref "R176") (pin "1") (pinfunction "1_1") (pintype "passive"))
      (node (ref "R177") (pin "1") (pinfunction "1_1") (pintype "passive"))
      (node (ref "R178") (pin "1") (pinfunction "1_1") (pintype "passive"))
      (node (ref "R187") (pin "1") (pinfunction "1_1") (pintype "passive"))
      (node (ref "R188") (pin "1") (pinfunction "1_1") (pintype "passive"))
      (node (ref "R189") (pin "1") (pinfunction "1_1") (pintype "passive"))
      (node (ref "R190") (pin "1") (pinfunction "1_1") (pintype "passive"))
      (node (ref "R199") (pin "1") (pinfunction "1_1") (pintype "passive"))
      (node (ref "R200") (pin "1") (pinfunction "1_1") (pintype "passive"))
      (node (ref "R201") (pin "1") (pinfunction "1_1") (pintype "passive"))
      (node (ref "R202") (pin "1") (pinfunction "1_1") (pintype "passive"))
      (node (ref "R211") (pin "1") (pinfunction "1_1") (pintype "passive"))
      (node (ref "R212") (pin "1") (pinfunction "1_1") (pintype "passive"))
      (node (ref "R213") (pin "1") (pinfunction "1_1") (pintype "passive"))
      (node (ref "R214") (pin "1") (pinfunction "1_1") (pintype "passive"))
      (node (ref "X43") (pin "1@1") (pinfunction "1_1@1") (pintype "passive"))
      (node (ref "X43") (pin "2@1") (pinfunction "1_2@1") (pintype "passive"))
      (node (ref "X45") (pin "1@1") (pinfunction "1_1@1") (pintype "passive"))
      (node (ref "X45") (pin "2@1") (pinfunction "1_2@1") (pintype "passive"))
      (node (ref "X47") (pin "1@1") (pinfunction "1_1@1") (pintype "passive"))
      (node (ref "X47") (pin "2@1") (pinfunction "1_2@1") (pintype "passive"))
      (node (ref "X49") (pin "1@1") (pinfunction "1_1@1") (pintype "passive"))
      (node (ref "X49") (pin "2@1") (pinfunction "1_2@1") (pintype "passive"))
      (node (ref "X51") (pin "1@1") (pinfunction "1_1@1") (pintype "passive"))
      (node (ref "X51") (pin "2@1") (pinfunction "1_2@1") (pintype "passive"))
      (node (ref "X53") (pin "1@1") (pinfunction "1_1@1") (pintype "passive"))
      (node (ref "X53") (pin "2@1") (pinfunction "1_2@1") (pintype "passive"))
      (node (ref "X55") (pin "1@1") (pinfunction "1_1@1") (pintype "passive"))
      (node (ref "X55") (pin "2@1") (pinfunction "1_2@1") (pintype "passive"))
      (node (ref "X57") (pin "1@1") (pinfunction "1_1@1") (pintype "passive"))
      (node (ref "X57") (pin "2@1") (pinfunction "1_2@1") (pintype "passive"))
      (node (ref "X70") (pin "1@1") (pinfunction "1_1@1") (pintype "passive"))
      (node (ref "X70") (pin "2@1") (pinfunction "1_2@1") (pintype "passive"))
      (node (ref "X71") (pin "1@1") (pinfunction "1_1@1") (pintype "passive"))
      (node (ref "X71") (pin "2@1") (pinfunction "1_2@1") (pintype "passive"))
      (node (ref "X72") (pin "1@1") (pinfunction "1_1@1") (pintype "passive"))
      (node (ref "X72") (pin "2@1") (pinfunction "1_2@1") (pintype "passive"))
      (node (ref "X73") (pin "1@1") (pinfunction "1_1@1") (pintype "passive"))
      (node (ref "X73") (pin "2@1") (pinfunction "1_2@1") (pintype "passive"))
      (node (ref "X74") (pin "1@1") (pinfunction "1_1@1") (pintype "passive"))
      (node (ref "X74") (pin "2@1") (pinfunction "1_2@1") (pintype "passive"))
      (node (ref "X75") (pin "1@1") (pinfunction "1_1@1") (pintype "passive"))
      (node (ref "X75") (pin "2@1") (pinfunction "1_2@1") (pintype "passive"))
      (node (ref "X76") (pin "1@1") (pinfunction "1_1@1") (pintype "passive"))
      (node (ref "X76") (pin "2@1") (pinfunction "1_2@1") (pintype "passive"))
      (node (ref "X77") (pin "1@1") (pinfunction "1_1@1") (pintype "passive"))
      (node (ref "X77") (pin "2@1") (pinfunction "1_2@1") (pintype "passive"))
      (node (ref "X78") (pin "1@1") (pinfunction "1_1@1") (pintype "passive"))
      (node (ref "X78") (pin "2@1") (pinfunction "1_2@1") (pintype "passive"))
      (node (ref "X79") (pin "1@1") (pinfunction "1_1@1") (pintype "passive"))
      (node (ref "X79") (pin "2@1") (pinfunction "1_2@1") (pintype "passive"))
      (node (ref "X80") (pin "1@1") (pinfunction "1_1@1") (pintype "passive"))
      (node (ref "X80") (pin "2@1") (pinfunction "1_2@1") (pintype "passive"))
      (node (ref "X81") (pin "1@1") (pinfunction "1_1@1") (pintype "passive"))
      (node (ref "X81") (pin "2@1") (pinfunction "1_2@1") (pintype "passive"))
      (node (ref "X83") (pin "1@1") (pinfunction "1_1@1") (pintype "passive"))
      (node (ref "X83") (pin "2@1") (pinfunction "1_2@1") (pintype "passive"))
      (node (ref "X85") (pin "1@1") (pinfunction "1_1@1") (pintype "passive"))
      (node (ref "X85") (pin "2@1") (pinfunction "1_2@1") (pintype "passive"))
      (node (ref "X87") (pin "1@1") (pinfunction "1_1@1") (pintype "passive"))
      (node (ref "X87") (pin "2@1") (pinfunction "1_2@1") (pintype "passive"))
      (node (ref "X89") (pin "1@1") (pinfunction "1_1@1") (pintype "passive"))
      (node (ref "X89") (pin "2@1") (pinfunction "1_2@1") (pintype "passive"))
    )
    (net (code "26") (name "BOOT0") (class "Default")
      (node (ref "IC5") (pin "94") (pinfunction "BOOT0_94") (pintype "bidirectional"))
      (node (ref "R39") (pin "2") (pinfunction "2_2") (pintype "passive"))
    )
    (net (code "27") (name "BTM-LINK") (class "Default")
      (node (ref "IC5") (pin "88") (pinfunction "PD7_88") (pintype "bidirectional"))
      (node (ref "U1") (pin "15") (pinfunction "P1.1_15") (pintype "bidirectional"))
    )
    (net (code "28") (name "BTM-RX") (class "Default")
      (node (ref "IC5") (pin "86") (pinfunction "PD5_86") (pintype "bidirectional"))
      (node (ref "U1") (pin "22") (pinfunction "P0.2/RX_22") (pintype "bidirectional"))
    )
    (net (code "29") (name "BTM-TX") (class "Default")
      (node (ref "IC5") (pin "87") (pinfunction "PD6_87") (pintype "bidirectional"))
      (node (ref "U1") (pin "21") (pinfunction "P0.3/TX_21") (pintype "bidirectional"))
    )
    (net (code "30") (name "BTM-WORK_STATUS") (class "Default")
      (node (ref "R34") (pin "1") (pinfunction "1_1") (pintype "passive"))
      (node (ref "U1") (pin "16") (pinfunction "P1.0_16") (pintype "bidirectional"))
    )
    (net (code "31") (name "BTM-~{ATC}") (class "Default")
      (node (ref "IC5") (pin "89") (pinfunction "PB3_89") (pintype "bidirectional"))
      (node (ref "U1") (pin "6") (pinfunction "P2.0_6") (pintype "bidirectional"))
    )
    (net (code "32") (name "DIN1") (class "Default")
      (node (ref "C79") (pin "1") (pinfunction "1_1") (pintype "passive"))
      (node (ref "IC5") (pin "97") (pinfunction "PE0_97") (pintype "bidirectional"))
      (node (ref "OK7") (pin "16") (pinfunction "COL_16") (pintype "passive"))
      (node (ref "R96") (pin "1") (pinfunction "1_1") (pintype "passive"))
    )
    (net (code "33") (name "DIN2") (class "Default")
      (node (ref "C80") (pin "1") (pinfunction "1_1") (pintype "passive"))
      (node (ref "IC5") (pin "98") (pinfunction "PE1_98") (pintype "bidirectional"))
      (node (ref "OK7") (pin "14") (pinfunction "COL_14") (pintype "passive"))
      (node (ref "R97") (pin "1") (pinfunction "1_1") (pintype "passive"))
    )
    (net (code "34") (name "DIN3") (class "Default")
      (node (ref "C81") (pin "1") (pinfunction "1_1") (pintype "passive"))
      (node (ref "IC5") (pin "1") (pinfunction "PE2_1") (pintype "bidirectional"))
      (node (ref "OK7") (pin "12") (pinfunction "COL_12") (pintype "passive"))
      (node (ref "R98") (pin "1") (pinfunction "1_1") (pintype "passive"))
    )
    (net (code "35") (name "DIN4") (class "Default")
      (node (ref "C82") (pin "1") (pinfunction "1_1") (pintype "passive"))
      (node (ref "IC5") (pin "2") (pinfunction "PE3_2") (pintype "bidirectional"))
      (node (ref "OK7") (pin "10") (pinfunction "COL_10") (pintype "passive"))
      (node (ref "R99") (pin "1") (pinfunction "1_1") (pintype "passive"))
    )
    (net (code "36") (name "DIN5") (class "Default")
      (node (ref "C83") (pin "1") (pinfunction "1_1") (pintype "passive"))
      (node (ref "IC5") (pin "3") (pinfunction "PE4_3") (pintype "bidirectional"))
      (node (ref "OK8") (pin "16") (pinfunction "COL_16") (pintype "passive"))
      (node (ref "R108") (pin "1") (pinfunction "1_1") (pintype "passive"))
    )
    (net (code "37") (name "DIN6") (class "Default")
      (node (ref "C84") (pin "1") (pinfunction "1_1") (pintype "passive"))
      (node (ref "IC5") (pin "4") (pinfunction "PE5_4") (pintype "bidirectional"))
      (node (ref "OK8") (pin "14") (pinfunction "COL_14") (pintype "passive"))
      (node (ref "R109") (pin "1") (pinfunction "1_1") (pintype "passive"))
    )
    (net (code "38") (name "DIN7") (class "Default")
      (node (ref "C85") (pin "1") (pinfunction "1_1") (pintype "passive"))
      (node (ref "IC5") (pin "5") (pinfunction "PE6_5") (pintype "bidirectional"))
      (node (ref "OK8") (pin "12") (pinfunction "COL_12") (pintype "passive"))
      (node (ref "R110") (pin "1") (pinfunction "1_1") (pintype "passive"))
    )
    (net (code "39") (name "DIN8") (class "Default")
      (node (ref "C86") (pin "1") (pinfunction "1_1") (pintype "passive"))
      (node (ref "IC5") (pin "38") (pinfunction "PE7_38") (pintype "bidirectional"))
      (node (ref "OK8") (pin "10") (pinfunction "COL_10") (pintype "passive"))
      (node (ref "R111") (pin "1") (pinfunction "1_1") (pintype "passive"))
    )
    (net (code "40") (name "DIN9") (class "Default")
      (node (ref "C87") (pin "1") (pinfunction "1_1") (pintype "passive"))
      (node (ref "IC5") (pin "39") (pinfunction "PE8_39") (pintype "bidirectional"))
      (node (ref "OK9") (pin "16") (pinfunction "COL_16") (pintype "passive"))
      (node (ref "R120") (pin "1") (pinfunction "1_1") (pintype "passive"))
    )
    (net (code "41") (name "DIN10") (class "Default")
      (node (ref "C88") (pin "1") (pinfunction "1_1") (pintype "passive"))
      (node (ref "IC5") (pin "40") (pinfunction "PE9_40") (pintype "bidirectional"))
      (node (ref "OK9") (pin "14") (pinfunction "COL_14") (pintype "passive"))
      (node (ref "R121") (pin "1") (pinfunction "1_1") (pintype "passive"))
    )
    (net (code "42") (name "DIN11") (class "Default")
      (node (ref "C89") (pin "1") (pinfunction "1_1") (pintype "passive"))
      (node (ref "IC5") (pin "41") (pinfunction "PE10_41") (pintype "bidirectional"))
      (node (ref "OK9") (pin "12") (pinfunction "COL_12") (pintype "passive"))
      (node (ref "R122") (pin "1") (pinfunction "1_1") (pintype "passive"))
    )
    (net (code "43") (name "DIN12") (class "Default")
      (node (ref "C90") (pin "1") (pinfunction "1_1") (pintype "passive"))
      (node (ref "IC5") (pin "42") (pinfunction "PE11_42") (pintype "bidirectional"))
      (node (ref "OK9") (pin "10") (pinfunction "COL_10") (pintype "passive"))
      (node (ref "R123") (pin "1") (pinfunction "1_1") (pintype "passive"))
    )
    (net (code "44") (name "DIN13") (class "Default")
      (node (ref "C91") (pin "1") (pinfunction "1_1") (pintype "passive"))
      (node (ref "IC5") (pin "43") (pinfunction "PE12_43") (pintype "bidirectional"))
      (node (ref "OK10") (pin "16") (pinfunction "COL_16") (pintype "passive"))
      (node (ref "R132") (pin "1") (pinfunction "1_1") (pintype "passive"))
    )
    (net (code "45") (name "DIN14") (class "Default")
      (node (ref "C92") (pin "1") (pinfunction "1_1") (pintype "passive"))
      (node (ref "IC5") (pin "44") (pinfunction "PE13_44") (pintype "bidirectional"))
      (node (ref "OK10") (pin "14") (pinfunction "COL_14") (pintype "passive"))
      (node (ref "R133") (pin "1") (pinfunction "1_1") (pintype "passive"))
    )
    (net (code "46") (name "DIN15") (class "Default")
      (node (ref "C93") (pin "1") (pinfunction "1_1") (pintype "passive"))
      (node (ref "IC5") (pin "45") (pinfunction "PE14_45") (pintype "bidirectional"))
      (node (ref "OK10") (pin "12") (pinfunction "COL_12") (pintype "passive"))
      (node (ref "R134") (pin "1") (pinfunction "1_1") (pintype "passive"))
    )
    (net (code "47") (name "DIN16") (class "Default")
      (node (ref "C94") (pin "1") (pinfunction "1_1") (pintype "passive"))
      (node (ref "IC5") (pin "46") (pinfunction "PE15_46") (pintype "bidirectional"))
      (node (ref "OK10") (pin "10") (pinfunction "COL_10") (pintype "passive"))
      (node (ref "R135") (pin "1") (pinfunction "1_1") (pintype "passive"))
    )
    (net (code "48") (name "DIN17") (class "Default")
      (node (ref "C95") (pin "1") (pinfunction "1_1") (pintype "passive"))
      (node (ref "IC5") (pin "17") (pinfunction "PC2_17") (pintype "bidirectional"))
      (node (ref "OK11") (pin "16") (pinfunction "COL_16") (pintype "passive"))
      (node (ref "R144") (pin "1") (pinfunction "1_1") (pintype "passive"))
    )
    (net (code "49") (name "DIN18") (class "Default")
      (node (ref "C96") (pin "1") (pinfunction "1_1") (pintype "passive"))
      (node (ref "IC5") (pin "18") (pinfunction "PC3_18") (pintype "bidirectional"))
      (node (ref "OK11") (pin "14") (pinfunction "COL_14") (pintype "passive"))
      (node (ref "R145") (pin "1") (pinfunction "1_1") (pintype "passive"))
    )
    (net (code "50") (name "DIN19") (class "Default")
      (node (ref "C97") (pin "1") (pinfunction "1_1") (pintype "passive"))
      (node (ref "IC5") (pin "33") (pinfunction "PC4_33") (pintype "bidirectional"))
      (node (ref "OK11") (pin "12") (pinfunction "COL_12") (pintype "passive"))
      (node (ref "R146") (pin "1") (pinfunction "1_1") (pintype "passive"))
    )
    (net (code "51") (name "DIN20") (class "Default")
      (node (ref "C98") (pin "1") (pinfunction "1_1") (pintype "passive"))
      (node (ref "IC5") (pin "34") (pinfunction "PC5_34") (pintype "bidirectional"))
      (node (ref "OK11") (pin "10") (pinfunction "COL_10") (pintype "passive"))
      (node (ref "R147") (pin "1") (pinfunction "1_1") (pintype "passive"))
    )
    (net (code "52") (name "DOUT1") (class "Default")
      (node (ref "IC5") (pin "81") (pinfunction "PD0_81") (pintype "bidirectional"))
      (node (ref "R40") (pin "2") (pinfunction "2_2") (pintype "passive"))
    )
    (net (code "53") (name "DOUT2") (class "Default")
      (node (ref "IC5") (pin "82") (pinfunction "PD1_82") (pintype "bidirectional"))
      (node (ref "R41") (pin "2") (pinfunction "2_2") (pintype "passive"))
    )
    (net (code "54") (name "DOUT3") (class "Default")
      (node (ref "IC5") (pin "83") (pinfunction "PD2_83") (pintype "bidirectional"))
      (node (ref "R42") (pin "2") (pinfunction "2_2") (pintype "passive"))
    )
    (net (code "55") (name "DOUT4") (class "Default")
      (node (ref "IC5") (pin "84") (pinfunction "PD3_84") (pintype "bidirectional"))
      (node (ref "R43") (pin "2") (pinfunction "2_2") (pintype "passive"))
    )
    (net (code "56") (name "DOUT5") (class "Default")
      (node (ref "IC5") (pin "85") (pinfunction "PD4_85") (pintype "bidirectional"))
      (node (ref "R44") (pin "2") (pinfunction "2_2") (pintype "passive"))
    )
    (net (code "57") (name "DOUT6") (class "Default")
      (node (ref "IC5") (pin "58") (pinfunction "PD11_58") (pintype "bidirectional"))
      (node (ref "R45") (pin "2") (pinfunction "2_2") (pintype "passive"))
    )
    (net (code "58") (name "DOUT7") (class "Default")
      (node (ref "IC5") (pin "59") (pinfunction "PD12_59") (pintype "bidirectional"))
      (node (ref "R46") (pin "2") (pinfunction "2_2") (pintype "passive"))
    )
    (net (code "59") (name "DOUT8") (class "Default")
      (node (ref "IC5") (pin "60") (pinfunction "PD13_60") (pintype "bidirectional"))
      (node (ref "R47") (pin "2") (pinfunction "2_2") (pintype "passive"))
    )
    (net (code "60") (name "DOUT9") (class "Default")
      (node (ref "IC5") (pin "61") (pinfunction "PD14_61") (pintype "bidirectional"))
      (node (ref "R56") (pin "2") (pinfunction "2_2") (pintype "passive"))
    )
    (net (code "61") (name "DOUT10") (class "Default")
      (node (ref "IC5") (pin "62") (pinfunction "PD15_62") (pintype "bidirectional"))
      (node (ref "R57") (pin "2") (pinfunction "2_2") (pintype "passive"))
    )
    (net (code "62") (name "DOUT11") (class "Default")
      (node (ref "IC5") (pin "63") (pinfunction "PC6_63") (pintype "bidirectional"))
      (node (ref "R58") (pin "2") (pinfunction "2_2") (pintype "passive"))
    )
    (net (code "63") (name "DOUT12") (class "Default")
      (node (ref "IC5") (pin "64") (pinfunction "PC7_64") (pintype "bidirectional"))
      (node (ref "R59") (pin "2") (pinfunction "2_2") (pintype "passive"))
    )
    (net (code "64") (name "DOUT13") (class "Default")
      (node (ref "IC5") (pin "65") (pinfunction "PC8_65") (pintype "bidirectional"))
      (node (ref "R60") (pin "2") (pinfunction "2_2") (pintype "passive"))
    )
    (net (code "65") (name "DOUT14") (class "Default")
      (node (ref "IC5") (pin "66") (pinfunction "PC9_66") (pintype "bidirectional"))
      (node (ref "R61") (pin "2") (pinfunction "2_2") (pintype "passive"))
    )
    (net (code "66") (name "DOUT15") (class "Default")
      (node (ref "IC5") (pin "78") (pinfunction "PC10_78") (pintype "bidirectional"))
      (node (ref "R62") (pin "2") (pinfunction "2_2") (pintype "passive"))
    )
    (net (code "67") (name "DOUT16") (class "Default")
      (node (ref "IC5") (pin "79") (pinfunction "PC11_79") (pintype "bidirectional"))
      (node (ref "R63") (pin "2") (pinfunction "2_2") (pintype "passive"))
    )
    (net (code "68") (name "DOUT17") (class "Default")
      (node (ref "IC5") (pin "80") (pinfunction "PC12_80") (pintype "bidirectional"))
      (node (ref "R72") (pin "2") (pinfunction "2_2") (pintype "passive"))
    )
    (net (code "69") (name "DOUT18") (class "Default")
      (node (ref "IC5") (pin "90") (pinfunction "PB4_90") (pintype "bidirectional"))
      (node (ref "R73") (pin "2") (pinfunction "2_2") (pintype "passive"))
    )
    (net (code "70") (name "DOUT19") (class "Default")
      (node (ref "IC5") (pin "95") (pinfunction "PB8_95") (pintype "bidirectional"))
      (node (ref "R74") (pin "2") (pinfunction "2_2") (pintype "passive"))
    )
    (net (code "71") (name "DOUT20") (class "Default")
      (node (ref "IC5") (pin "96") (pinfunction "PB9_96") (pintype "bidirectional"))
      (node (ref "R75") (pin "2") (pinfunction "2_2") (pintype "passive"))
    )
    (net (code "72") (name "DOUT21") (class "Default")
      (node (ref "IC5") (pin "67") (pinfunction "PA8_67") (pintype "bidirectional"))
      (node (ref "R76") (pin "2") (pinfunction "2_2") (pintype "passive"))
    )
    (net (code "73") (name "DOUT22") (class "Default")
      (node (ref "IC5") (pin "70") (pinfunction "PA11_70") (pintype "bidirectional"))
      (node (ref "R77") (pin "2") (pinfunction "2_2") (pintype "passive"))
    )
    (net (code "74") (name "DOUT23") (class "Default")
      (node (ref "IC5") (pin "71") (pinfunction "PA12_71") (pintype "bidirectional"))
      (node (ref "R78") (pin "2") (pinfunction "2_2") (pintype "passive"))
    )
    (net (code "75") (name "DOUT24") (class "Default")
      (node (ref "IC5") (pin "77") (pinfunction "PA15_77") (pintype "bidirectional"))
      (node (ref "R79") (pin "2") (pinfunction "2_2") (pintype "passive"))
    )
    (net (code "76") (name "DUPLED") (class "Default")
      (node (ref "IC3") (pin "26") (pinfunction "DUPLED_26") (pintype "output"))
      (node (ref "R24") (pin "2") (pinfunction "2_2") (pintype "passive"))
    )
    (net (code "77") (name "ETHSPI_MISO") (class "Default")
      (node (ref "IC3") (pin "34") (pinfunction "MISO_34") (pintype "output"))
      (node (ref "IC5") (pin "53") (pinfunction "PB14_53") (pintype "bidirectional"))
    )
    (net (code "78") (name "ETHSPI_MOSI") (class "Default")
      (node (ref "IC3") (pin "35") (pinfunction "MOSI_35") (pintype "input"))
      (node (ref "IC5") (pin "54") (pinfunction "PB15_54") (pintype "bidirectional"))
    )
    (net (code "79") (name "ETHSPI_NSS") (class "Default")
      (node (ref "IC3") (pin "32") (pinfunction "~{SCS}_32") (pintype "input"))
      (node (ref "IC5") (pin "51") (pinfunction "PB12_51") (pintype "bidirectional"))
    )
    (net (code "80") (name "ETHSPI_SCK") (class "Default")
      (node (ref "IC3") (pin "33") (pinfunction "SCLK_33") (pintype "input"))
      (node (ref "IC5") (pin "52") (pinfunction "PB13_52") (pintype "bidirectional"))
    )
    (net (code "81") (name "ETH_RX_N") (class "Default")
      (node (ref "C4") (pin "2") (pinfunction "2_2") (pintype "passive"))
      (node (ref "IC3") (pin "5") (pinfunction "RXN_5") (pintype "input"))
      (node (ref "R9") (pin "1") (pinfunction "1_1") (pintype "passive"))
    )
    (net (code "82") (name "ETH_RX_P") (class "Default")
      (node (ref "C5") (pin "2") (pinfunction "2_2") (pintype "passive"))
      (node (ref "IC3") (pin "6") (pinfunction "RXP_6") (pintype "input"))
      (node (ref "R11") (pin "1") (pinfunction "1_1") (pintype "passive"))
    )
    (net (code "83") (name "ETH_TX_N") (class "Default")
      (node (ref "CON1") (pin "2") (pinfunction "P2_2") (pintype "passive"))
      (node (ref "IC3") (pin "1") (pinfunction "TXN_1") (pintype "output"))
      (node (ref "R8") (pin "2") (pinfunction "2_2") (pintype "passive"))
    )
    (net (code "84") (name "ETH_TX_P") (class "Default")
      (node (ref "CON1") (pin "1") (pinfunction "P1_1") (pintype "passive"))
      (node (ref "IC3") (pin "2") (pinfunction "TXP_2") (pintype "output"))
      (node (ref "R7") (pin "2") (pinfunction "2_2") (pintype "passive"))
    )
    (net (code "85") (name "ETH_XI") (class "Default")
      (node (ref "C19") (pin "1") (pinfunction "1_1") (pintype "passive"))
      (node (ref "IC3") (pin "30") (pinfunction "XI/CLKIN_30") (pintype "input"))
      (node (ref "R21") (pin "1") (pinfunction "1_1") (pintype "passive"))
      (node (ref "XTAL1") (pin "1") (pinfunction "1_1") (pintype "passive"))
    )
    (net (code "86") (name "ETH_XO") (class "Default")
      (node (ref "IC3") (pin "31") (pinfunction "XO_31") (pintype "output"))
      (node (ref "R21") (pin "2") (pinfunction "2_2") (pintype "passive"))
      (node (ref "R22") (pin "2") (pinfunction "2_2") (pintype "passive"))
    )
    (net (code "87") (name "ETH_~{INT}") (class "Default")
      (node (ref "IC3") (pin "36") (pinfunction "~{INT}_36") (pintype "output"))
      (node (ref "IC5") (pin "47") (pinfunction "PB10_47") (pintype "bidirectional"))
    )
    (net (code "88") (name "ETH_~{RST}") (class "Default")
      (node (ref "IC3") (pin "37") (pinfunction "RST_N_37") (pintype "bidirectional"))
      (node (ref "IC5") (pin "48") (pinfunction "PB11_48") (pintype "bidirectional"))
    )
    (net (code "89") (name "EXRES1") (class "Default")
      (node (ref "IC3") (pin "10") (pinfunction "EXRES1_10") (pintype "bidirectional"))
      (node (ref "R16") (pin "1") (pinfunction "1_1") (pintype "passive"))
    )
    (net (code "90") (name "GND") (class "Default")
      (node (ref "C14") (pin "2") (pinfunction "2_2") (pintype "passive"))
      (node (ref "C15") (pin "2") (pinfunction "2_2") (pintype "passive"))
      (node (ref "C16") (pin "2") (pinfunction "2_2") (pintype "passive"))
      (node (ref "C2") (pin "2") (pinfunction "2_2") (pintype "passive"))
      (node (ref "C20") (pin "2") (pinfunction "2_2") (pintype "passive"))
      (node (ref "C22") (pin "2") (pinfunction "2_2") (pintype "passive"))
      (node (ref "C28") (pin "2") (pinfunction "2_2") (pintype "passive"))
      (node (ref "C29") (pin "2") (pinfunction "2_2") (pintype "passive"))
      (node (ref "C3") (pin "2") (pinfunction "2_2") (pintype "passive"))
      (node (ref "C30") (pin "2") (pinfunction "2_2") (pintype "passive"))
      (node (ref "C31") (pin "2") (pinfunction "2_2") (pintype "passive"))
      (node (ref "C32") (pin "2") (pinfunction "2_2") (pintype "passive"))
      (node (ref "C33") (pin "2") (pinfunction "2_2") (pintype "passive"))
      (node (ref "C34") (pin "2") (pinfunction "2_2") (pintype "passive"))
      (node (ref "C35") (pin "2") (pinfunction "2_2") (pintype "passive"))
      (node (ref "C36") (pin "2") (pinfunction "2_2") (pintype "passive"))
      (node (ref "C37") (pin "2") (pinfunction "2_2") (pintype "passive"))
      (node (ref "C38") (pin "2") (pinfunction "2_2") (pintype "passive"))
      (node (ref "C39") (pin "2") (pinfunction "2_2") (pintype "passive"))
      (node (ref "C40") (pin "2") (pinfunction "2_2") (pintype "passive"))
      (node (ref "C41") (pin "2") (pinfunction "2_2") (pintype "passive"))
      (node (ref "C42") (pin "2") (pinfunction "2_2") (pintype "passive"))
      (node (ref "C43") (pin "2") (pinfunction "2_2") (pintype "passive"))
      (node (ref "C44") (pin "2") (pinfunction "2_2") (pintype "passive"))
      (node (ref "C7") (pin "2") (pinfunction "2_2") (pintype "passive"))
      (node (ref "C79") (pin "2") (pinfunction "2_2") (pintype "passive"))
      (node (ref "C80") (pin "2") (pinfunction "2_2") (pintype "passive"))
      (node (ref "C81") (pin "2") (pinfunction "2_2") (pintype "passive"))
      (node (ref "C82") (pin "2") (pinfunction "2_2") (pintype "passive"))
      (node (ref "C83") (pin "2") (pinfunction "2_2") (pintype "passive"))
      (node (ref "C84") (pin "2") (pinfunction "2_2") (pintype "passive"))
      (node (ref "C85") (pin "2") (pinfunction "2_2") (pintype "passive"))
      (node (ref "C86") (pin "2") (pinfunction "2_2") (pintype "passive"))
      (node (ref "C87") (pin "2") (pinfunction "2_2") (pintype "passive"))
      (node (ref "C88") (pin "2") (pinfunction "2_2") (pintype "passive"))
      (node (ref "C89") (pin "2") (pinfunction "2_2") (pintype "passive"))
      (node (ref "C9") (pin "2") (pinfunction "2_2") (pintype "passive"))
      (node (ref "C90") (pin "2") (pinfunction "2_2") (pintype "passive"))
      (node (ref "C91") (pin "2") (pinfunction "2_2") (pintype "passive"))
      (node (ref "C92") (pin "2") (pinfunction "2_2") (pintype "passive"))
      (node (ref "C93") (pin "2") (pinfunction "2_2") (pintype "passive"))
      (node (ref "C94") (pin "2") (pinfunction "2_2") (pintype "passive"))
      (node (ref "C95") (pin "2") (pinfunction "2_2") (pintype "passive"))
      (node (ref "C96") (pin "2") (pinfunction "2_2") (pintype "passive"))
      (node (ref "C97") (pin "2") (pinfunction "2_2") (pintype "passive"))
      (node (ref "C98") (pin "2") (pinfunction "2_2") (pintype "passive"))
      (node (ref "CON2") (pin "3@1") (pinfunction "1_3@1") (pintype "passive"))
      (node (ref "CON2") (pin "3@2") (pinfunction "1_3@2") (pintype "passive"))
      (node (ref "CON3") (pin "4") (pinfunction "GND_4") (pintype "passive"))
      (node (ref "D1") (pin "3") (pinfunction "3_3") (pintype "passive"))
      (node (ref "G1") (pin "-") (pinfunction "-_-") (pintype "passive"))
      (node (ref "IC1") (pin "15") (pinfunction "GND_15") (pintype "power_in"))
      (node (ref "IC2") (pin "5") (pinfunction "GND_5") (pintype "power_in"))
      (node (ref "IC3") (pin "29") (pinfunction "GND_29") (pintype "power_in"))
      (node (ref "IC4") (pin "4") (pinfunction "GND_4") (pintype "power_in"))
      (node (ref "IC5") (pin "10") (pinfunction "VSS_10") (pintype "power_in"))
      (node (ref "IC5") (pin "27") (pinfunction "VSS_27") (pintype "power_in"))
      (node (ref "IC5") (pin "49") (pinfunction "VSS_49") (pintype "power_in"))
      (node (ref "IC5") (pin "74") (pinfunction "VSS_74") (pintype "power_in"))
      (node (ref "IC5") (pin "99") (pinfunction "VSS_99") (pintype "power_in"))
      (node (ref "L4") (pin "1") (pinfunction "1_1") (pintype "passive"))
      (node (ref "L9") (pin "1") (pinfunction "1_1") (pintype "passive"))
      (node (ref "LED3") (pin "C") (pinfunction "C_C") (pintype "passive"))
      (node (ref "OK1") (pin "2") (pinfunction "C_2") (pintype "passive"))
      (node (ref "OK1") (pin "4") (pinfunction "C_4") (pintype "passive"))
      (node (ref "OK1") (pin "6") (pinfunction "C_6") (pintype "passive"))
      (node (ref "OK1") (pin "8") (pinfunction "C_8") (pintype "passive"))
      (node (ref "OK10") (pin "11") (pinfunction "EMIT_11") (pintype "passive"))
      (node (ref "OK10") (pin "13") (pinfunction "EMIT_13") (pintype "passive"))
      (node (ref "OK10") (pin "15") (pinfunction "EMIT_15") (pintype "passive"))
      (node (ref "OK10") (pin "9") (pinfunction "EMIT_9") (pintype "passive"))
      (node (ref "OK11") (pin "11") (pinfunction "EMIT_11") (pintype "passive"))
      (node (ref "OK11") (pin "13") (pinfunction "EMIT_13") (pintype "passive"))
      (node (ref "OK11") (pin "15") (pinfunction "EMIT_15") (pintype "passive"))
      (node (ref "OK11") (pin "9") (pinfunction "EMIT_9") (pintype "passive"))
      (node (ref "OK2") (pin "2") (pinfunction "C_2") (pintype "passive"))
      (node (ref "OK2") (pin "4") (pinfunction "C_4") (pintype "passive"))
      (node (ref "OK2") (pin "6") (pinfunction "C_6") (pintype "passive"))
      (node (ref "OK2") (pin "8") (pinfunction "C_8") (pintype "passive"))
      (node (ref "OK3") (pin "2") (pinfunction "C_2") (pintype "passive"))
      (node (ref "OK3") (pin "4") (pinfunction "C_4") (pintype "passive"))
      (node (ref "OK3") (pin "6") (pinfunction "C_6") (pintype "passive"))
      (node (ref "OK3") (pin "8") (pinfunction "C_8") (pintype "passive"))
      (node (ref "OK4") (pin "2") (pinfunction "C_2") (pintype "passive"))
      (node (ref "OK4") (pin "4") (pinfunction "C_4") (pintype "passive"))
      (node (ref "OK4") (pin "6") (pinfunction "C_6") (pintype "passive"))
      (node (ref "OK4") (pin "8") (pinfunction "C_8") (pintype "passive"))
      (node (ref "OK5") (pin "2") (pinfunction "C_2") (pintype "passive"))
      (node (ref "OK5") (pin "4") (pinfunction "C_4") (pintype "passive"))
      (node (ref "OK5") (pin "6") (pinfunction "C_6") (pintype "passive"))
      (node (ref "OK5") (pin "8") (pinfunction "C_8") (pintype "passive"))
      (node (ref "OK6") (pin "2") (pinfunction "C_2") (pintype "passive"))
      (node (ref "OK6") (pin "4") (pinfunction "C_4") (pintype "passive"))
      (node (ref "OK6") (pin "6") (pinfunction "C_6") (pintype "passive"))
      (node (ref "OK6") (pin "8") (pinfunction "C_8") (pintype "passive"))
      (node (ref "OK7") (pin "11") (pinfunction "EMIT_11") (pintype "passive"))
      (node (ref "OK7") (pin "13") (pinfunction "EMIT_13") (pintype "passive"))
      (node (ref "OK7") (pin "15") (pinfunction "EMIT_15") (pintype "passive"))
      (node (ref "OK7") (pin "9") (pinfunction "EMIT_9") (pintype "passive"))
      (node (ref "OK8") (pin "11") (pinfunction "EMIT_11") (pintype "passive"))
      (node (ref "OK8") (pin "13") (pinfunction "EMIT_13") (pintype "passive"))
      (node (ref "OK8") (pin "15") (pinfunction "EMIT_15") (pintype "passive"))
      (node (ref "OK8") (pin "9") (pinfunction "EMIT_9") (pintype "passive"))
      (node (ref "OK9") (pin "11") (pinfunction "EMIT_11") (pintype "passive"))
      (node (ref "OK9") (pin "13") (pinfunction "EMIT_13") (pintype "passive"))
      (node (ref "OK9") (pin "15") (pinfunction "EMIT_15") (pintype "passive"))
      (node (ref "OK9") (pin "9") (pinfunction "EMIT_9") (pintype "passive"))
      (node (ref "R1") (pin "1") (pinfunction "1_1") (pintype "passive"))
      (node (ref "R12") (pin "1") (pinfunction "1_1") (pintype "passive"))
      (node (ref "R15") (pin "1") (pinfunction "1_1") (pintype "passive"))
      (node (ref "R17") (pin "1") (pinfunction "1_1") (pintype "passive"))
      (node (ref "R27") (pin "1") (pinfunction "1_1") (pintype "passive"))
      (node (ref "R29") (pin "1") (pinfunction "1_1") (pintype "passive"))
      (node (ref "R31") (pin "1") (pinfunction "1_1") (pintype "passive"))
      (node (ref "R32") (pin "1") (pinfunction "1_1") (pintype "passive"))
      (node (ref "R33") (pin "1") (pinfunction "1_1") (pintype "passive"))
      (node (ref "R39") (pin "1") (pinfunction "1_1") (pintype "passive"))
      (node (ref "R6") (pin "1") (pinfunction "1_1") (pintype "passive"))
      (node (ref "U1") (pin "2") (pinfunction "GND_2") (pintype "power_in"))
      (node (ref "X1") (pin "5") (pinfunction "5_5") (pintype "passive"))
      (node (ref "X1") (pin "9") (pinfunction "9_9") (pintype "passive"))
      (node (ref "XT1") (pin "2@1") (pinfunction "1_2@1") (pintype "passive"))
      (node (ref "XT1") (pin "2@2") (pinfunction "1_2@2") (pintype "passive"))
    )
    (net (code "91") (name "GND1") (class "Default")
      (node (ref "C45") (pin "2") (pinfunction "2_2") (pintype "passive"))
      (node (ref "C46") (pin "2") (pinfunction "2_2") (pintype "passive"))
      (node (ref "C47") (pin "2") (pinfunction "2_2") (pintype "passive"))
      (node (ref "C48") (pin "2") (pinfunction "2_2") (pintype "passive"))
      (node (ref "C49") (pin "2") (pinfunction "2_2") (pintype "passive"))
      (node (ref "C50") (pin "2") (pinfunction "2_2") (pintype "passive"))
      (node (ref "C51") (pin "2") (pinfunction "2_2") (pintype "passive"))
      (node (ref "C52") (pin "2") (pinfunction "2_2") (pintype "passive"))
      (node (ref "C53") (pin "2") (pinfunction "2_2") (pintype "passive"))
      (node (ref "C54") (pin "2") (pinfunction "2_2") (pintype "passive"))
      (node (ref "C55") (pin "2") (pinfunction "2_2") (pintype "passive"))
      (node (ref "C56") (pin "2") (pinfunction "2_2") (pintype "passive"))
      (node (ref "C57") (pin "2") (pinfunction "2_2") (pintype "passive"))
      (node (ref "C58") (pin "2") (pinfunction "2_2") (pintype "passive"))
      (node (ref "C59") (pin "2") (pinfunction "2_2") (pintype "passive"))
      (node (ref "C60") (pin "2") (pinfunction "2_2") (pintype "passive"))
      (node (ref "C61") (pin "2") (pinfunction "2_2") (pintype "passive"))
      (node (ref "C62") (pin "2") (pinfunction "2_2") (pintype "passive"))
      (node (ref "C63") (pin "2") (pinfunction "2_2") (pintype "passive"))
      (node (ref "C64") (pin "2") (pinfunction "2_2") (pintype "passive"))
      (node (ref "C65") (pin "2") (pinfunction "2_2") (pintype "passive"))
      (node (ref "C66") (pin "2") (pinfunction "2_2") (pintype "passive"))
      (node (ref "C67") (pin "2") (pinfunction "2_2") (pintype "passive"))
      (node (ref "C68") (pin "2") (pinfunction "2_2") (pintype "passive"))
      (node (ref "C69") (pin "2") (pinfunction "2_2") (pintype "passive"))
      (node (ref "C70") (pin "2") (pinfunction "2_2") (pintype "passive"))
      (node (ref "C71") (pin "2") (pinfunction "2_2") (pintype "passive"))
      (node (ref "C72") (pin "2") (pinfunction "2_2") (pintype "passive"))
      (node (ref "C73") (pin "2") (pinfunction "2_2") (pintype "passive"))
      (node (ref "C74") (pin "2") (pinfunction "2_2") (pintype "passive"))
      (node (ref "C75") (pin "2") (pinfunction "2_2") (pintype "passive"))
      (node (ref "C76") (pin "2") (pinfunction "2_2") (pintype "passive"))
      (node (ref "C77") (pin "2") (pinfunction "2_2") (pintype "passive"))
      (node (ref "C78") (pin "2") (pinfunction "2_2") (pintype "passive"))
      (node (ref "CON4") (pin "A1") (pinfunction "A1_A1") (pintype "passive"))
      (node (ref "EC1") (pin "-") (pinfunction "-_-") (pintype "passive"))
      (node (ref "EC2") (pin "-") (pinfunction "-_-") (pintype "passive"))
      (node (ref "EC3") (pin "-") (pinfunction "-_-") (pintype "passive"))
      (node (ref "IC6") (pin "9") (pinfunction "GND_9") (pintype "power_in"))
      (node (ref "IC7") (pin "9") (pinfunction "GND_9") (pintype "power_in"))
      (node (ref "IC8") (pin "9") (pinfunction "GND_9") (pintype "power_in"))
    )
    (net (code "92") (name "GNDRF") (class "Default")
      (node (ref "C1") (pin "2") (pinfunction "2_2") (pintype "passive"))
      (node (ref "C12") (pin "2") (pinfunction "2_2") (pintype "passive"))
      (node (ref "C13") (pin "2") (pinfunction "2_2") (pintype "passive"))
      (node (ref "C17") (pin "2") (pinfunction "2_2") (pintype "passive"))
      (node (ref "C18") (pin "2") (pinfunction "2_2") (pintype "passive"))
      (node (ref "C19") (pin "2") (pinfunction "2_2") (pintype "passive"))
      (node (ref "C21") (pin "2") (pinfunction "2_2") (pintype "passive"))
      (node (ref "C23") (pin "2") (pinfunction "2_2") (pintype "passive"))
      (node (ref "C24") (pin "2") (pinfunction "2_2") (pintype "passive"))
      (node (ref "C25") (pin "2") (pinfunction "2_2") (pintype "passive"))
      (node (ref "C26") (pin "2") (pinfunction "2_2") (pintype "passive"))
      (node (ref "C27") (pin "2") (pinfunction "2_2") (pintype "passive"))
      (node (ref "C6") (pin "2") (pinfunction "2_2") (pintype "passive"))
      (node (ref "C8") (pin "2") (pinfunction "2_2") (pintype "passive"))
      (node (ref "IC3") (pin "14") (pinfunction "AGND_14") (pintype "power_in"))
      (node (ref "IC3") (pin "16") (pinfunction "AGND_16") (pintype "power_in"))
      (node (ref "IC3") (pin "19") (pinfunction "AGND_19") (pintype "power_in"))
      (node (ref "IC3") (pin "3") (pinfunction "AGND_3") (pintype "bidirectional"))
      (node (ref "IC3") (pin "48") (pinfunction "AGND_48") (pintype "power_in"))
      (node (ref "IC3") (pin "9") (pinfunction "AGND_9") (pintype "power_in"))
      (node (ref "L4") (pin "2") (pinfunction "2_2") (pintype "passive"))
      (node (ref "LED1") (pin "C") (pinfunction "C_C") (pintype "passive"))
      (node (ref "LED2") (pin "C") (pinfunction "C_C") (pintype "passive"))
      (node (ref "R16") (pin "2") (pinfunction "2_2") (pintype "passive"))
    )
    (net (code "93") (name "LINKLED") (class "Default")
      (node (ref "IC3") (pin "25") (pinfunction "LINKLED_25") (pintype "output"))
      (node (ref "R3") (pin "2") (pinfunction "2_2") (pintype "passive"))
    )
    (net (code "94") (name "MCU_NRST") (class "Default")
      (node (ref "C33") (pin "1") (pinfunction "1_1") (pintype "passive"))
      (node (ref "IC5") (pin "14") (pinfunction "NRST_14") (pintype "bidirectional"))
      (node (ref "R38") (pin "1") (pinfunction "1_1") (pintype "passive"))
    )
    (net (code "95") (name "MCU_OSC_IN") (class "Default")
      (node (ref "C34") (pin "1") (pinfunction "1_1") (pintype "passive"))
      (node (ref "IC5") (pin "12") (pinfunction "OSC_IN_12") (pintype "input"))
      (node (ref "XTAL3") (pin "1") (pinfunction "1_1") (pintype "passive"))
    )
    (net (code "96") (name "MCU_OSC_OUT") (class "Default")
      (node (ref "C35") (pin "1") (pinfunction "1_1") (pintype "passive"))
      (node (ref "IC5") (pin "13") (pinfunction "OSC_OUT_13") (pintype "bidirectional"))
      (node (ref "XTAL3") (pin "2") (pinfunction "2_2") (pintype "passive"))
    )
    (net (code "97") (name "Net-(C1-Pad1)") (class "Default")
      (node (ref "C1") (pin "1") (pinfunction "1_1") (pintype "passive"))
      (node (ref "CON1") (pin "SS@1") (pinfunction "SHIELD_SS@1") (pintype "passive"))
      (node (ref "CON1") (pin "SS@2") (pinfunction "SHIELD_SS@2") (pintype "passive"))
    )
    (net (code "98") (name "Net-(C24-Pad1)") (class "Default")
      (node (ref "C24") (pin "1") (pinfunction "1_1") (pintype "passive"))
      (node (ref "R22") (pin "1") (pinfunction "1_1") (pintype "passive"))
      (node (ref "XTAL1") (pin "2") (pinfunction "2_2") (pintype "passive"))
    )
    (net (code "99") (name "Net-(C36-Pad1)") (class "Default")
      (node (ref "C36") (pin "1") (pinfunction "1_1") (pintype "passive"))
      (node (ref "C37") (pin "1") (pinfunction "1_1") (pintype "passive"))
      (node (ref "C38") (pin "1") (pinfunction "1_1") (pintype "passive"))
      (node (ref "C39") (pin "1") (pinfunction "1_1") (pintype "passive"))
      (node (ref "C40") (pin "1") (pinfunction "1_1") (pintype "passive"))
      (node (ref "C41") (pin "1") (pinfunction "1_1") (pintype "passive"))
      (node (ref "C42") (pin "1") (pinfunction "1_1") (pintype "passive"))
      (node (ref "C43") (pin "1") (pinfunction "1_1") (pintype "passive"))
      (node (ref "C44") (pin "1") (pinfunction "1_1") (pintype "passive"))
      (node (ref "L7") (pin "2") (pinfunction "2_2") (pintype "passive"))
    )
    (net (code "100") (name "Net-(CON1-P3)") (class "Default")
      (node (ref "C5") (pin "1") (pinfunction "1_1") (pintype "passive"))
      (node (ref "CON1") (pin "3") (pinfunction "P3_3") (pintype "passive"))
    )
    (net (code "101") (name "Net-(CON1-P4)") (class "Default")
      (node (ref "C8") (pin "1") (pinfunction "1_1") (pintype "passive"))
      (node (ref "CON1") (pin "4") (pinfunction "P4_4") (pintype "passive"))
      (node (ref "R10") (pin "1") (pinfunction "1_1") (pintype "passive"))
    )
    (net (code "102") (name "Net-(CON1-P5)") (class "Default")
      (node (ref "C6") (pin "1") (pinfunction "1_1") (pintype "passive"))
      (node (ref "CON1") (pin "5") (pinfunction "P5_5") (pintype "passive"))
      (node (ref "R11") (pin "2") (pinfunction "2_2") (pintype "passive"))
      (node (ref "R9") (pin "2") (pinfunction "2_2") (pintype "passive"))
    )
    (net (code "103") (name "Net-(CON1-P6)") (class "Default")
      (node (ref "C4") (pin "1") (pinfunction "1_1") (pintype "passive"))
      (node (ref "CON1") (pin "6") (pinfunction "P6_6") (pintype "passive"))
    )
    (net (code "104") (name "Net-(CON1-Pad10)") (class "Default")
      (node (ref "CON1") (pin "10") (pinfunction "10_10") (pintype "passive"))
      (node (ref "R3") (pin "1") (pinfunction "1_1") (pintype "passive"))
    )
    (net (code "105") (name "Net-(CON1-Pad11)") (class "Default")
      (node (ref "CON1") (pin "11") (pinfunction "11_11") (pintype "passive"))
      (node (ref "R4") (pin "1") (pinfunction "1_1") (pintype "passive"))
    )
    (net (code "106") (name "Net-(D23-PadA)") (class "Default")
      (node (ref "D23") (pin "A") (pinfunction "A_A") (pintype "passive"))
      (node (ref "X42") (pin "1@1") (pinfunction "1_1@1") (pintype "passive"))
      (node (ref "X42") (pin "2@1") (pinfunction "1_2@1") (pintype "passive"))
    )
    (net (code "107") (name "Net-(D23-PadC)") (class "Default")
      (node (ref "D23") (pin "C") (pinfunction "C_C") (pintype "passive"))
      (node (ref "R150") (pin "2") (pinfunction "2_2") (pintype "passive"))
      (node (ref "R154") (pin "1") (pinfunction "1_1") (pintype "passive"))
    )
    (net (code "108") (name "Net-(D24-PadA)") (class "Default")
      (node (ref "D24") (pin "A") (pinfunction "A_A") (pintype "passive"))
      (node (ref "X44") (pin "1@1") (pinfunction "1_1@1") (pintype "passive"))
      (node (ref "X44") (pin "2@1") (pinfunction "1_2@1") (pintype "passive"))
    )
    (net (code "109") (name "Net-(D24-PadC)") (class "Default")
      (node (ref "D24") (pin "C") (pinfunction "C_C") (pintype "passive"))
      (node (ref "R151") (pin "2") (pinfunction "2_2") (pintype "passive"))
      (node (ref "R155") (pin "1") (pinfunction "1_1") (pintype "passive"))
    )
    (net (code "110") (name "Net-(D25-PadA)") (class "Default")
      (node (ref "D25") (pin "A") (pinfunction "A_A") (pintype "passive"))
      (node (ref "X46") (pin "1@1") (pinfunction "1_1@1") (pintype "passive"))
      (node (ref "X46") (pin "2@1") (pinfunction "1_2@1") (pintype "passive"))
    )
    (net (code "111") (name "Net-(D25-PadC)") (class "Default")
      (node (ref "D25") (pin "C") (pinfunction "C_C") (pintype "passive"))
      (node (ref "R152") (pin "2") (pinfunction "2_2") (pintype "passive"))
      (node (ref "R156") (pin "1") (pinfunction "1_1") (pintype "passive"))
    )
    (net (code "112") (name "Net-(D26-PadA)") (class "Default")
      (node (ref "D26") (pin "A") (pinfunction "A_A") (pintype "passive"))
      (node (ref "X48") (pin "1@1") (pinfunction "1_1@1") (pintype "passive"))
      (node (ref "X48") (pin "2@1") (pinfunction "1_2@1") (pintype "passive"))
    )
    (net (code "113") (name "Net-(D26-PadC)") (class "Default")
      (node (ref "D26") (pin "C") (pinfunction "C_C") (pintype "passive"))
      (node (ref "R153") (pin "2") (pinfunction "2_2") (pintype "passive"))
      (node (ref "R157") (pin "1") (pinfunction "1_1") (pintype "passive"))
    )
    (net (code "114") (name "Net-(D28-PadA)") (class "Default")
      (node (ref "D28") (pin "A") (pinfunction "A_A") (pintype "passive"))
      (node (ref "X50") (pin "1@1") (pinfunction "1_1@1") (pintype "passive"))
      (node (ref "X50") (pin "2@1") (pinfunction "1_2@1") (pintype "passive"))
    )
    (net (code "115") (name "Net-(D28-PadC)") (class "Default")
      (node (ref "D28") (pin "C") (pinfunction "C_C") (pintype "passive"))
      (node (ref "R175") (pin "2") (pinfunction "2_2") (pintype "passive"))
      (node (ref "R179") (pin "1") (pinfunction "1_1") (pintype "passive"))
    )
    (net (code "116") (name "Net-(D29-PadA)") (class "Default")
      (node (ref "D29") (pin "A") (pinfunction "A_A") (pintype "passive"))
      (node (ref "X52") (pin "1@1") (pinfunction "1_1@1") (pintype "passive"))
      (node (ref "X52") (pin "2@1") (pinfunction "1_2@1") (pintype "passive"))
    )
    (net (code "117") (name "Net-(D29-PadC)") (class "Default")
      (node (ref "D29") (pin "C") (pinfunction "C_C") (pintype "passive"))
      (node (ref "R176") (pin "2") (pinfunction "2_2") (pintype "passive"))
      (node (ref "R180") (pin "1") (pinfunction "1_1") (pintype "passive"))
    )
    (net (code "118") (name "Net-(D30-PadA)") (class "Default")
      (node (ref "D30") (pin "A") (pinfunction "A_A") (pintype "passive"))
      (node (ref "X54") (pin "1@1") (pinfunction "1_1@1") (pintype "passive"))
      (node (ref "X54") (pin "2@1") (pinfunction "1_2@1") (pintype "passive"))
    )
    (net (code "119") (name "Net-(D30-PadC)") (class "Default")
      (node (ref "D30") (pin "C") (pinfunction "C_C") (pintype "passive"))
      (node (ref "R177") (pin "2") (pinfunction "2_2") (pintype "passive"))
      (node (ref "R181") (pin "1") (pinfunction "1_1") (pintype "passive"))
    )
    (net (code "120") (name "Net-(D31-PadA)") (class "Default")
      (node (ref "D31") (pin "A") (pinfunction "A_A") (pintype "passive"))
      (node (ref "X56") (pin "1@1") (pinfunction "1_1@1") (pintype "passive"))
      (node (ref "X56") (pin "2@1") (pinfunction "1_2@1") (pintype "passive"))
    )
    (net (code "121") (name "Net-(D31-PadC)") (class "Default")
      (node (ref "D31") (pin "C") (pinfunction "C_C") (pintype "passive"))
      (node (ref "R178") (pin "2") (pinfunction "2_2") (pintype "passive"))
      (node (ref "R182") (pin "1") (pinfunction "1_1") (pintype "passive"))
    )
    (net (code "122") (name "Net-(D32-PadA)") (class "Default")
      (node (ref "D32") (pin "A") (pinfunction "A_A") (pintype "passive"))
      (node (ref "X82") (pin "1@1") (pinfunction "1_1@1") (pintype "passive"))
      (node (ref "X82") (pin "2@1") (pinfunction "1_2@1") (pintype "passive"))
    )
    (net (code "123") (name "Net-(D32-PadC)") (class "Default")
      (node (ref "D32") (pin "C") (pinfunction "C_C") (pintype "passive"))
      (node (ref "R199") (pin "2") (pinfunction "2_2") (pintype "passive"))
      (node (ref "R203") (pin "1") (pinfunction "1_1") (pintype "passive"))
    )
    (net (code "124") (name "Net-(D33-PadA)") (class "Default")
      (node (ref "D33") (pin "A") (pinfunction "A_A") (pintype "passive"))
      (node (ref "X84") (pin "1@1") (pinfunction "1_1@1") (pintype "passive"))
      (node (ref "X84") (pin "2@1") (pinfunction "1_2@1") (pintype "passive"))
    )
    (net (code "125") (name "Net-(D33-PadC)") (class "Default")
      (node (ref "D33") (pin "C") (pinfunction "C_C") (pintype "passive"))
      (node (ref "R200") (pin "2") (pinfunction "2_2") (pintype "passive"))
      (node (ref "R204") (pin "1") (pinfunction "1_1") (pintype "passive"))
    )
    (net (code "126") (name "Net-(D34-PadA)") (class "Default")
      (node (ref "D34") (pin "A") (pinfunction "A_A") (pintype "passive"))
      (node (ref "X86") (pin "1@1") (pinfunction "1_1@1") (pintype "passive"))
      (node (ref "X86") (pin "2@1") (pinfunction "1_2@1") (pintype "passive"))
    )
    (net (code "127") (name "Net-(D34-PadC)") (class "Default")
      (node (ref "D34") (pin "C") (pinfunction "C_C") (pintype "passive"))
      (node (ref "R201") (pin "2") (pinfunction "2_2") (pintype "passive"))
      (node (ref "R205") (pin "1") (pinfunction "1_1") (pintype "passive"))
    )
    (net (code "128") (name "Net-(D35-PadA)") (class "Default")
      (node (ref "D35") (pin "A") (pinfunction "A_A") (pintype "passive"))
      (node (ref "X88") (pin "1@1") (pinfunction "1_1@1") (pintype "passive"))
      (node (ref "X88") (pin "2@1") (pinfunction "1_2@1") (pintype "passive"))
    )
    (net (code "129") (name "Net-(D35-PadC)") (class "Default")
      (node (ref "D35") (pin "C") (pinfunction "C_C") (pintype "passive"))
      (node (ref "R202") (pin "2") (pinfunction "2_2") (pintype "passive"))
      (node (ref "R206") (pin "1") (pinfunction "1_1") (pintype "passive"))
    )
    (net (code "130") (name "Net-(DB1-+)") (class "Default")
      (node (ref "C120") (pin "+") (pinfunction "+_+") (pintype "passive"))
      (node (ref "C121") (pin "1") (pinfunction "1_1") (pintype "passive"))
      (node (ref "D27") (pin "C") (pinfunction "C_C") (pintype "passive"))
      (node (ref "DB1") (pin "DC+") (pinfunction "+_DC+") (pintype "passive"))
      (node (ref "IC14") (pin "IN") (pinfunction "IN_IN") (pintype "input"))
      (node (ref "R174") (pin "1") (pinfunction "1_1") (pintype "passive"))
    )
    (net (code "131") (name "Net-(DB1-A1)") (class "Default")
      (node (ref "DB1") (pin "AC1") (pinfunction "A1_AC1") (pintype "passive"))
      (node (ref "XT3") (pin "1@1") (pinfunction "1_1@1") (pintype "passive"))
      (node (ref "XT3") (pin "1@2") (pinfunction "1_1@2") (pintype "passive"))
    )
    (net (code "132") (name "Net-(DB1-A2)") (class "Default")
      (node (ref "DB1") (pin "AC2") (pinfunction "A2_AC2") (pintype "passive"))
      (node (ref "XT3") (pin "2@1") (pinfunction "1_2@1") (pintype "passive"))
      (node (ref "XT3") (pin "2@2") (pinfunction "1_2@2") (pintype "passive"))
    )
    (net (code "133") (name "Net-(DB2-+)") (class "Default")
      (node (ref "C102") (pin "+") (pinfunction "+_+") (pintype "passive"))
      (node (ref "C103") (pin "1") (pinfunction "1_1") (pintype "passive"))
      (node (ref "D22") (pin "C") (pinfunction "C_C") (pintype "passive"))
      (node (ref "DB2") (pin "DC+") (pinfunction "+_DC+") (pintype "passive"))
      (node (ref "IC10") (pin "1") (pinfunction "VIN_1") (pintype "bidirectional"))
      (node (ref "R149") (pin "1") (pinfunction "1_1") (pintype "passive"))
    )
    (net (code "134") (name "Net-(DB2-A1)") (class "Default")
      (node (ref "DB2") (pin "AC1") (pinfunction "A1_AC1") (pintype "passive"))
      (node (ref "XT2") (pin "1@1") (pinfunction "1_1@1") (pintype "passive"))
      (node (ref "XT2") (pin "1@2") (pinfunction "1_1@2") (pintype "passive"))
    )
    (net (code "135") (name "Net-(DB2-A2)") (class "Default")
      (node (ref "DB2") (pin "AC2") (pinfunction "A2_AC2") (pintype "passive"))
      (node (ref "XT2") (pin "2@1") (pinfunction "1_2@1") (pintype "passive"))
      (node (ref "XT2") (pin "2@2") (pinfunction "1_2@2") (pintype "passive"))
    )
    (net (code "136") (name "Net-(IC1-C1+)") (class "Default")
      (node (ref "C10") (pin "2") (pinfunction "2_2") (pintype "passive"))
      (node (ref "IC1") (pin "1") (pinfunction "C1+_1") (pintype "bidirectional"))
    )
    (net (code "137") (name "Net-(IC1-C1-)") (class "Default")
      (node (ref "C10") (pin "1") (pinfunction "1_1") (pintype "passive"))
      (node (ref "IC1") (pin "3") (pinfunction "C1-_3") (pintype "bidirectional"))
    )
    (net (code "138") (name "Net-(IC1-C2+)") (class "Default")
      (node (ref "C11") (pin "2") (pinfunction "2_2") (pintype "passive"))
      (node (ref "IC1") (pin "4") (pinfunction "C2+_4") (pintype "bidirectional"))
    )
    (net (code "139") (name "Net-(IC1-C2-)") (class "Default")
      (node (ref "C11") (pin "1") (pinfunction "1_1") (pintype "passive"))
      (node (ref "IC1") (pin "5") (pinfunction "C2-_5") (pintype "bidirectional"))
    )
    (net (code "140") (name "Net-(IC1-R1IN)") (class "Default")
      (node (ref "IC1") (pin "13") (pinfunction "R1IN_13") (pintype "input"))
      (node (ref "R5") (pin "2") (pinfunction "2_2") (pintype "passive"))
    )
    (net (code "141") (name "Net-(IC1-R2IN)") (class "Default")
      (node (ref "IC1") (pin "8") (pinfunction "R2IN_8") (pintype "input"))
      (node (ref "R6") (pin "2") (pinfunction "2_2") (pintype "passive"))
    )
    (net (code "142") (name "Net-(IC1-T1OUT)") (class "Default")
      (node (ref "IC1") (pin "14") (pinfunction "T1OUT_14") (pintype "output"))
      (node (ref "R2") (pin "2") (pinfunction "2_2") (pintype "passive"))
    )
    (net (code "143") (name "Net-(IC1-T2IN)") (class "Default")
      (node (ref "IC1") (pin "10") (pinfunction "T2IN_10") (pintype "input"))
      (node (ref "R12") (pin "2") (pinfunction "2_2") (pintype "passive"))
    )
    (net (code "144") (name "Net-(IC1-V+)") (class "Default")
      (node (ref "C2") (pin "1") (pinfunction "1_1") (pintype "passive"))
      (node (ref "IC1") (pin "2") (pinfunction "V+_2") (pintype "bidirectional"))
    )
    (net (code "145") (name "Net-(IC1-V-)") (class "Default")
      (node (ref "C3") (pin "1") (pinfunction "1_1") (pintype "passive"))
      (node (ref "IC1") (pin "6") (pinfunction "V-_6") (pintype "bidirectional"))
    )
    (net (code "146") (name "Net-(IC1-VCC)") (class "Default")
      (node (ref "C7") (pin "1") (pinfunction "1_1") (pintype "passive"))
      (node (ref "C9") (pin "1") (pinfunction "1_1") (pintype "passive"))
      (node (ref "IC1") (pin "16") (pinfunction "VCC_16") (pintype "power_in"))
      (node (ref "L1") (pin "1") (pinfunction "1_1") (pintype "passive"))
    )
    (net (code "147") (name "Net-(IC2-A)") (class "Default")
      (node (ref "CON2") (pin "2@1") (pinfunction "1_2@1") (pintype "passive"))
      (node (ref "CON2") (pin "2@2") (pinfunction "1_2@2") (pintype "passive"))
      (node (ref "D1") (pin "1") (pinfunction "1_1") (pintype "passive"))
      (node (ref "IC2") (pin "6") (pinfunction "A_6") (pintype "passive"))
      (node (ref "R13") (pin "1") (pinfunction "1_1") (pintype "passive"))
      (node (ref "R15") (pin "2") (pinfunction "2_2") (pintype "passive"))
    )
    (net (code "148") (name "Net-(IC2-B)") (class "Default")
      (node (ref "CON2") (pin "1@1") (pinfunction "1_1@1") (pintype "passive"))
      (node (ref "CON2") (pin "1@2") (pinfunction "1_1@2") (pintype "passive"))
      (node (ref "D1") (pin "2") (pinfunction "2_2") (pintype "passive"))
      (node (ref "IC2") (pin "7") (pinfunction "B_7") (pintype "passive"))
      (node (ref "R13") (pin "2") (pinfunction "2_2") (pintype "passive"))
      (node (ref "R14") (pin "1") (pinfunction "1_1") (pintype "passive"))
    )
    (net (code "149") (name "Net-(IC2-DE)") (class "Default")
      (node (ref "IC2") (pin "2") (pinfunction "~{RE}_2") (pintype "input"))
      (node (ref "IC2") (pin "3") (pinfunction "DE_3") (pintype "input"))
      (node (ref "R19") (pin "1") (pinfunction "1_1") (pintype "passive"))
    )
    (net (code "150") (name "Net-(IC2-DI)") (class "Default")
      (node (ref "IC2") (pin "4") (pinfunction "DI_4") (pintype "input"))
      (node (ref "R20") (pin "1") (pinfunction "1_1") (pintype "passive"))
    )
    (net (code "151") (name "Net-(IC2-RO)") (class "Default")
      (node (ref "IC2") (pin "1") (pinfunction "RO_1") (pintype "output"))
      (node (ref "R18") (pin "1") (pinfunction "1_1") (pintype "passive"))
    )
    (net (code "152") (name "Net-(IC2-VCC)") (class "Default")
      (node (ref "C14") (pin "1") (pinfunction "1_1") (pintype "passive"))
      (node (ref "IC2") (pin "8") (pinfunction "VCC_8") (pintype "power_in"))
      (node (ref "L2") (pin "1") (pinfunction "1_1") (pintype "passive"))
      (node (ref "R14") (pin "2") (pinfunction "2_2") (pintype "passive"))
    )
    (net (code "153") (name "Net-(IC4-VBAT)") (class "Default")
      (node (ref "C28") (pin "1") (pinfunction "1_1") (pintype "passive"))
      (node (ref "G1") (pin "+") (pinfunction "+_+") (pintype "passive"))
      (node (ref "IC4") (pin "3") (pinfunction "VBAT_3") (pintype "bidirectional"))
    )
    (net (code "154") (name "Net-(IC4-VDD)") (class "Default")
      (node (ref "C30") (pin "1") (pinfunction "1_1") (pintype "passive"))
      (node (ref "C31") (pin "1") (pinfunction "1_1") (pintype "passive"))
      (node (ref "IC4") (pin "8") (pinfunction "VDD_8") (pintype "power_in"))
      (node (ref "L6") (pin "2") (pinfunction "2_2") (pintype "passive"))
      (node (ref "R35") (pin "1") (pinfunction "1_1") (pintype "passive"))
      (node (ref "R36") (pin "1") (pinfunction "1_1") (pintype "passive"))
      (node (ref "R37") (pin "1") (pinfunction "1_1") (pintype "passive"))
    )
    (net (code "155") (name "Net-(IC6-I1)") (class "Default")
      (node (ref "C46") (pin "1") (pinfunction "1_1") (pintype "passive"))
      (node (ref "IC6") (pin "1") (pinfunction "I1_1") (pintype "input"))
      (node (ref "OK1") (pin "15") (pinfunction "EMIT_15") (pintype "passive"))
    )
    (net (code "156") (name "Net-(IC6-I2)") (class "Default")
      (node (ref "C47") (pin "1") (pinfunction "1_1") (pintype "passive"))
      (node (ref "IC6") (pin "2") (pinfunction "I2_2") (pintype "input"))
      (node (ref "OK1") (pin "13") (pinfunction "EMIT_13") (pintype "passive"))
    )
    (net (code "157") (name "Net-(IC6-I3)") (class "Default")
      (node (ref "C48") (pin "1") (pinfunction "1_1") (pintype "passive"))
      (node (ref "IC6") (pin "3") (pinfunction "I3_3") (pintype "input"))
      (node (ref "OK1") (pin "11") (pinfunction "EMIT_11") (pintype "passive"))
    )
    (net (code "158") (name "Net-(IC6-I4)") (class "Default")
      (node (ref "C49") (pin "1") (pinfunction "1_1") (pintype "passive"))
      (node (ref "IC6") (pin "4") (pinfunction "I4_4") (pintype "input"))
      (node (ref "OK1") (pin "9") (pinfunction "EMIT_9") (pintype "passive"))
    )
    (net (code "159") (name "Net-(IC6-I5)") (class "Default")
      (node (ref "C50") (pin "1") (pinfunction "1_1") (pintype "passive"))
      (node (ref "IC6") (pin "5") (pinfunction "I5_5") (pintype "input"))
      (node (ref "OK2") (pin "15") (pinfunction "EMIT_15") (pintype "passive"))
    )
    (net (code "160") (name "Net-(IC6-I6)") (class "Default")
      (node (ref "C51") (pin "1") (pinfunction "1_1") (pintype "passive"))
      (node (ref "IC6") (pin "6") (pinfunction "I6_6") (pintype "input"))
      (node (ref "OK2") (pin "13") (pinfunction "EMIT_13") (pintype "passive"))
    )
    (net (code "161") (name "Net-(IC6-I7)") (class "Default")
      (node (ref "C52") (pin "1") (pinfunction "1_1") (pintype "passive"))
      (node (ref "IC6") (pin "7") (pinfunction "I7_7") (pintype "input"))
      (node (ref "OK2") (pin "11") (pinfunction "EMIT_11") (pintype "passive"))
    )
    (net (code "162") (name "Net-(IC6-I8)") (class "Default")
      (node (ref "C53") (pin "1") (pinfunction "1_1") (pintype "passive"))
      (node (ref "IC6") (pin "8") (pinfunction "I8_8") (pintype "input"))
      (node (ref "OK2") (pin "9") (pinfunction "EMIT_9") (pintype "passive"))
    )
    (net (code "163") (name "Net-(IC7-I1)") (class "Default")
      (node (ref "C57") (pin "1") (pinfunction "1_1") (pintype "passive"))
      (node (ref "IC7") (pin "1") (pinfunction "I1_1") (pintype "input"))
      (node (ref "OK3") (pin "15") (pinfunction "EMIT_15") (pintype "passive"))
    )
    (net (code "164") (name "Net-(IC7-I2)") (class "Default")
      (node (ref "C58") (pin "1") (pinfunction "1_1") (pintype "passive"))
      (node (ref "IC7") (pin "2") (pinfunction "I2_2") (pintype "input"))
      (node (ref "OK3") (pin "13") (pinfunction "EMIT_13") (pintype "passive"))
    )
    (net (code "165") (name "Net-(IC7-I3)") (class "Default")
      (node (ref "C59") (pin "1") (pinfunction "1_1") (pintype "passive"))
      (node (ref "IC7") (pin "3") (pinfunction "I3_3") (pintype "input"))
      (node (ref "OK3") (pin "11") (pinfunction "EMIT_11") (pintype "passive"))
    )
    (net (code "166") (name "Net-(IC7-I4)") (class "Default")
      (node (ref "C60") (pin "1") (pinfunction "1_1") (pintype "passive"))
      (node (ref "IC7") (pin "4") (pinfunction "I4_4") (pintype "input"))
      (node (ref "OK3") (pin "9") (pinfunction "EMIT_9") (pintype "passive"))
    )
    (net (code "167") (name "Net-(IC7-I5)") (class "Default")
      (node (ref "C61") (pin "1") (pinfunction "1_1") (pintype "passive"))
      (node (ref "IC7") (pin "5") (pinfunction "I5_5") (pintype "input"))
      (node (ref "OK4") (pin "15") (pinfunction "EMIT_15") (pintype "passive"))
    )
    (net (code "168") (name "Net-(IC7-I6)") (class "Default")
      (node (ref "C62") (pin "1") (pinfunction "1_1") (pintype "passive"))
      (node (ref "IC7") (pin "6") (pinfunction "I6_6") (pintype "input"))
      (node (ref "OK4") (pin "13") (pinfunction "EMIT_13") (pintype "passive"))
    )
    (net (code "169") (name "Net-(IC7-I7)") (class "Default")
      (node (ref "C63") (pin "1") (pinfunction "1_1") (pintype "passive"))
      (node (ref "IC7") (pin "7") (pinfunction "I7_7") (pintype "input"))
      (node (ref "OK4") (pin "11") (pinfunction "EMIT_11") (pintype "passive"))
    )
    (net (code "170") (name "Net-(IC7-I8)") (class "Default")
      (node (ref "C64") (pin "1") (pinfunction "1_1") (pintype "passive"))
      (node (ref "IC7") (pin "8") (pinfunction "I8_8") (pintype "input"))
      (node (ref "OK4") (pin "9") (pinfunction "EMIT_9") (pintype "passive"))
    )
    (net (code "171") (name "Net-(IC8-I1)") (class "Default")
      (node (ref "C68") (pin "1") (pinfunction "1_1") (pintype "passive"))
      (node (ref "IC8") (pin "1") (pinfunction "I1_1") (pintype "input"))
      (node (ref "OK5") (pin "15") (pinfunction "EMIT_15") (pintype "passive"))
    )
    (net (code "172") (name "Net-(IC8-I2)") (class "Default")
      (node (ref "C69") (pin "1") (pinfunction "1_1") (pintype "passive"))
      (node (ref "IC8") (pin "2") (pinfunction "I2_2") (pintype "input"))
      (node (ref "OK5") (pin "13") (pinfunction "EMIT_13") (pintype "passive"))
    )
    (net (code "173") (name "Net-(IC8-I3)") (class "Default")
      (node (ref "C70") (pin "1") (pinfunction "1_1") (pintype "passive"))
      (node (ref "IC8") (pin "3") (pinfunction "I3_3") (pintype "input"))
      (node (ref "OK5") (pin "11") (pinfunction "EMIT_11") (pintype "passive"))
    )
    (net (code "174") (name "Net-(IC8-I4)") (class "Default")
      (node (ref "C71") (pin "1") (pinfunction "1_1") (pintype "passive"))
      (node (ref "IC8") (pin "4") (pinfunction "I4_4") (pintype "input"))
      (node (ref "OK5") (pin "9") (pinfunction "EMIT_9") (pintype "passive"))
    )
    (net (code "175") (name "Net-(IC8-I5)") (class "Default")
      (node (ref "C72") (pin "1") (pinfunction "1_1") (pintype "passive"))
      (node (ref "IC8") (pin "5") (pinfunction "I5_5") (pintype "input"))
      (node (ref "OK6") (pin "15") (pinfunction "EMIT_15") (pintype "passive"))
    )
    (net (code "176") (name "Net-(IC8-I6)") (class "Default")
      (node (ref "C73") (pin "1") (pinfunction "1_1") (pintype "passive"))
      (node (ref "IC8") (pin "6") (pinfunction "I6_6") (pintype "input"))
      (node (ref "OK6") (pin "13") (pinfunction "EMIT_13") (pintype "passive"))
    )
    (net (code "177") (name "Net-(IC8-I7)") (class "Default")
      (node (ref "C74") (pin "1") (pinfunction "1_1") (pintype "passive"))
      (node (ref "IC8") (pin "7") (pinfunction "I7_7") (pintype "input"))
      (node (ref "OK6") (pin "11") (pinfunction "EMIT_11") (pintype "passive"))
    )
    (net (code "178") (name "Net-(IC8-I8)") (class "Default")
      (node (ref "C75") (pin "1") (pinfunction "1_1") (pintype "passive"))
      (node (ref "IC8") (pin "8") (pinfunction "I8_8") (pintype "input"))
      (node (ref "OK6") (pin "9") (pinfunction "EMIT_9") (pintype "passive"))
    )
    (net (code "179") (name "Net-(IC12A-+IN)") (class "Default")
      (node (ref "C101") (pin "1") (pinfunction "1_1") (pintype "passive"))
      (node (ref "IC12") (pin "10") (pinfunction "+IN_10") (pintype "input"))
      (node (ref "IC12") (pin "12") (pinfunction "+IN_12") (pintype "input"))
      (node (ref "IC12") (pin "3") (pinfunction "+IN_3") (pintype "input"))
      (node (ref "IC12") (pin "5") (pinfunction "+IN_5") (pintype "input"))
      (node (ref "IC9") (pin "1") (pinfunction "C_1") (pintype "passive"))
      (node (ref "R148") (pin "1") (pinfunction "1_1") (pintype "passive"))
    )
    (net (code "180") (name "Net-(IC12A--IN)") (class "Default")
      (node (ref "IC12") (pin "1") (pinfunction "OUT_1") (pintype "output"))
      (node (ref "IC12") (pin "2") (pinfunction "-IN_2") (pintype "input"))
      (node (ref "R158") (pin "2") (pinfunction "2_2") (pintype "passive"))
      (node (ref "R159") (pin "2") (pinfunction "2_2") (pintype "passive"))
      (node (ref "R160") (pin "2") (pinfunction "2_2") (pintype "passive"))
      (node (ref "R161") (pin "2") (pinfunction "2_2") (pintype "passive"))
    )
    (net (code "181") (name "Net-(IC12B--IN)") (class "Default")
      (node (ref "IC12") (pin "6") (pinfunction "-IN_6") (pintype "input"))
      (node (ref "IC12") (pin "7") (pinfunction "OUT_7") (pintype "output"))
      (node (ref "R183") (pin "2") (pinfunction "2_2") (pintype "passive"))
      (node (ref "R184") (pin "2") (pinfunction "2_2") (pintype "passive"))
      (node (ref "R185") (pin "2") (pinfunction "2_2") (pintype "passive"))
      (node (ref "R186") (pin "2") (pinfunction "2_2") (pintype "passive"))
    )
    (net (code "182") (name "Net-(IC12C--IN)") (class "Default")
      (node (ref "IC12") (pin "8") (pinfunction "OUT_8") (pintype "output"))
      (node (ref "IC12") (pin "9") (pinfunction "-IN_9") (pintype "input"))
      (node (ref "R207") (pin "2") (pinfunction "2_2") (pintype "passive"))
      (node (ref "R208") (pin "2") (pinfunction "2_2") (pintype "passive"))
      (node (ref "R209") (pin "2") (pinfunction "2_2") (pintype "passive"))
      (node (ref "R210") (pin "2") (pinfunction "2_2") (pintype "passive"))
    )
    (net (code "183") (name "Net-(IC12E-V+)") (class "Default")
      (node (ref "C100") (pin "1") (pinfunction "1_1") (pintype "passive"))
      (node (ref "C99") (pin "1") (pinfunction "1_1") (pintype "passive"))
      (node (ref "IC12") (pin "4") (pinfunction "V+_4") (pintype "power_in"))
      (node (ref "L8") (pin "1") (pinfunction "1_1") (pintype "passive"))
      (node (ref "R148") (pin "2") (pinfunction "2_2") (pintype "passive"))
    )
    (net (code "184") (name "Net-(IC13A-+IN)") (class "Default")
      (node (ref "C106") (pin "1") (pinfunction "1_1") (pintype "passive"))
      (node (ref "IC13") (pin "3") (pinfunction "+IN_3") (pintype "input"))
      (node (ref "R154") (pin "2") (pinfunction "2_2") (pintype "passive"))
    )
    (net (code "185") (name "Net-(IC13A--IN)") (class "Default")
      (node (ref "C110") (pin "2") (pinfunction "2_2") (pintype "passive"))
      (node (ref "IC13") (pin "2") (pinfunction "-IN_2") (pintype "input"))
      (node (ref "R158") (pin "1") (pinfunction "1_1") (pintype "passive"))
      (node (ref "R162") (pin "2") (pinfunction "2_2") (pintype "passive"))
      (node (ref "R166") (pin "1") (pinfunction "1_1") (pintype "passive"))
    )
    (net (code "186") (name "Net-(IC13A-OUT)") (class "Default")
      (node (ref "C110") (pin "1") (pinfunction "1_1") (pintype "passive"))
      (node (ref "IC13") (pin "1") (pinfunction "OUT_1") (pintype "output"))
      (node (ref "R166") (pin "2") (pinfunction "2_2") (pintype "passive"))
      (node (ref "R170") (pin "1") (pinfunction "1_1") (pintype "passive"))
    )
    (net (code "187") (name "Net-(IC13B-+IN)") (class "Default")
      (node (ref "C107") (pin "1") (pinfunction "1_1") (pintype "passive"))
      (node (ref "IC13") (pin "5") (pinfunction "+IN_5") (pintype "input"))
      (node (ref "R155") (pin "2") (pinfunction "2_2") (pintype "passive"))
    )
    (net (code "188") (name "Net-(IC13B--IN)") (class "Default")
      (node (ref "C111") (pin "2") (pinfunction "2_2") (pintype "passive"))
      (node (ref "IC13") (pin "6") (pinfunction "-IN_6") (pintype "input"))
      (node (ref "R159") (pin "1") (pinfunction "1_1") (pintype "passive"))
      (node (ref "R163") (pin "2") (pinfunction "2_2") (pintype "passive"))
      (node (ref "R167") (pin "1") (pinfunction "1_1") (pintype "passive"))
    )
    (net (code "189") (name "Net-(IC13B-OUT)") (class "Default")
      (node (ref "C111") (pin "1") (pinfunction "1_1") (pintype "passive"))
      (node (ref "IC13") (pin "7") (pinfunction "OUT_7") (pintype "output"))
      (node (ref "R167") (pin "2") (pinfunction "2_2") (pintype "passive"))
      (node (ref "R171") (pin "1") (pinfunction "1_1") (pintype "passive"))
    )
    (net (code "190") (name "Net-(IC13C-+IN)") (class "Default")
      (node (ref "C108") (pin "1") (pinfunction "1_1") (pintype "passive"))
      (node (ref "IC13") (pin "10") (pinfunction "+IN_10") (pintype "input"))
      (node (ref "R156") (pin "2") (pinfunction "2_2") (pintype "passive"))
    )
    (net (code "191") (name "Net-(IC13C--IN)") (class "Default")
      (node (ref "C112") (pin "2") (pinfunction "2_2") (pintype "passive"))
      (node (ref "IC13") (pin "9") (pinfunction "-IN_9") (pintype "input"))
      (node (ref "R160") (pin "1") (pinfunction "1_1") (pintype "passive"))
      (node (ref "R164") (pin "2") (pinfunction "2_2") (pintype "passive"))
      (node (ref "R168") (pin "2") (pinfunction "2_2") (pintype "passive"))
    )
    (net (code "192") (name "Net-(IC13C-OUT)") (class "Default")
      (node (ref "C112") (pin "1") (pinfunction "1_1") (pintype "passive"))
      (node (ref "IC13") (pin "8") (pinfunction "OUT_8") (pintype "output"))
      (node (ref "R168") (pin "1") (pinfunction "1_1") (pintype "passive"))
      (node (ref "R172") (pin "1") (pinfunction "1_1") (pintype "passive"))
    )
    (net (code "193") (name "Net-(IC13D-+IN)") (class "Default")
      (node (ref "C109") (pin "1") (pinfunction "1_1") (pintype "passive"))
      (node (ref "IC13") (pin "12") (pinfunction "+IN_12") (pintype "input"))
      (node (ref "R157") (pin "2") (pinfunction "2_2") (pintype "passive"))
    )
    (net (code "194") (name "Net-(IC13D--IN)") (class "Default")
      (node (ref "C113") (pin "2") (pinfunction "2_2") (pintype "passive"))
      (node (ref "IC13") (pin "13") (pinfunction "-IN_13") (pintype "input"))
      (node (ref "R161") (pin "1") (pinfunction "1_1") (pintype "passive"))
      (node (ref "R165") (pin "2") (pinfunction "2_2") (pintype "passive"))
      (node (ref "R169") (pin "2") (pinfunction "2_2") (pintype "passive"))
    )
    (net (code "195") (name "Net-(IC13D-OUT)") (class "Default")
      (node (ref "C113") (pin "1") (pinfunction "1_1") (pintype "passive"))
      (node (ref "IC13") (pin "14") (pinfunction "OUT_14") (pintype "output"))
      (node (ref "R169") (pin "1") (pinfunction "1_1") (pintype "passive"))
      (node (ref "R173") (pin "1") (pinfunction "1_1") (pintype "passive"))
    )
    (net (code "196") (name "Net-(IC13E-V+)") (class "Default")
      (node (ref "C114") (pin "1") (pinfunction "1_1") (pintype "passive"))
      (node (ref "C119") (pin "1") (pinfunction "1_1") (pintype "passive"))
      (node (ref "IC13") (pin "4") (pinfunction "V+_4") (pintype "power_in"))
      (node (ref "L10") (pin "2") (pinfunction "2_2") (pintype "passive"))
    )
    (net (code "197") (name "Net-(IC15A-+IN)") (class "Default")
      (node (ref "C124") (pin "1") (pinfunction "1_1") (pintype "passive"))
      (node (ref "IC15") (pin "3") (pinfunction "+IN_3") (pintype "input"))
      (node (ref "R179") (pin "2") (pinfunction "2_2") (pintype "passive"))
    )
    (net (code "198") (name "Net-(IC15A--IN)") (class "Default")
      (node (ref "C128") (pin "2") (pinfunction "2_2") (pintype "passive"))
      (node (ref "IC15") (pin "2") (pinfunction "-IN_2") (pintype "input"))
      (node (ref "R183") (pin "1") (pinfunction "1_1") (pintype "passive"))
      (node (ref "R187") (pin "2") (pinfunction "2_2") (pintype "passive"))
      (node (ref "R191") (pin "2") (pinfunction "2_2") (pintype "passive"))
    )
    (net (code "199") (name "Net-(IC15A-OUT)") (class "Default")
      (node (ref "C128") (pin "1") (pinfunction "1_1") (pintype "passive"))
      (node (ref "IC15") (pin "1") (pinfunction "OUT_1") (pintype "output"))
      (node (ref "R191") (pin "1") (pinfunction "1_1") (pintype "passive"))
      (node (ref "R195") (pin "1") (pinfunction "1_1") (pintype "passive"))
    )
    (net (code "200") (name "Net-(IC15B-+IN)") (class "Default")
      (node (ref "C125") (pin "1") (pinfunction "1_1") (pintype "passive"))
      (node (ref "IC15") (pin "5") (pinfunction "+IN_5") (pintype "input"))
      (node (ref "R180") (pin "2") (pinfunction "2_2") (pintype "passive"))
    )
    (net (code "201") (name "Net-(IC15B--IN)") (class "Default")
      (node (ref "C129") (pin "2") (pinfunction "2_2") (pintype "passive"))
      (node (ref "IC15") (pin "6") (pinfunction "-IN_6") (pintype "input"))
      (node (ref "R184") (pin "1") (pinfunction "1_1") (pintype "passive"))
      (node (ref "R188") (pin "2") (pinfunction "2_2") (pintype "passive"))
      (node (ref "R192") (pin "2") (pinfunction "2_2") (pintype "passive"))
    )
    (net (code "202") (name "Net-(IC15B-OUT)") (class "Default")
      (node (ref "C129") (pin "1") (pinfunction "1_1") (pintype "passive"))
      (node (ref "IC15") (pin "7") (pinfunction "OUT_7") (pintype "output"))
      (node (ref "R192") (pin "1") (pinfunction "1_1") (pintype "passive"))
      (node (ref "R196") (pin "1") (pinfunction "1_1") (pintype "passive"))
    )
    (net (code "203") (name "Net-(IC15C-+IN)") (class "Default")
      (node (ref "C126") (pin "1") (pinfunction "1_1") (pintype "passive"))
      (node (ref "IC15") (pin "10") (pinfunction "+IN_10") (pintype "input"))
      (node (ref "R181") (pin "2") (pinfunction "2_2") (pintype "passive"))
    )
    (net (code "204") (name "Net-(IC15C--IN)") (class "Default")
      (node (ref "C130") (pin "2") (pinfunction "2_2") (pintype "passive"))
      (node (ref "IC15") (pin "9") (pinfunction "-IN_9") (pintype "input"))
      (node (ref "R185") (pin "1") (pinfunction "1_1") (pintype "passive"))
      (node (ref "R189") (pin "2") (pinfunction "2_2") (pintype "passive"))
      (node (ref "R193") (pin "2") (pinfunction "2_2") (pintype "passive"))
    )
    (net (code "205") (name "Net-(IC15C-OUT)") (class "Default")
      (node (ref "C130") (pin "1") (pinfunction "1_1") (pintype "passive"))
      (node (ref "IC15") (pin "8") (pinfunction "OUT_8") (pintype "output"))
      (node (ref "R193") (pin "1") (pinfunction "1_1") (pintype "passive"))
      (node (ref "R197") (pin "1") (pinfunction "1_1") (pintype "passive"))
    )
    (net (code "206") (name "Net-(IC15D-+IN)") (class "Default")
      (node (ref "C127") (pin "1") (pinfunction "1_1") (pintype "passive"))
      (node (ref "IC15") (pin "12") (pinfunction "+IN_12") (pintype "input"))
      (node (ref "R182") (pin "2") (pinfunction "2_2") (pintype "passive"))
    )
    (net (code "207") (name "Net-(IC15D--IN)") (class "Default")
      (node (ref "C131") (pin "2") (pinfunction "2_2") (pintype "passive"))
      (node (ref "IC15") (pin "13") (pinfunction "-IN_13") (pintype "input"))
      (node (ref "R186") (pin "1") (pinfunction "1_1") (pintype "passive"))
      (node (ref "R190") (pin "2") (pinfunction "2_2") (pintype "passive"))
      (node (ref "R194") (pin "2") (pinfunction "2_2") (pintype "passive"))
    )
    (net (code "208") (name "Net-(IC15D-OUT)") (class "Default")
      (node (ref "C131") (pin "1") (pinfunction "1_1") (pintype "passive"))
      (node (ref "IC15") (pin "14") (pinfunction "OUT_14") (pintype "output"))
      (node (ref "R194") (pin "1") (pinfunction "1_1") (pintype "passive"))
      (node (ref "R198") (pin "1") (pinfunction "1_1") (pintype "passive"))
    )
    (net (code "209") (name "Net-(IC15E-V+)") (class "Default")
      (node (ref "C136") (pin "1") (pinfunction "1_1") (pintype "passive"))
      (node (ref "C137") (pin "1") (pinfunction "1_1") (pintype "passive"))
      (node (ref "IC15") (pin "4") (pinfunction "V+_4") (pintype "power_in"))
      (node (ref "L11") (pin "2") (pinfunction "2_2") (pintype "passive"))
    )
    (net (code "210") (name "Net-(IC16A-+IN)") (class "Default")
      (node (ref "C138") (pin "1") (pinfunction "1_1") (pintype "passive"))
      (node (ref "IC16") (pin "3") (pinfunction "+IN_3") (pintype "input"))
      (node (ref "R203") (pin "2") (pinfunction "2_2") (pintype "passive"))
    )
    (net (code "211") (name "Net-(IC16A--IN)") (class "Default")
      (node (ref "C142") (pin "2") (pinfunction "2_2") (pintype "passive"))
      (node (ref "IC16") (pin "2") (pinfunction "-IN_2") (pintype "input"))
      (node (ref "R207") (pin "1") (pinfunction "1_1") (pintype "passive"))
      (node (ref "R211") (pin "2") (pinfunction "2_2") (pintype "passive"))
      (node (ref "R215") (pin "2") (pinfunction "2_2") (pintype "passive"))
    )
    (net (code "212") (name "Net-(IC16A-OUT)") (class "Default")
      (node (ref "C142") (pin "1") (pinfunction "1_1") (pintype "passive"))
      (node (ref "IC16") (pin "1") (pinfunction "OUT_1") (pintype "output"))
      (node (ref "R215") (pin "1") (pinfunction "1_1") (pintype "passive"))
      (node (ref "R219") (pin "1") (pinfunction "1_1") (pintype "passive"))
    )
    (net (code "213") (name "Net-(IC16B-+IN)") (class "Default")
      (node (ref "C139") (pin "1") (pinfunction "1_1") (pintype "passive"))
      (node (ref "IC16") (pin "5") (pinfunction "+IN_5") (pintype "input"))
      (node (ref "R204") (pin "2") (pinfunction "2_2") (pintype "passive"))
    )
    (net (code "214") (name "Net-(IC16B--IN)") (class "Default")
      (node (ref "C143") (pin "2") (pinfunction "2_2") (pintype "passive"))
      (node (ref "IC16") (pin "6") (pinfunction "-IN_6") (pintype "input"))
      (node (ref "R208") (pin "1") (pinfunction "1_1") (pintype "passive"))
      (node (ref "R212") (pin "2") (pinfunction "2_2") (pintype "passive"))
      (node (ref "R216") (pin "1") (pinfunction "1_1") (pintype "passive"))
    )
    (net (code "215") (name "Net-(IC16B-OUT)") (class "Default")
      (node (ref "C143") (pin "1") (pinfunction "1_1") (pintype "passive"))
      (node (ref "IC16") (pin "7") (pinfunction "OUT_7") (pintype "output"))
      (node (ref "R216") (pin "2") (pinfunction "2_2") (pintype "passive"))
      (node (ref "R220") (pin "1") (pinfunction "1_1") (pintype "passive"))
    )
    (net (code "216") (name "Net-(IC16C-+IN)") (class "Default")
      (node (ref "C140") (pin "1") (pinfunction "1_1") (pintype "passive"))
      (node (ref "IC16") (pin "10") (pinfunction "+IN_10") (pintype "input"))
      (node (ref "R205") (pin "2") (pinfunction "2_2") (pintype "passive"))
    )
    (net (code "217") (name "Net-(IC16C--IN)") (class "Default")
      (node (ref "C144") (pin "2") (pinfunction "2_2") (pintype "passive"))
      (node (ref "IC16") (pin "9") (pinfunction "-IN_9") (pintype "input"))
      (node (ref "R209") (pin "1") (pinfunction "1_1") (pintype "passive"))
      (node (ref "R213") (pin "2") (pinfunction "2_2") (pintype "passive"))
      (node (ref "R217") (pin "1") (pinfunction "1_1") (pintype "passive"))
    )
    (net (code "218") (name "Net-(IC16C-OUT)") (class "Default")
      (node (ref "C144") (pin "1") (pinfunction "1_1") (pintype "passive"))
      (node (ref "IC16") (pin "8") (pinfunction "OUT_8") (pintype "output"))
      (node (ref "R217") (pin "2") (pinfunction "2_2") (pintype "passive"))
      (node (ref "R221") (pin "1") (pinfunction "1_1") (pintype "passive"))
    )
    (net (code "219") (name "Net-(IC16D-+IN)") (class "Default")
      (node (ref "C141") (pin "1") (pinfunction "1_1") (pintype "passive"))
      (node (ref "IC16") (pin "12") (pinfunction "+IN_12") (pintype "input"))
      (node (ref "R206") (pin "2") (pinfunction "2_2") (pintype "passive"))
    )
    (net (code "220") (name "Net-(IC16D--IN)") (class "Default")
      (node (ref "C145") (pin "2") (pinfunction "2_2") (pintype "passive"))
      (node (ref "IC16") (pin "13") (pinfunction "-IN_13") (pintype "input"))
      (node (ref "R210") (pin "1") (pinfunction "1_1") (pintype "passive"))
      (node (ref "R214") (pin "2") (pinfunction "2_2") (pintype "passive"))
      (node (ref "R218") (pin "1") (pinfunction "1_1") (pintype "passive"))
    )
    (net (code "221") (name "Net-(IC16D-OUT)") (class "Default")
      (node (ref "C145") (pin "1") (pinfunction "1_1") (pintype "passive"))
      (node (ref "IC16") (pin "14") (pinfunction "OUT_14") (pintype "output"))
      (node (ref "R218") (pin "2") (pinfunction "2_2") (pintype "passive"))
      (node (ref "R222") (pin "1") (pinfunction "1_1") (pintype "passive"))
    )
    (net (code "222") (name "Net-(IC16E-V+)") (class "Default")
      (node (ref "C146") (pin "1") (pinfunction "1_1") (pintype "passive"))
      (node (ref "C147") (pin "1") (pinfunction "1_1") (pintype "passive"))
      (node (ref "IC16") (pin "4") (pinfunction "V+_4") (pintype "power_in"))
      (node (ref "L12") (pin "2") (pinfunction "2_2") (pintype "passive"))
    )
    (net (code "223") (name "Net-(LED1-PadA)") (class "Default")
      (node (ref "LED1") (pin "A") (pinfunction "A_A") (pintype "passive"))
      (node (ref "R25") (pin "1") (pinfunction "1_1") (pintype "passive"))
    )
    (net (code "224") (name "Net-(LED2-PadA)") (class "Default")
      (node (ref "LED2") (pin "A") (pinfunction "A_A") (pintype "passive"))
      (node (ref "R24") (pin "1") (pinfunction "1_1") (pintype "passive"))
    )
    (net (code "225") (name "Net-(LED3-PadA)") (class "Default")
      (node (ref "LED3") (pin "A") (pinfunction "A_A") (pintype "passive"))
      (node (ref "R34") (pin "2") (pinfunction "2_2") (pintype "passive"))
    )
    (net (code "226") (name "Net-(OK1A-A)") (class "Default")
      (node (ref "OK1") (pin "1") (pinfunction "A_1") (pintype "passive"))
      (node (ref "R40") (pin "1") (pinfunction "1_1") (pintype "passive"))
    )
    (net (code "227") (name "Net-(OK1A-COL)") (class "Default")
      (node (ref "OK1") (pin "16") (pinfunction "COL_16") (pintype "passive"))
      (node (ref "R48") (pin "2") (pinfunction "2_2") (pintype "passive"))
    )
    (net (code "228") (name "Net-(OK1B-A)") (class "Default")
      (node (ref "OK1") (pin "3") (pinfunction "A_3") (pintype "passive"))
      (node (ref "R41") (pin "1") (pinfunction "1_1") (pintype "passive"))
    )
    (net (code "229") (name "Net-(OK1B-COL)") (class "Default")
      (node (ref "OK1") (pin "14") (pinfunction "COL_14") (pintype "passive"))
      (node (ref "R49") (pin "2") (pinfunction "2_2") (pintype "passive"))
    )
    (net (code "230") (name "Net-(OK1C-A)") (class "Default")
      (node (ref "OK1") (pin "5") (pinfunction "A_5") (pintype "passive"))
      (node (ref "R42") (pin "1") (pinfunction "1_1") (pintype "passive"))
    )
    (net (code "231") (name "Net-(OK1C-COL)") (class "Default")
      (node (ref "OK1") (pin "12") (pinfunction "COL_12") (pintype "passive"))
      (node (ref "R50") (pin "2") (pinfunction "2_2") (pintype "passive"))
    )
    (net (code "232") (name "Net-(OK1D-A)") (class "Default")
      (node (ref "OK1") (pin "7") (pinfunction "A_7") (pintype "passive"))
      (node (ref "R43") (pin "1") (pinfunction "1_1") (pintype "passive"))
    )
    (net (code "233") (name "Net-(OK1D-COL)") (class "Default")
      (node (ref "OK1") (pin "10") (pinfunction "COL_10") (pintype "passive"))
      (node (ref "R51") (pin "2") (pinfunction "2_2") (pintype "passive"))
    )
    (net (code "234") (name "Net-(OK2A-A)") (class "Default")
      (node (ref "OK2") (pin "1") (pinfunction "A_1") (pintype "passive"))
      (node (ref "R44") (pin "1") (pinfunction "1_1") (pintype "passive"))
    )
    (net (code "235") (name "Net-(OK2A-COL)") (class "Default")
      (node (ref "OK2") (pin "16") (pinfunction "COL_16") (pintype "passive"))
      (node (ref "R52") (pin "2") (pinfunction "2_2") (pintype "passive"))
    )
    (net (code "236") (name "Net-(OK2B-A)") (class "Default")
      (node (ref "OK2") (pin "3") (pinfunction "A_3") (pintype "passive"))
      (node (ref "R45") (pin "1") (pinfunction "1_1") (pintype "passive"))
    )
    (net (code "237") (name "Net-(OK2B-COL)") (class "Default")
      (node (ref "OK2") (pin "14") (pinfunction "COL_14") (pintype "passive"))
      (node (ref "R53") (pin "2") (pinfunction "2_2") (pintype "passive"))
    )
    (net (code "238") (name "Net-(OK2C-A)") (class "Default")
      (node (ref "OK2") (pin "5") (pinfunction "A_5") (pintype "passive"))
      (node (ref "R46") (pin "1") (pinfunction "1_1") (pintype "passive"))
    )
    (net (code "239") (name "Net-(OK2C-COL)") (class "Default")
      (node (ref "OK2") (pin "12") (pinfunction "COL_12") (pintype "passive"))
      (node (ref "R54") (pin "2") (pinfunction "2_2") (pintype "passive"))
    )
    (net (code "240") (name "Net-(OK2D-A)") (class "Default")
      (node (ref "OK2") (pin "7") (pinfunction "A_7") (pintype "passive"))
      (node (ref "R47") (pin "1") (pinfunction "1_1") (pintype "passive"))
    )
    (net (code "241") (name "Net-(OK2D-COL)") (class "Default")
      (node (ref "OK2") (pin "10") (pinfunction "COL_10") (pintype "passive"))
      (node (ref "R55") (pin "2") (pinfunction "2_2") (pintype "passive"))
    )
    (net (code "242") (name "Net-(OK3A-A)") (class "Default")
      (node (ref "OK3") (pin "1") (pinfunction "A_1") (pintype "passive"))
      (node (ref "R56") (pin "1") (pinfunction "1_1") (pintype "passive"))
    )
    (net (code "243") (name "Net-(OK3A-COL)") (class "Default")
      (node (ref "OK3") (pin "16") (pinfunction "COL_16") (pintype "passive"))
      (node (ref "R64") (pin "2") (pinfunction "2_2") (pintype "passive"))
    )
    (net (code "244") (name "Net-(OK3B-A)") (class "Default")
      (node (ref "OK3") (pin "3") (pinfunction "A_3") (pintype "passive"))
      (node (ref "R57") (pin "1") (pinfunction "1_1") (pintype "passive"))
    )
    (net (code "245") (name "Net-(OK3B-COL)") (class "Default")
      (node (ref "OK3") (pin "14") (pinfunction "COL_14") (pintype "passive"))
      (node (ref "R65") (pin "2") (pinfunction "2_2") (pintype "passive"))
    )
    (net (code "246") (name "Net-(OK3C-A)") (class "Default")
      (node (ref "OK3") (pin "5") (pinfunction "A_5") (pintype "passive"))
      (node (ref "R58") (pin "1") (pinfunction "1_1") (pintype "passive"))
    )
    (net (code "247") (name "Net-(OK3C-COL)") (class "Default")
      (node (ref "OK3") (pin "12") (pinfunction "COL_12") (pintype "passive"))
      (node (ref "R66") (pin "2") (pinfunction "2_2") (pintype "passive"))
    )
    (net (code "248") (name "Net-(OK3D-A)") (class "Default")
      (node (ref "OK3") (pin "7") (pinfunction "A_7") (pintype "passive"))
      (node (ref "R59") (pin "1") (pinfunction "1_1") (pintype "passive"))
    )
    (net (code "249") (name "Net-(OK3D-COL)") (class "Default")
      (node (ref "OK3") (pin "10") (pinfunction "COL_10") (pintype "passive"))
      (node (ref "R67") (pin "2") (pinfunction "2_2") (pintype "passive"))
    )
    (net (code "250") (name "Net-(OK4A-A)") (class "Default")
      (node (ref "OK4") (pin "1") (pinfunction "A_1") (pintype "passive"))
      (node (ref "R60") (pin "1") (pinfunction "1_1") (pintype "passive"))
    )
    (net (code "251") (name "Net-(OK4A-COL)") (class "Default")
      (node (ref "OK4") (pin "16") (pinfunction "COL_16") (pintype "passive"))
      (node (ref "R68") (pin "2") (pinfunction "2_2") (pintype "passive"))
    )
    (net (code "252") (name "Net-(OK4B-A)") (class "Default")
      (node (ref "OK4") (pin "3") (pinfunction "A_3") (pintype "passive"))
      (node (ref "R61") (pin "1") (pinfunction "1_1") (pintype "passive"))
    )
    (net (code "253") (name "Net-(OK4B-COL)") (class "Default")
      (node (ref "OK4") (pin "14") (pinfunction "COL_14") (pintype "passive"))
      (node (ref "R69") (pin "2") (pinfunction "2_2") (pintype "passive"))
    )
    (net (code "254") (name "Net-(OK4C-A)") (class "Default")
      (node (ref "OK4") (pin "5") (pinfunction "A_5") (pintype "passive"))
      (node (ref "R62") (pin "1") (pinfunction "1_1") (pintype "passive"))
    )
    (net (code "255") (name "Net-(OK4C-COL)") (class "Default")
      (node (ref "OK4") (pin "12") (pinfunction "COL_12") (pintype "passive"))
      (node (ref "R70") (pin "2") (pinfunction "2_2") (pintype "passive"))
    )
    (net (code "256") (name "Net-(OK4D-A)") (class "Default")
      (node (ref "OK4") (pin "7") (pinfunction "A_7") (pintype "passive"))
      (node (ref "R63") (pin "1") (pinfunction "1_1") (pintype "passive"))
    )
    (net (code "257") (name "Net-(OK4D-COL)") (class "Default")
      (node (ref "OK4") (pin "10") (pinfunction "COL_10") (pintype "passive"))
      (node (ref "R71") (pin "2") (pinfunction "2_2") (pintype "passive"))
    )
    (net (code "258") (name "Net-(OK5A-A)") (class "Default")
      (node (ref "OK5") (pin "1") (pinfunction "A_1") (pintype "passive"))
      (node (ref "R72") (pin "1") (pinfunction "1_1") (pintype "passive"))
    )
    (net (code "259") (name "Net-(OK5A-COL)") (class "Default")
      (node (ref "OK5") (pin "16") (pinfunction "COL_16") (pintype "passive"))
      (node (ref "R80") (pin "2") (pinfunction "2_2") (pintype "passive"))
    )
    (net (code "260") (name "Net-(OK5B-A)") (class "Default")
      (node (ref "OK5") (pin "3") (pinfunction "A_3") (pintype "passive"))
      (node (ref "R73") (pin "1") (pinfunction "1_1") (pintype "passive"))
    )
    (net (code "261") (name "Net-(OK5B-COL)") (class "Default")
      (node (ref "OK5") (pin "14") (pinfunction "COL_14") (pintype "passive"))
      (node (ref "R81") (pin "2") (pinfunction "2_2") (pintype "passive"))
    )
    (net (code "262") (name "Net-(OK5C-A)") (class "Default")
      (node (ref "OK5") (pin "5") (pinfunction "A_5") (pintype "passive"))
      (node (ref "R74") (pin "1") (pinfunction "1_1") (pintype "passive"))
    )
    (net (code "263") (name "Net-(OK5C-COL)") (class "Default")
      (node (ref "OK5") (pin "12") (pinfunction "COL_12") (pintype "passive"))
      (node (ref "R82") (pin "2") (pinfunction "2_2") (pintype "passive"))
    )
    (net (code "264") (name "Net-(OK5D-A)") (class "Default")
      (node (ref "OK5") (pin "7") (pinfunction "A_7") (pintype "passive"))
      (node (ref "R75") (pin "1") (pinfunction "1_1") (pintype "passive"))
    )
    (net (code "265") (name "Net-(OK5D-COL)") (class "Default")
      (node (ref "OK5") (pin "10") (pinfunction "COL_10") (pintype "passive"))
      (node (ref "R83") (pin "2") (pinfunction "2_2") (pintype "passive"))
    )
    (net (code "266") (name "Net-(OK6A-A)") (class "Default")
      (node (ref "OK6") (pin "1") (pinfunction "A_1") (pintype "passive"))
      (node (ref "R76") (pin "1") (pinfunction "1_1") (pintype "passive"))
    )
    (net (code "267") (name "Net-(OK6A-COL)") (class "Default")
      (node (ref "OK6") (pin "16") (pinfunction "COL_16") (pintype "passive"))
      (node (ref "R84") (pin "2") (pinfunction "2_2") (pintype "passive"))
    )
    (net (code "268") (name "Net-(OK6B-A)") (class "Default")
      (node (ref "OK6") (pin "3") (pinfunction "A_3") (pintype "passive"))
      (node (ref "R77") (pin "1") (pinfunction "1_1") (pintype "passive"))
    )
    (net (code "269") (name "Net-(OK6B-COL)") (class "Default")
      (node (ref "OK6") (pin "14") (pinfunction "COL_14") (pintype "passive"))
      (node (ref "R85") (pin "2") (pinfunction "2_2") (pintype "passive"))
    )
    (net (code "270") (name "Net-(OK6C-A)") (class "Default")
      (node (ref "OK6") (pin "5") (pinfunction "A_5") (pintype "passive"))
      (node (ref "R78") (pin "1") (pinfunction "1_1") (pintype "passive"))
    )
    (net (code "271") (name "Net-(OK6C-COL)") (class "Default")
      (node (ref "OK6") (pin "12") (pinfunction "COL_12") (pintype "passive"))
      (node (ref "R86") (pin "2") (pinfunction "2_2") (pintype "passive"))
    )
    (net (code "272") (name "Net-(OK6D-A)") (class "Default")
      (node (ref "OK6") (pin "7") (pinfunction "A_7") (pintype "passive"))
      (node (ref "R79") (pin "1") (pinfunction "1_1") (pintype "passive"))
    )
    (net (code "273") (name "Net-(OK6D-COL)") (class "Default")
      (node (ref "OK6") (pin "10") (pinfunction "COL_10") (pintype "passive"))
      (node (ref "R87") (pin "2") (pinfunction "2_2") (pintype "passive"))
    )
    (net (code "274") (name "Net-(OK7A-A)") (class "Default")
      (node (ref "D2") (pin "C") (pinfunction "C_C") (pintype "passive"))
      (node (ref "OK7") (pin "1") (pinfunction "A_1") (pintype "passive"))
      (node (ref "R88") (pin "2") (pinfunction "2_2") (pintype "passive"))
    )
    (net (code "275") (name "Net-(OK7A-C)") (class "Default")
      (node (ref "D2") (pin "A") (pinfunction "A_A") (pintype "passive"))
      (node (ref "OK7") (pin "2") (pinfunction "C_2") (pintype "passive"))
      (node (ref "R89") (pin "2") (pinfunction "2_2") (pintype "passive"))
    )
    (net (code "276") (name "Net-(OK7B-A)") (class "Default")
      (node (ref "D3") (pin "C") (pinfunction "C_C") (pintype "passive"))
      (node (ref "OK7") (pin "3") (pinfunction "A_3") (pintype "passive"))
      (node (ref "R90") (pin "2") (pinfunction "2_2") (pintype "passive"))
    )
    (net (code "277") (name "Net-(OK7B-C)") (class "Default")
      (node (ref "D3") (pin "A") (pinfunction "A_A") (pintype "passive"))
      (node (ref "OK7") (pin "4") (pinfunction "C_4") (pintype "passive"))
      (node (ref "R91") (pin "2") (pinfunction "2_2") (pintype "passive"))
    )
    (net (code "278") (name "Net-(OK7C-A)") (class "Default")
      (node (ref "D4") (pin "C") (pinfunction "C_C") (pintype "passive"))
      (node (ref "OK7") (pin "5") (pinfunction "A_5") (pintype "passive"))
      (node (ref "R92") (pin "2") (pinfunction "2_2") (pintype "passive"))
    )
    (net (code "279") (name "Net-(OK7C-C)") (class "Default")
      (node (ref "D4") (pin "A") (pinfunction "A_A") (pintype "passive"))
      (node (ref "OK7") (pin "6") (pinfunction "C_6") (pintype "passive"))
      (node (ref "R93") (pin "2") (pinfunction "2_2") (pintype "passive"))
    )
    (net (code "280") (name "Net-(OK7D-A)") (class "Default")
      (node (ref "D5") (pin "C") (pinfunction "C_C") (pintype "passive"))
      (node (ref "OK7") (pin "7") (pinfunction "A_7") (pintype "passive"))
      (node (ref "R94") (pin "2") (pinfunction "2_2") (pintype "passive"))
    )
    (net (code "281") (name "Net-(OK7D-C)") (class "Default")
      (node (ref "D5") (pin "A") (pinfunction "A_A") (pintype "passive"))
      (node (ref "OK7") (pin "8") (pinfunction "C_8") (pintype "passive"))
      (node (ref "R95") (pin "2") (pinfunction "2_2") (pintype "passive"))
    )
    (net (code "282") (name "Net-(OK8A-A)") (class "Default")
      (node (ref "D6") (pin "C") (pinfunction "C_C") (pintype "passive"))
      (node (ref "OK8") (pin "1") (pinfunction "A_1") (pintype "passive"))
      (node (ref "R100") (pin "2") (pinfunction "2_2") (pintype "passive"))
    )
    (net (code "283") (name "Net-(OK8A-C)") (class "Default")
      (node (ref "D6") (pin "A") (pinfunction "A_A") (pintype "passive"))
      (node (ref "OK8") (pin "2") (pinfunction "C_2") (pintype "passive"))
      (node (ref "R101") (pin "2") (pinfunction "2_2") (pintype "passive"))
    )
    (net (code "284") (name "Net-(OK8B-A)") (class "Default")
      (node (ref "D7") (pin "C") (pinfunction "C_C") (pintype "passive"))
      (node (ref "OK8") (pin "3") (pinfunction "A_3") (pintype "passive"))
      (node (ref "R102") (pin "2") (pinfunction "2_2") (pintype "passive"))
    )
    (net (code "285") (name "Net-(OK8B-C)") (class "Default")
      (node (ref "D7") (pin "A") (pinfunction "A_A") (pintype "passive"))
      (node (ref "OK8") (pin "4") (pinfunction "C_4") (pintype "passive"))
      (node (ref "R103") (pin "2") (pinfunction "2_2") (pintype "passive"))
    )
    (net (code "286") (name "Net-(OK8C-A)") (class "Default")
      (node (ref "D8") (pin "C") (pinfunction "C_C") (pintype "passive"))
      (node (ref "OK8") (pin "5") (pinfunction "A_5") (pintype "passive"))
      (node (ref "R104") (pin "2") (pinfunction "2_2") (pintype "passive"))
    )
    (net (code "287") (name "Net-(OK8C-C)") (class "Default")
      (node (ref "D8") (pin "A") (pinfunction "A_A") (pintype "passive"))
      (node (ref "OK8") (pin "6") (pinfunction "C_6") (pintype "passive"))
      (node (ref "R105") (pin "2") (pinfunction "2_2") (pintype "passive"))
    )
    (net (code "288") (name "Net-(OK8D-A)") (class "Default")
      (node (ref "D9") (pin "C") (pinfunction "C_C") (pintype "passive"))
      (node (ref "OK8") (pin "7") (pinfunction "A_7") (pintype "passive"))
      (node (ref "R106") (pin "2") (pinfunction "2_2") (pintype "passive"))
    )
    (net (code "289") (name "Net-(OK8D-C)") (class "Default")
      (node (ref "D9") (pin "A") (pinfunction "A_A") (pintype "passive"))
      (node (ref "OK8") (pin "8") (pinfunction "C_8") (pintype "passive"))
      (node (ref "R107") (pin "2") (pinfunction "2_2") (pintype "passive"))
    )
    (net (code "290") (name "Net-(OK9A-A)") (class "Default")
      (node (ref "D10") (pin "C") (pinfunction "C_C") (pintype "passive"))
      (node (ref "OK9") (pin "1") (pinfunction "A_1") (pintype "passive"))
      (node (ref "R112") (pin "2") (pinfunction "2_2") (pintype "passive"))
    )
    (net (code "291") (name "Net-(OK9A-C)") (class "Default")
      (node (ref "D10") (pin "A") (pinfunction "A_A") (pintype "passive"))
      (node (ref "OK9") (pin "2") (pinfunction "C_2") (pintype "passive"))
      (node (ref "R113") (pin "2") (pinfunction "2_2") (pintype "passive"))
    )
    (net (code "292") (name "Net-(OK9B-A)") (class "Default")
      (node (ref "D11") (pin "C") (pinfunction "C_C") (pintype "passive"))
      (node (ref "OK9") (pin "3") (pinfunction "A_3") (pintype "passive"))
      (node (ref "R114") (pin "2") (pinfunction "2_2") (pintype "passive"))
    )
    (net (code "293") (name "Net-(OK9B-C)") (class "Default")
      (node (ref "D11") (pin "A") (pinfunction "A_A") (pintype "passive"))
      (node (ref "OK9") (pin "4") (pinfunction "C_4") (pintype "passive"))
      (node (ref "R115") (pin "2") (pinfunction "2_2") (pintype "passive"))
    )
    (net (code "294") (name "Net-(OK9C-A)") (class "Default")
      (node (ref "D12") (pin "C") (pinfunction "C_C") (pintype "passive"))
      (node (ref "OK9") (pin "5") (pinfunction "A_5") (pintype "passive"))
      (node (ref "R116") (pin "2") (pinfunction "2_2") (pintype "passive"))
    )
    (net (code "295") (name "Net-(OK9C-C)") (class "Default")
      (node (ref "D12") (pin "A") (pinfunction "A_A") (pintype "passive"))
      (node (ref "OK9") (pin "6") (pinfunction "C_6") (pintype "passive"))
      (node (ref "R117") (pin "2") (pinfunction "2_2") (pintype "passive"))
    )
    (net (code "296") (name "Net-(OK9D-A)") (class "Default")
      (node (ref "D13") (pin "C") (pinfunction "C_C") (pintype "passive"))
      (node (ref "OK9") (pin "7") (pinfunction "A_7") (pintype "passive"))
      (node (ref "R118") (pin "2") (pinfunction "2_2") (pintype "passive"))
    )
    (net (code "297") (name "Net-(OK9D-C)") (class "Default")
      (node (ref "D13") (pin "A") (pinfunction "A_A") (pintype "passive"))
      (node (ref "OK9") (pin "8") (pinfunction "C_8") (pintype "passive"))
      (node (ref "R119") (pin "2") (pinfunction "2_2") (pintype "passive"))
    )
    (net (code "298") (name "Net-(OK10A-A)") (class "Default")
      (node (ref "D14") (pin "C") (pinfunction "C_C") (pintype "passive"))
      (node (ref "OK10") (pin "1") (pinfunction "A_1") (pintype "passive"))
      (node (ref "R124") (pin "2") (pinfunction "2_2") (pintype "passive"))
    )
    (net (code "299") (name "Net-(OK10A-C)") (class "Default")
      (node (ref "D14") (pin "A") (pinfunction "A_A") (pintype "passive"))
      (node (ref "OK10") (pin "2") (pinfunction "C_2") (pintype "passive"))
      (node (ref "R125") (pin "2") (pinfunction "2_2") (pintype "passive"))
    )
    (net (code "300") (name "Net-(OK10B-A)") (class "Default")
      (node (ref "D15") (pin "C") (pinfunction "C_C") (pintype "passive"))
      (node (ref "OK10") (pin "3") (pinfunction "A_3") (pintype "passive"))
      (node (ref "R126") (pin "2") (pinfunction "2_2") (pintype "passive"))
    )
    (net (code "301") (name "Net-(OK10B-C)") (class "Default")
      (node (ref "D15") (pin "A") (pinfunction "A_A") (pintype "passive"))
      (node (ref "OK10") (pin "4") (pinfunction "C_4") (pintype "passive"))
      (node (ref "R127") (pin "2") (pinfunction "2_2") (pintype "passive"))
    )
    (net (code "302") (name "Net-(OK10C-A)") (class "Default")
      (node (ref "D16") (pin "C") (pinfunction "C_C") (pintype "passive"))
      (node (ref "OK10") (pin "5") (pinfunction "A_5") (pintype "passive"))
      (node (ref "R128") (pin "2") (pinfunction "2_2") (pintype "passive"))
    )
    (net (code "303") (name "Net-(OK10C-C)") (class "Default")
      (node (ref "D16") (pin "A") (pinfunction "A_A") (pintype "passive"))
      (node (ref "OK10") (pin "6") (pinfunction "C_6") (pintype "passive"))
      (node (ref "R129") (pin "2") (pinfunction "2_2") (pintype "passive"))
    )
    (net (code "304") (name "Net-(OK10D-A)") (class "Default")
      (node (ref "D17") (pin "C") (pinfunction "C_C") (pintype "passive"))
      (node (ref "OK10") (pin "7") (pinfunction "A_7") (pintype "passive"))
      (node (ref "R130") (pin "2") (pinfunction "2_2") (pintype "passive"))
    )
    (net (code "305") (name "Net-(OK10D-C)") (class "Default")
      (node (ref "D17") (pin "A") (pinfunction "A_A") (pintype "passive"))
      (node (ref "OK10") (pin "8") (pinfunction "C_8") (pintype "passive"))
      (node (ref "R131") (pin "2") (pinfunction "2_2") (pintype "passive"))
    )
    (net (code "306") (name "Net-(OK11A-A)") (class "Default")
      (node (ref "D18") (pin "C") (pinfunction "C_C") (pintype "passive"))
      (node (ref "OK11") (pin "1") (pinfunction "A_1") (pintype "passive"))
      (node (ref "R136") (pin "2") (pinfunction "2_2") (pintype "passive"))
    )
    (net (code "307") (name "Net-(OK11A-C)") (class "Default")
      (node (ref "D18") (pin "A") (pinfunction "A_A") (pintype "passive"))
      (node (ref "OK11") (pin "2") (pinfunction "C_2") (pintype "passive"))
      (node (ref "R137") (pin "2") (pinfunction "2_2") (pintype "passive"))
    )
    (net (code "308") (name "Net-(OK11B-A)") (class "Default")
      (node (ref "D19") (pin "C") (pinfunction "C_C") (pintype "passive"))
      (node (ref "OK11") (pin "3") (pinfunction "A_3") (pintype "passive"))
      (node (ref "R138") (pin "2") (pinfunction "2_2") (pintype "passive"))
    )
    (net (code "309") (name "Net-(OK11B-C)") (class "Default")
      (node (ref "D19") (pin "A") (pinfunction "A_A") (pintype "passive"))
      (node (ref "OK11") (pin "4") (pinfunction "C_4") (pintype "passive"))
      (node (ref "R139") (pin "2") (pinfunction "2_2") (pintype "passive"))
    )
    (net (code "310") (name "Net-(OK11C-A)") (class "Default")
      (node (ref "D20") (pin "C") (pinfunction "C_C") (pintype "passive"))
      (node (ref "OK11") (pin "5") (pinfunction "A_5") (pintype "passive"))
      (node (ref "R140") (pin "2") (pinfunction "2_2") (pintype "passive"))
    )
    (net (code "311") (name "Net-(OK11C-C)") (class "Default")
      (node (ref "D20") (pin "A") (pinfunction "A_A") (pintype "passive"))
      (node (ref "OK11") (pin "6") (pinfunction "C_6") (pintype "passive"))
      (node (ref "R141") (pin "2") (pinfunction "2_2") (pintype "passive"))
    )
    (net (code "312") (name "Net-(OK11D-A)") (class "Default")
      (node (ref "D21") (pin "C") (pinfunction "C_C") (pintype "passive"))
      (node (ref "OK11") (pin "7") (pinfunction "A_7") (pintype "passive"))
      (node (ref "R142") (pin "2") (pinfunction "2_2") (pintype "passive"))
    )
    (net (code "313") (name "Net-(OK11D-C)") (class "Default")
      (node (ref "D21") (pin "A") (pinfunction "A_A") (pintype "passive"))
      (node (ref "OK11") (pin "8") (pinfunction "C_8") (pintype "passive"))
      (node (ref "R143") (pin "2") (pinfunction "2_2") (pintype "passive"))
    )
    (net (code "314") (name "Net-(R1-Pad2)") (class "Default")
      (node (ref "R1") (pin "2") (pinfunction "2_2") (pintype "passive"))
      (node (ref "X1") (pin "G2") (pinfunction "G2_G2") (pintype "passive"))
    )
    (net (code "315") (name "Net-(R2-Pad1)") (class "Default")
      (node (ref "R2") (pin "1") (pinfunction "1_1") (pintype "passive"))
      (node (ref "X1") (pin "2") (pinfunction "2_2") (pintype "passive"))
    )
    (net (code "316") (name "Net-(R5-Pad1)") (class "Default")
      (node (ref "R5") (pin "1") (pinfunction "1_1") (pintype "passive"))
      (node (ref "X1") (pin "3") (pinfunction "3_3") (pintype "passive"))
    )
    (net (code "317") (name "Net-(R88-Pad1)") (class "Default")
      (node (ref "R88") (pin "1") (pinfunction "1_1") (pintype "passive"))
      (node (ref "X2") (pin "1@1") (pinfunction "1_1@1") (pintype "passive"))
      (node (ref "X2") (pin "2@1") (pinfunction "1_2@1") (pintype "passive"))
    )
    (net (code "318") (name "Net-(R89-Pad1)") (class "Default")
      (node (ref "R89") (pin "1") (pinfunction "1_1") (pintype "passive"))
      (node (ref "X3") (pin "1@1") (pinfunction "1_1@1") (pintype "passive"))
      (node (ref "X3") (pin "2@1") (pinfunction "1_2@1") (pintype "passive"))
    )
    (net (code "319") (name "Net-(R90-Pad1)") (class "Default")
      (node (ref "R90") (pin "1") (pinfunction "1_1") (pintype "passive"))
      (node (ref "X4") (pin "1@1") (pinfunction "1_1@1") (pintype "passive"))
      (node (ref "X4") (pin "2@1") (pinfunction "1_2@1") (pintype "passive"))
    )
    (net (code "320") (name "Net-(R91-Pad1)") (class "Default")
      (node (ref "R91") (pin "1") (pinfunction "1_1") (pintype "passive"))
      (node (ref "X5") (pin "1@1") (pinfunction "1_1@1") (pintype "passive"))
      (node (ref "X5") (pin "2@1") (pinfunction "1_2@1") (pintype "passive"))
    )
    (net (code "321") (name "Net-(R92-Pad1)") (class "Default")
      (node (ref "R92") (pin "1") (pinfunction "1_1") (pintype "passive"))
      (node (ref "X6") (pin "1@1") (pinfunction "1_1@1") (pintype "passive"))
      (node (ref "X6") (pin "2@1") (pinfunction "1_2@1") (pintype "passive"))
    )
    (net (code "322") (name "Net-(R93-Pad1)") (class "Default")
      (node (ref "R93") (pin "1") (pinfunction "1_1") (pintype "passive"))
      (node (ref "X7") (pin "1@1") (pinfunction "1_1@1") (pintype "passive"))
      (node (ref "X7") (pin "2@1") (pinfunction "1_2@1") (pintype "passive"))
    )
    (net (code "323") (name "Net-(R94-Pad1)") (class "Default")
      (node (ref "R94") (pin "1") (pinfunction "1_1") (pintype "passive"))
      (node (ref "X8") (pin "1@1") (pinfunction "1_1@1") (pintype "passive"))
      (node (ref "X8") (pin "2@1") (pinfunction "1_2@1") (pintype "passive"))
    )
    (net (code "324") (name "Net-(R95-Pad1)") (class "Default")
      (node (ref "R95") (pin "1") (pinfunction "1_1") (pintype "passive"))
      (node (ref "X9") (pin "1@1") (pinfunction "1_1@1") (pintype "passive"))
      (node (ref "X9") (pin "2@1") (pinfunction "1_2@1") (pintype "passive"))
    )
    (net (code "325") (name "Net-(R100-Pad1)") (class "Default")
      (node (ref "R100") (pin "1") (pinfunction "1_1") (pintype "passive"))
      (node (ref "X10") (pin "1@1") (pinfunction "1_1@1") (pintype "passive"))
      (node (ref "X10") (pin "2@1") (pinfunction "1_2@1") (pintype "passive"))
    )
    (net (code "326") (name "Net-(R101-Pad1)") (class "Default")
      (node (ref "R101") (pin "1") (pinfunction "1_1") (pintype "passive"))
      (node (ref "X11") (pin "1@1") (pinfunction "1_1@1") (pintype "passive"))
      (node (ref "X11") (pin "2@1") (pinfunction "1_2@1") (pintype "passive"))
    )
    (net (code "327") (name "Net-(R102-Pad1)") (class "Default")
      (node (ref "R102") (pin "1") (pinfunction "1_1") (pintype "passive"))
      (node (ref "X12") (pin "1@1") (pinfunction "1_1@1") (pintype "passive"))
      (node (ref "X12") (pin "2@1") (pinfunction "1_2@1") (pintype "passive"))
    )
    (net (code "328") (name "Net-(R103-Pad1)") (class "Default")
      (node (ref "R103") (pin "1") (pinfunction "1_1") (pintype "passive"))
      (node (ref "X13") (pin "1@1") (pinfunction "1_1@1") (pintype "passive"))
      (node (ref "X13") (pin "2@1") (pinfunction "1_2@1") (pintype "passive"))
    )
    (net (code "329") (name "Net-(R104-Pad1)") (class "Default")
      (node (ref "R104") (pin "1") (pinfunction "1_1") (pintype "passive"))
      (node (ref "X14") (pin "1@1") (pinfunction "1_1@1") (pintype "passive"))
      (node (ref "X14") (pin "2@1") (pinfunction "1_2@1") (pintype "passive"))
    )
    (net (code "330") (name "Net-(R105-Pad1)") (class "Default")
      (node (ref "R105") (pin "1") (pinfunction "1_1") (pintype "passive"))
      (node (ref "X15") (pin "1@1") (pinfunction "1_1@1") (pintype "passive"))
      (node (ref "X15") (pin "2@1") (pinfunction "1_2@1") (pintype "passive"))
    )
    (net (code "331") (name "Net-(R106-Pad1)") (class "Default")
      (node (ref "R106") (pin "1") (pinfunction "1_1") (pintype "passive"))
      (node (ref "X16") (pin "1@1") (pinfunction "1_1@1") (pintype "passive"))
      (node (ref "X16") (pin "2@1") (pinfunction "1_2@1") (pintype "passive"))
    )
    (net (code "332") (name "Net-(R107-Pad1)") (class "Default")
      (node (ref "R107") (pin "1") (pinfunction "1_1") (pintype "passive"))
      (node (ref "X17") (pin "1@1") (pinfunction "1_1@1") (pintype "passive"))
      (node (ref "X17") (pin "2@1") (pinfunction "1_2@1") (pintype "passive"))
    )
    (net (code "333") (name "Net-(R112-Pad1)") (class "Default")
      (node (ref "R112") (pin "1") (pinfunction "1_1") (pintype "passive"))
      (node (ref "X18") (pin "1@1") (pinfunction "1_1@1") (pintype "passive"))
      (node (ref "X18") (pin "2@1") (pinfunction "1_2@1") (pintype "passive"))
    )
    (net (code "334") (name "Net-(R113-Pad1)") (class "Default")
      (node (ref "R113") (pin "1") (pinfunction "1_1") (pintype "passive"))
      (node (ref "X19") (pin "1@1") (pinfunction "1_1@1") (pintype "passive"))
      (node (ref "X19") (pin "2@1") (pinfunction "1_2@1") (pintype "passive"))
    )
    (net (code "335") (name "Net-(R114-Pad1)") (class "Default")
      (node (ref "R114") (pin "1") (pinfunction "1_1") (pintype "passive"))
      (node (ref "X20") (pin "1@1") (pinfunction "1_1@1") (pintype "passive"))
      (node (ref "X20") (pin "2@1") (pinfunction "1_2@1") (pintype "passive"))
    )
    (net (code "336") (name "Net-(R115-Pad1)") (class "Default")
      (node (ref "R115") (pin "1") (pinfunction "1_1") (pintype "passive"))
      (node (ref "X21") (pin "1@1") (pinfunction "1_1@1") (pintype "passive"))
      (node (ref "X21") (pin "2@1") (pinfunction "1_2@1") (pintype "passive"))
    )
    (net (code "337") (name "Net-(R116-Pad1)") (class "Default")
      (node (ref "R116") (pin "1") (pinfunction "1_1") (pintype "passive"))
      (node (ref "X22") (pin "1@1") (pinfunction "1_1@1") (pintype "passive"))
      (node (ref "X22") (pin "2@1") (pinfunction "1_2@1") (pintype "passive"))
    )
    (net (code "338") (name "Net-(R117-Pad1)") (class "Default")
      (node (ref "R117") (pin "1") (pinfunction "1_1") (pintype "passive"))
      (node (ref "X23") (pin "1@1") (pinfunction "1_1@1") (pintype "passive"))
      (node (ref "X23") (pin "2@1") (pinfunction "1_2@1") (pintype "passive"))
    )
    (net (code "339") (name "Net-(R118-Pad1)") (class "Default")
      (node (ref "R118") (pin "1") (pinfunction "1_1") (pintype "passive"))
      (node (ref "X24") (pin "1@1") (pinfunction "1_1@1") (pintype "passive"))
      (node (ref "X24") (pin "2@1") (pinfunction "1_2@1") (pintype "passive"))
    )
    (net (code "340") (name "Net-(R119-Pad1)") (class "Default")
      (node (ref "R119") (pin "1") (pinfunction "1_1") (pintype "passive"))
      (node (ref "X25") (pin "1@1") (pinfunction "1_1@1") (pintype "passive"))
      (node (ref "X25") (pin "2@1") (pinfunction "1_2@1") (pintype "passive"))
    )
    (net (code "341") (name "Net-(R124-Pad1)") (class "Default")
      (node (ref "R124") (pin "1") (pinfunction "1_1") (pintype "passive"))
      (node (ref "X26") (pin "1@1") (pinfunction "1_1@1") (pintype "passive"))
      (node (ref "X26") (pin "2@1") (pinfunction "1_2@1") (pintype "passive"))
    )
    (net (code "342") (name "Net-(R125-Pad1)") (class "Default")
      (node (ref "R125") (pin "1") (pinfunction "1_1") (pintype "passive"))
      (node (ref "X27") (pin "1@1") (pinfunction "1_1@1") (pintype "passive"))
      (node (ref "X27") (pin "2@1") (pinfunction "1_2@1") (pintype "passive"))
    )
    (net (code "343") (name "Net-(R126-Pad1)") (class "Default")
      (node (ref "R126") (pin "1") (pinfunction "1_1") (pintype "passive"))
      (node (ref "X28") (pin "1@1") (pinfunction "1_1@1") (pintype "passive"))
      (node (ref "X28") (pin "2@1") (pinfunction "1_2@1") (pintype "passive"))
    )
    (net (code "344") (name "Net-(R127-Pad1)") (class "Default")
      (node (ref "R127") (pin "1") (pinfunction "1_1") (pintype "passive"))
      (node (ref "X29") (pin "1@1") (pinfunction "1_1@1") (pintype "passive"))
      (node (ref "X29") (pin "2@1") (pinfunction "1_2@1") (pintype "passive"))
    )
    (net (code "345") (name "Net-(R128-Pad1)") (class "Default")
      (node (ref "R128") (pin "1") (pinfunction "1_1") (pintype "passive"))
      (node (ref "X30") (pin "1@1") (pinfunction "1_1@1") (pintype "passive"))
      (node (ref "X30") (pin "2@1") (pinfunction "1_2@1") (pintype "passive"))
    )
    (net (code "346") (name "Net-(R129-Pad1)") (class "Default")
      (node (ref "R129") (pin "1") (pinfunction "1_1") (pintype "passive"))
      (node (ref "X31") (pin "1@1") (pinfunction "1_1@1") (pintype "passive"))
      (node (ref "X31") (pin "2@1") (pinfunction "1_2@1") (pintype "passive"))
    )
    (net (code "347") (name "Net-(R130-Pad1)") (class "Default")
      (node (ref "R130") (pin "1") (pinfunction "1_1") (pintype "passive"))
      (node (ref "X32") (pin "1@1") (pinfunction "1_1@1") (pintype "passive"))
      (node (ref "X32") (pin "2@1") (pinfunction "1_2@1") (pintype "passive"))
    )
    (net (code "348") (name "Net-(R131-Pad1)") (class "Default")
      (node (ref "R131") (pin "1") (pinfunction "1_1") (pintype "passive"))
      (node (ref "X33") (pin "1@1") (pinfunction "1_1@1") (pintype "passive"))
      (node (ref "X33") (pin "2@1") (pinfunction "1_2@1") (pintype "passive"))
    )
    (net (code "349") (name "Net-(R136-Pad1)") (class "Default")
      (node (ref "R136") (pin "1") (pinfunction "1_1") (pintype "passive"))
      (node (ref "X34") (pin "1@1") (pinfunction "1_1@1") (pintype "passive"))
      (node (ref "X34") (pin "2@1") (pinfunction "1_2@1") (pintype "passive"))
    )
    (net (code "350") (name "Net-(R137-Pad1)") (class "Default")
      (node (ref "R137") (pin "1") (pinfunction "1_1") (pintype "passive"))
      (node (ref "X35") (pin "1@1") (pinfunction "1_1@1") (pintype "passive"))
      (node (ref "X35") (pin "2@1") (pinfunction "1_2@1") (pintype "passive"))
    )
    (net (code "351") (name "Net-(R138-Pad1)") (class "Default")
      (node (ref "R138") (pin "1") (pinfunction "1_1") (pintype "passive"))
      (node (ref "X36") (pin "1@1") (pinfunction "1_1@1") (pintype "passive"))
      (node (ref "X36") (pin "2@1") (pinfunction "1_2@1") (pintype "passive"))
    )
    (net (code "352") (name "Net-(R139-Pad1)") (class "Default")
      (node (ref "R139") (pin "1") (pinfunction "1_1") (pintype "passive"))
      (node (ref "X37") (pin "1@1") (pinfunction "1_1@1") (pintype "passive"))
      (node (ref "X37") (pin "2@1") (pinfunction "1_2@1") (pintype "passive"))
    )
    (net (code "353") (name "Net-(R140-Pad1)") (class "Default")
      (node (ref "R140") (pin "1") (pinfunction "1_1") (pintype "passive"))
      (node (ref "X38") (pin "1@1") (pinfunction "1_1@1") (pintype "passive"))
      (node (ref "X38") (pin "2@1") (pinfunction "1_2@1") (pintype "passive"))
    )
    (net (code "354") (name "Net-(R141-Pad1)") (class "Default")
      (node (ref "R141") (pin "1") (pinfunction "1_1") (pintype "passive"))
      (node (ref "X39") (pin "1@1") (pinfunction "1_1@1") (pintype "passive"))
      (node (ref "X39") (pin "2@1") (pinfunction "1_2@1") (pintype "passive"))
    )
    (net (code "355") (name "Net-(R142-Pad1)") (class "Default")
      (node (ref "R142") (pin "1") (pinfunction "1_1") (pintype "passive"))
      (node (ref "X40") (pin "1@1") (pinfunction "1_1@1") (pintype "passive"))
      (node (ref "X40") (pin "2@1") (pinfunction "1_2@1") (pintype "passive"))
    )
    (net (code "356") (name "Net-(R143-Pad1)") (class "Default")
      (node (ref "R143") (pin "1") (pinfunction "1_1") (pintype "passive"))
      (node (ref "X41") (pin "1@1") (pinfunction "1_1@1") (pintype "passive"))
      (node (ref "X41") (pin "2@1") (pinfunction "1_2@1") (pintype "passive"))
    )
    (net (code "357") (name "Net-(U1-VCC)") (class "Default")
      (node (ref "C20") (pin "1") (pinfunction "1_1") (pintype "passive"))
      (node (ref "C22") (pin "1") (pinfunction "1_1") (pintype "passive"))
      (node (ref "L5") (pin "2") (pinfunction "2_2") (pintype "passive"))
      (node (ref "U1") (pin "1") (pinfunction "VCC_1") (pintype "power_in"))
    )
    (net (code "358") (name "Net-(U1-~{RST})") (class "Default")
      (node (ref "R23") (pin "1") (pinfunction "1_1") (pintype "passive"))
      (node (ref "U1") (pin "3") (pinfunction "~{RST}_3") (pintype "input"))
    )
    (net (code "359") (name "Net-(X1-Pad8)") (class "Default")
      (node (ref "X1") (pin "8") (pinfunction "8_8") (pintype "passive"))
      (node (ref "XT1") (pin "1@1") (pinfunction "1_1@1") (pintype "passive"))
      (node (ref "XT1") (pin "1@2") (pinfunction "1_1@2") (pintype "passive"))
    )
    (net (code "361") (name "PMODE0") (class "Default")
      (node (ref "IC3") (pin "45") (pinfunction "PMODE0_45") (pintype "input"))
      (node (ref "R26") (pin "1") (pinfunction "1_1") (pintype "passive"))
    )
    (net (code "362") (name "PMODE1") (class "Default")
      (node (ref "IC3") (pin "44") (pinfunction "PMODE1_44") (pintype "input"))
      (node (ref "R28") (pin "1") (pinfunction "1_1") (pintype "passive"))
    )
    (net (code "363") (name "PMODE2") (class "Default")
      (node (ref "IC3") (pin "43") (pinfunction "PMODE2_43") (pintype "input"))
      (node (ref "R30") (pin "1") (pinfunction "1_1") (pintype "passive"))
    )
    (net (code "364") (name "RELAY_DRV_OUT_1") (class "Default")
      (node (ref "CON4") (pin "A2") (pinfunction "A2_A2") (pintype "passive"))
      (node (ref "IC6") (pin "18") (pinfunction "O1_18") (pintype "open_collector"))
    )
    (net (code "365") (name "RELAY_DRV_OUT_2") (class "Default")
      (node (ref "CON4") (pin "B2") (pinfunction "B2_B2") (pintype "passive"))
      (node (ref "IC6") (pin "17") (pinfunction "O2_17") (pintype "open_collector"))
    )
    (net (code "366") (name "RELAY_DRV_OUT_3") (class "Default")
      (node (ref "CON4") (pin "A3") (pinfunction "A3_A3") (pintype "passive"))
      (node (ref "IC6") (pin "16") (pinfunction "O3_16") (pintype "open_collector"))
    )
    (net (code "367") (name "RELAY_DRV_OUT_4") (class "Default")
      (node (ref "CON4") (pin "B3") (pinfunction "B3_B3") (pintype "passive"))
      (node (ref "IC6") (pin "15") (pinfunction "O4_15") (pintype "open_collector"))
    )
    (net (code "368") (name "RELAY_DRV_OUT_5") (class "Default")
      (node (ref "CON4") (pin "A4") (pinfunction "A4_A4") (pintype "passive"))
      (node (ref "IC6") (pin "14") (pinfunction "O5_14") (pintype "open_collector"))
    )
    (net (code "369") (name "RELAY_DRV_OUT_6") (class "Default")
      (node (ref "CON4") (pin "B4") (pinfunction "B4_B4") (pintype "passive"))
      (node (ref "IC6") (pin "13") (pinfunction "O6_13") (pintype "open_collector"))
    )
    (net (code "370") (name "RELAY_DRV_OUT_7") (class "Default")
      (node (ref "CON4") (pin "A5") (pinfunction "A5_A5") (pintype "passive"))
      (node (ref "IC6") (pin "12") (pinfunction "O7_12") (pintype "open_collector"))
    )
    (net (code "371") (name "RELAY_DRV_OUT_8") (class "Default")
      (node (ref "CON4") (pin "B5") (pinfunction "B5_B5") (pintype "passive"))
      (node (ref "IC6") (pin "11") (pinfunction "O8_11") (pintype "open_collector"))
    )
    (net (code "372") (name "RELAY_DRV_OUT_9") (class "Default")
      (node (ref "CON4") (pin "A6") (pinfunction "A6_A6") (pintype "passive"))
      (node (ref "IC7") (pin "18") (pinfunction "O1_18") (pintype "open_collector"))
    )
    (net (code "373") (name "RELAY_DRV_OUT_10") (class "Default")
      (node (ref "CON4") (pin "B6") (pinfunction "B6_B6") (pintype "passive"))
      (node (ref "IC7") (pin "17") (pinfunction "O2_17") (pintype "open_collector"))
    )
    (net (code "374") (name "RELAY_DRV_OUT_11") (class "Default")
      (node (ref "CON4") (pin "A7") (pinfunction "A7_A7") (pintype "passive"))
      (node (ref "IC7") (pin "16") (pinfunction "O3_16") (pintype "open_collector"))
    )
    (net (code "375") (name "RELAY_DRV_OUT_12") (class "Default")
      (node (ref "CON4") (pin "B7") (pinfunction "B7_B7") (pintype "passive"))
      (node (ref "IC7") (pin "15") (pinfunction "O4_15") (pintype "open_collector"))
    )
    (net (code "376") (name "RELAY_DRV_OUT_13") (class "Default")
      (node (ref "CON4") (pin "A8") (pinfunction "A8_A8") (pintype "passive"))
      (node (ref "IC7") (pin "14") (pinfunction "O5_14") (pintype "open_collector"))
    )
    (net (code "377") (name "RELAY_DRV_OUT_14") (class "Default")
      (node (ref "CON4") (pin "B8") (pinfunction "B8_B8") (pintype "passive"))
      (node (ref "IC7") (pin "13") (pinfunction "O6_13") (pintype "open_collector"))
    )
    (net (code "378") (name "RELAY_DRV_OUT_15") (class "Default")
      (node (ref "CON4") (pin "A9") (pinfunction "A9_A9") (pintype "passive"))
      (node (ref "IC7") (pin "12") (pinfunction "O7_12") (pintype "open_collector"))
    )
    (net (code "379") (name "RELAY_DRV_OUT_16") (class "Default")
      (node (ref "CON4") (pin "B9") (pinfunction "B9_B9") (pintype "passive"))
      (node (ref "IC7") (pin "11") (pinfunction "O8_11") (pintype "open_collector"))
    )
    (net (code "380") (name "RELAY_DRV_OUT_17") (class "Default")
      (node (ref "CON4") (pin "A10") (pinfunction "A10_A10") (pintype "passive"))
      (node (ref "IC8") (pin "18") (pinfunction "O1_18") (pintype "open_collector"))
    )
    (net (code "381") (name "RELAY_DRV_OUT_18") (class "Default")
      (node (ref "CON4") (pin "B10") (pinfunction "B10_B10") (pintype "passive"))
      (node (ref "IC8") (pin "17") (pinfunction "O2_17") (pintype "open_collector"))
    )
    (net (code "382") (name "RELAY_DRV_OUT_19") (class "Default")
      (node (ref "CON4") (pin "A11") (pinfunction "A11_A11") (pintype "passive"))
      (node (ref "IC8") (pin "16") (pinfunction "O3_16") (pintype "open_collector"))
    )
    (net (code "383") (name "RELAY_DRV_OUT_20") (class "Default")
      (node (ref "CON4") (pin "B11") (pinfunction "B11_B11") (pintype "passive"))
      (node (ref "IC8") (pin "15") (pinfunction "O4_15") (pintype "open_collector"))
    )
    (net (code "384") (name "RELAY_DRV_OUT_21") (class "Default")
      (node (ref "CON4") (pin "A12") (pinfunction "A12_A12") (pintype "passive"))
      (node (ref "IC8") (pin "14") (pinfunction "O5_14") (pintype "open_collector"))
    )
    (net (code "385") (name "RELAY_DRV_OUT_22") (class "Default")
      (node (ref "CON4") (pin "B12") (pinfunction "B12_B12") (pintype "passive"))
      (node (ref "IC8") (pin "13") (pinfunction "O6_13") (pintype "open_collector"))
    )
    (net (code "386") (name "RELAY_DRV_OUT_23") (class "Default")
      (node (ref "CON4") (pin "A13") (pinfunction "A13_A13") (pintype "passive"))
      (node (ref "IC8") (pin "12") (pinfunction "O7_12") (pintype "open_collector"))
    )
    (net (code "387") (name "RELAY_DRV_OUT_24") (class "Default")
      (node (ref "CON4") (pin "B13") (pinfunction "B13_B13") (pintype "passive"))
      (node (ref "IC8") (pin "11") (pinfunction "O8_11") (pintype "open_collector"))
    )
    (net (code "388") (name "RSVD1") (class "Default")
      (node (ref "IC3") (pin "38") (pinfunction "RSVD_38") (pintype "input"))
      (node (ref "R27") (pin "2") (pinfunction "2_2") (pintype "passive"))
    )
    (net (code "389") (name "RSVD2") (class "Default")
      (node (ref "IC3") (pin "39") (pinfunction "RSVD_39") (pintype "input"))
      (node (ref "R29") (pin "2") (pinfunction "2_2") (pintype "passive"))
    )
    (net (code "390") (name "RSVD3") (class "Default")
      (node (ref "IC3") (pin "40") (pinfunction "RSVD_40") (pintype "input"))
      (node (ref "R31") (pin "2") (pinfunction "2_2") (pintype "passive"))
    )
    (net (code "391") (name "RSVD4") (class "Default")
      (node (ref "IC3") (pin "41") (pinfunction "RSVD_41") (pintype "input"))
      (node (ref "R32") (pin "2") (pinfunction "2_2") (pintype "passive"))
    )
    (net (code "392") (name "RSVD5") (class "Default")
      (node (ref "IC3") (pin "42") (pinfunction "RSVD_42") (pintype "input"))
      (node (ref "R33") (pin "2") (pinfunction "2_2") (pintype "passive"))
    )
    (net (code "393") (name "RSVD6") (class "Default")
      (node (ref "IC3") (pin "23") (pinfunction "RSVD_23") (pintype "bidirectional"))
      (node (ref "R17") (pin "2") (pinfunction "2_2") (pintype "passive"))
    )
    (net (code "394") (name "RTC-INT") (class "Default")
      (node (ref "IC4") (pin "7") (pinfunction "INT_7") (pintype "bidirectional"))
      (node (ref "IC5") (pin "91") (pinfunction "PB5_91") (pintype "bidirectional"))
      (node (ref "R35") (pin "2") (pinfunction "2_2") (pintype "passive"))
    )
    (net (code "395") (name "RTC-SCL") (class "Default")
      (node (ref "IC4") (pin "6") (pinfunction "SCL_6") (pintype "bidirectional"))
      (node (ref "IC5") (pin "92") (pinfunction "PB6_92") (pintype "bidirectional"))
      (node (ref "R36") (pin "2") (pinfunction "2_2") (pintype "passive"))
    )
    (net (code "396") (name "RTC-SDA") (class "Default")
      (node (ref "IC4") (pin "5") (pinfunction "SDA_5") (pintype "bidirectional"))
      (node (ref "IC5") (pin "93") (pinfunction "PB7_93") (pintype "bidirectional"))
      (node (ref "R37") (pin "2") (pinfunction "2_2") (pintype "passive"))
    )
    (net (code "397") (name "RTC_OSCIN") (class "Default")
      (node (ref "C29") (pin "1") (pinfunction "1_1") (pintype "passive"))
      (node (ref "IC4") (pin "1") (pinfunction "OSCIN_1") (pintype "bidirectional"))
      (node (ref "XTAL2") (pin "4") (pinfunction "2_4") (pintype "passive"))
    )
    (net (code "398") (name "RTC_OSCOUT") (class "Default")
      (node (ref "C32") (pin "1") (pinfunction "1_1") (pintype "passive"))
      (node (ref "IC4") (pin "2") (pinfunction "OSCOUT_2") (pintype "bidirectional"))
      (node (ref "XTAL2") (pin "1") (pinfunction "1_1") (pintype "passive"))
    )
    (net (code "399") (name "SPDLED") (class "Default")
      (node (ref "IC3") (pin "24") (pinfunction "SPDLED_24") (pintype "bidirectional"))
      (node (ref "R4") (pin "2") (pinfunction "2_2") (pintype "passive"))
    )
    (net (code "400") (name "SYS_JTMS-SWCLK") (class "Default")
      (node (ref "CON3") (pin "3") (pinfunction "SWCLK_3") (pintype "passive"))
      (node (ref "IC5") (pin "76") (pinfunction "PA14_76") (pintype "bidirectional"))
    )
    (net (code "401") (name "SYS_JTMS-SWDIO") (class "Default")
      (node (ref "CON3") (pin "2") (pinfunction "SWDIO_2") (pintype "passive"))
      (node (ref "IC5") (pin "72") (pinfunction "PA13_72") (pintype "bidirectional"))
    )
    (net (code "402") (name "TLCMP-RX") (class "Default")
      (node (ref "IC1") (pin "12") (pinfunction "R1OUT_12") (pintype "output"))
      (node (ref "IC5") (pin "69") (pinfunction "PA10_69") (pintype "bidirectional"))
    )
    (net (code "403") (name "TLCMP-TX") (class "Default")
      (node (ref "IC1") (pin "11") (pinfunction "T1IN_11") (pintype "input"))
      (node (ref "IC5") (pin "68") (pinfunction "PA9_68") (pintype "bidirectional"))
    )
    (net (code "404") (name "TOCAP") (class "Default")
      (node (ref "C12") (pin "1") (pinfunction "1_1") (pintype "passive"))
      (node (ref "IC3") (pin "20") (pinfunction "TOCAP_20") (pintype "bidirectional"))
    )
    (net (code "407") (name "VCCA_3V3") (class "Default")
      (node (ref "C104") (pin "+") (pinfunction "+_+") (pintype "passive"))
      (node (ref "C105") (pin "1") (pinfunction "1_1") (pintype "passive"))
      (node (ref "D22") (pin "A") (pinfunction "A_A") (pintype "passive"))
      (node (ref "IC10") (pin "2") (pinfunction "VOUT_2") (pintype "bidirectional"))
      (node (ref "IC5") (pin "22") (pinfunction "VDDA_22") (pintype "power_in"))
      (node (ref "L10") (pin "1") (pinfunction "1_1") (pintype "passive"))
      (node (ref "L11") (pin "1") (pinfunction "1_1") (pintype "passive"))
      (node (ref "L12") (pin "1") (pinfunction "1_1") (pintype "passive"))
      (node (ref "L8") (pin "2") (pinfunction "2_2") (pintype "passive"))
    )
    (net (code "408") (name "VCCRF") (class "Default")
      (node (ref "C17") (pin "1") (pinfunction "1_1") (pintype "passive"))
      (node (ref "C18") (pin "1") (pinfunction "1_1") (pintype "passive"))
      (node (ref "C21") (pin "1") (pinfunction "1_1") (pintype "passive"))
      (node (ref "C23") (pin "1") (pinfunction "1_1") (pintype "passive"))
      (node (ref "C25") (pin "1") (pinfunction "1_1") (pintype "passive"))
      (node (ref "C26") (pin "1") (pinfunction "1_1") (pintype "passive"))
      (node (ref "C27") (pin "1") (pinfunction "1_1") (pintype "passive"))
      (node (ref "IC3") (pin "11") (pinfunction "AVDD_11") (pintype "power_in"))
      (node (ref "IC3") (pin "15") (pinfunction "AVDD_15") (pintype "power_in"))
      (node (ref "IC3") (pin "17") (pinfunction "AVDD_17") (pintype "power_in"))
      (node (ref "IC3") (pin "21") (pinfunction "AVDD_21") (pintype "power_in"))
      (node (ref "IC3") (pin "4") (pinfunction "AVDD_4") (pintype "bidirectional"))
      (node (ref "IC3") (pin "8") (pinfunction "AVDD_8") (pintype "power_in"))
      (node (ref "L3") (pin "2") (pinfunction "2_2") (pintype "passive"))
      (node (ref "R10") (pin "2") (pinfunction "2_2") (pintype "passive"))
      (node (ref "R7") (pin "1") (pinfunction "1_1") (pintype "passive"))
      (node (ref "R8") (pin "1") (pinfunction "1_1") (pintype "passive"))
    )
    (net (code "409") (name "VREF_2.5V_ADC") (class "Default")
      (node (ref "IC12") (pin "13") (pinfunction "-IN_13") (pintype "input"))
      (node (ref "IC12") (pin "14") (pinfunction "OUT_14") (pintype "output"))
      (node (ref "IC5") (pin "21") (pinfunction "VREF+_21") (pintype "power_in"))
    )
    (net (code "411") (name "WI_RS485-RX") (class "Default")
      (node (ref "IC5") (pin "56") (pinfunction "PD9_56") (pintype "bidirectional"))
      (node (ref "R18") (pin "2") (pinfunction "2_2") (pintype "passive"))
    )
    (net (code "412") (name "WI_RS485-R{slash}W") (class "Default")
      (node (ref "IC5") (pin "57") (pinfunction "PD10_57") (pintype "bidirectional"))
      (node (ref "R19") (pin "2") (pinfunction "2_2") (pintype "passive"))
    )
    (net (code "413") (name "WI_RS485-TX") (class "Default")
      (node (ref "IC5") (pin "55") (pinfunction "PD8_55") (pintype "bidirectional"))
      (node (ref "R20") (pin "2") (pinfunction "2_2") (pintype "passive"))
    )
    (net (code "414") (name "unconnected-(C152-Pad+)") (class "Default")
      (node (ref "C152") (pin "+") (pinfunction "+_+") (pintype "passive"))
    )
    (net (code "415") (name "unconnected-(C152-Pad-)") (class "Default")
      (node (ref "C152") (pin "-") (pinfunction "-_-") (pintype "passive"))
    )
    (net (code "416") (name "unconnected-(C153-Pad+)") (class "Default")
      (node (ref "C153") (pin "+") (pinfunction "+_+") (pintype "passive"))
    )
    (net (code "417") (name "unconnected-(C153-Pad-)") (class "Default")
      (node (ref "C153") (pin "-") (pinfunction "-_-") (pintype "passive"))
    )
    (net (code "418") (name "unconnected-(G1-+-Pad+@1)") (class "Default")
      (node (ref "G1") (pin "+@1") (pinfunction "+_+@1") (pintype "passive"))
    )
    (net (code "419") (name "unconnected-(IC1-R2OUT-Pad9)") (class "Default")
      (node (ref "IC1") (pin "9") (pinfunction "R2OUT_9") (pintype "output"))
    )
    (net (code "420") (name "unconnected-(IC1-T2OUT-Pad7)") (class "Default")
      (node (ref "IC1") (pin "7") (pinfunction "T2OUT_7") (pintype "output"))
    )
    (net (code "421") (name "unconnected-(IC3-DNC-Pad7)") (class "Default")
      (node (ref "IC3") (pin "7") (pinfunction "DNC_7") (pintype "no_connect"))
    )
    (net (code "422") (name "unconnected-(IC3-NC1-Pad12)") (class "Default")
      (node (ref "IC3") (pin "12") (pinfunction "NC1_12") (pintype "no_connect"))
    )
    (net (code "423") (name "unconnected-(IC3-NC2-Pad13)") (class "Default")
      (node (ref "IC3") (pin "13") (pinfunction "NC2_13") (pintype "no_connect"))
    )
    (net (code "424") (name "unconnected-(IC3-NC3-Pad46)") (class "Default")
      (node (ref "IC3") (pin "46") (pinfunction "NC3_46") (pintype "no_connect"))
    )
    (net (code "425") (name "unconnected-(IC3-NC4-Pad47)") (class "Default")
      (node (ref "IC3") (pin "47") (pinfunction "NC4_47") (pintype "no_connect"))
    )
    (net (code "426") (name "unconnected-(IC3-VBG-Pad18)") (class "Default")
      (node (ref "IC3") (pin "18") (pinfunction "VBG_18") (pintype "bidirectional"))
    )
    (net (code "427") (name "unconnected-(IC5-NC-Pad73)") (class "Default")
      (node (ref "IC5") (pin "73") (pinfunction "NC_73") (pintype "no_connect"))
    )
    (net (code "428") (name "unconnected-(IC5-PB2-Pad37)") (class "Default")
      (node (ref "IC5") (pin "37") (pinfunction "PB2_37") (pintype "bidirectional"))
    )
    (net (code "429") (name "unconnected-(IC5-PC13-TAMPER-RTC-Pad7)") (class "Default")
      (node (ref "IC5") (pin "7") (pinfunction "PC13-TAMPER-RTC_7") (pintype "bidirectional"))
    )
    (net (code "430") (name "unconnected-(IC5-PC14-OSC32_IN-Pad8)") (class "Default")
      (node (ref "IC5") (pin "8") (pinfunction "PC14-OSC32_IN_8") (pintype "input"))
    )
    (net (code "431") (name "unconnected-(IC5-PC15-OSC32_OUT-Pad9)") (class "Default")
      (node (ref "IC5") (pin "9") (pinfunction "PC15-OSC32_OUT_9") (pintype "bidirectional"))
    )
    (net (code "432") (name "unconnected-(IC9-NC-Pad3)") (class "Default")
      (node (ref "IC9") (pin "3") (pinfunction "NC_3") (pintype "no_connect"))
    )
    (net (code "433") (name "unconnected-(U1-P0.0-Pad24)") (class "Default")
      (node (ref "U1") (pin "24") (pinfunction "P0.0_24") (pintype "bidirectional"))
    )
    (net (code "434") (name "unconnected-(U1-P0.1-Pad23)") (class "Default")
      (node (ref "U1") (pin "23") (pinfunction "P0.1_23") (pintype "bidirectional"))
    )
    (net (code "435") (name "unconnected-(U1-P0.4-Pad20)") (class "Default")
      (node (ref "U1") (pin "20") (pinfunction "P0.4_20") (pintype "bidirectional"))
    )
    (net (code "436") (name "unconnected-(U1-P0.5-Pad19)") (class "Default")
      (node (ref "U1") (pin "19") (pinfunction "P0.5_19") (pintype "bidirectional"))
    )
    (net (code "437") (name "unconnected-(U1-P0.6-Pad18)") (class "Default")
      (node (ref "U1") (pin "18") (pinfunction "P0.6_18") (pintype "bidirectional"))
    )
    (net (code "438") (name "unconnected-(U1-P0.7-Pad17)") (class "Default")
      (node (ref "U1") (pin "17") (pinfunction "P0.7_17") (pintype "bidirectional"))
    )
    (net (code "439") (name "unconnected-(U1-P1.2-Pad14)") (class "Default")
      (node (ref "U1") (pin "14") (pinfunction "P1.2_14") (pintype "bidirectional"))
    )
    (net (code "440") (name "unconnected-(U1-P1.3-Pad13)") (class "Default")
      (node (ref "U1") (pin "13") (pinfunction "P1.3_13") (pintype "bidirectional"))
    )
    (net (code "441") (name "unconnected-(U1-P1.4-Pad12)") (class "Default")
      (node (ref "U1") (pin "12") (pinfunction "P1.4_12") (pintype "bidirectional"))
    )
    (net (code "442") (name "unconnected-(U1-P1.5-Pad11)") (class "Default")
      (node (ref "U1") (pin "11") (pinfunction "P1.5_11") (pintype "bidirectional"))
    )
    (net (code "443") (name "unconnected-(U1-P1.6-Pad8)") (class "Default")
      (node (ref "U1") (pin "8") (pinfunction "P1.6_8") (pintype "bidirectional"))
    )
    (net (code "444") (name "unconnected-(U1-P1.7-Pad7)") (class "Default")
      (node (ref "U1") (pin "7") (pinfunction "P1.7_7") (pintype "bidirectional"))
    )
    (net (code "445") (name "unconnected-(U1-P2.1{slash}DD-Pad5)") (class "Default")
      (node (ref "U1") (pin "5") (pinfunction "P2.1/DD_5") (pintype "bidirectional"))
    )
    (net (code "446") (name "unconnected-(U1-P2.2{slash}DC-Pad4)") (class "Default")
      (node (ref "U1") (pin "4") (pinfunction "P2.2/DC_4") (pintype "bidirectional"))
    )
    (net (code "447") (name "unconnected-(U1-USB_D+{slash}SCL-Pad9)") (class "Default")
      (node (ref "U1") (pin "9") (pinfunction "USB_D+/SCL_9") (pintype "bidirectional"))
    )
    (net (code "448") (name "unconnected-(U1-USB_D-{slash}SDA-Pad10)") (class "Default")
      (node (ref "U1") (pin "10") (pinfunction "USB_D-/SDA_10") (pintype "bidirectional"))
    )
    (net (code "449") (name "unconnected-(X1-Pad1)") (class "Default")
      (node (ref "X1") (pin "1") (pinfunction "1_1") (pintype "passive"))
    )
    (net (code "450") (name "unconnected-(X1-Pad4)") (class "Default")
      (node (ref "X1") (pin "4") (pinfunction "4_4") (pintype "passive"))
    )
    (net (code "451") (name "unconnected-(X1-Pad6)") (class "Default")
      (node (ref "X1") (pin "6") (pinfunction "6_6") (pintype "passive"))
    )
    (net (code "452") (name "unconnected-(X1-Pad7)") (class "Default")
      (node (ref "X1") (pin "7") (pinfunction "7_7") (pintype "passive"))
    )
    (net (code "453") (name "unconnected-(X1-PadG1)") (class "Default")
      (node (ref "X1") (pin "G1") (pinfunction "G1_G1") (pintype "passive"))
    )
  )
)
